# PX4FMUv2_4_6.net
KiCad netlist of a schematic drawn in EAGLE
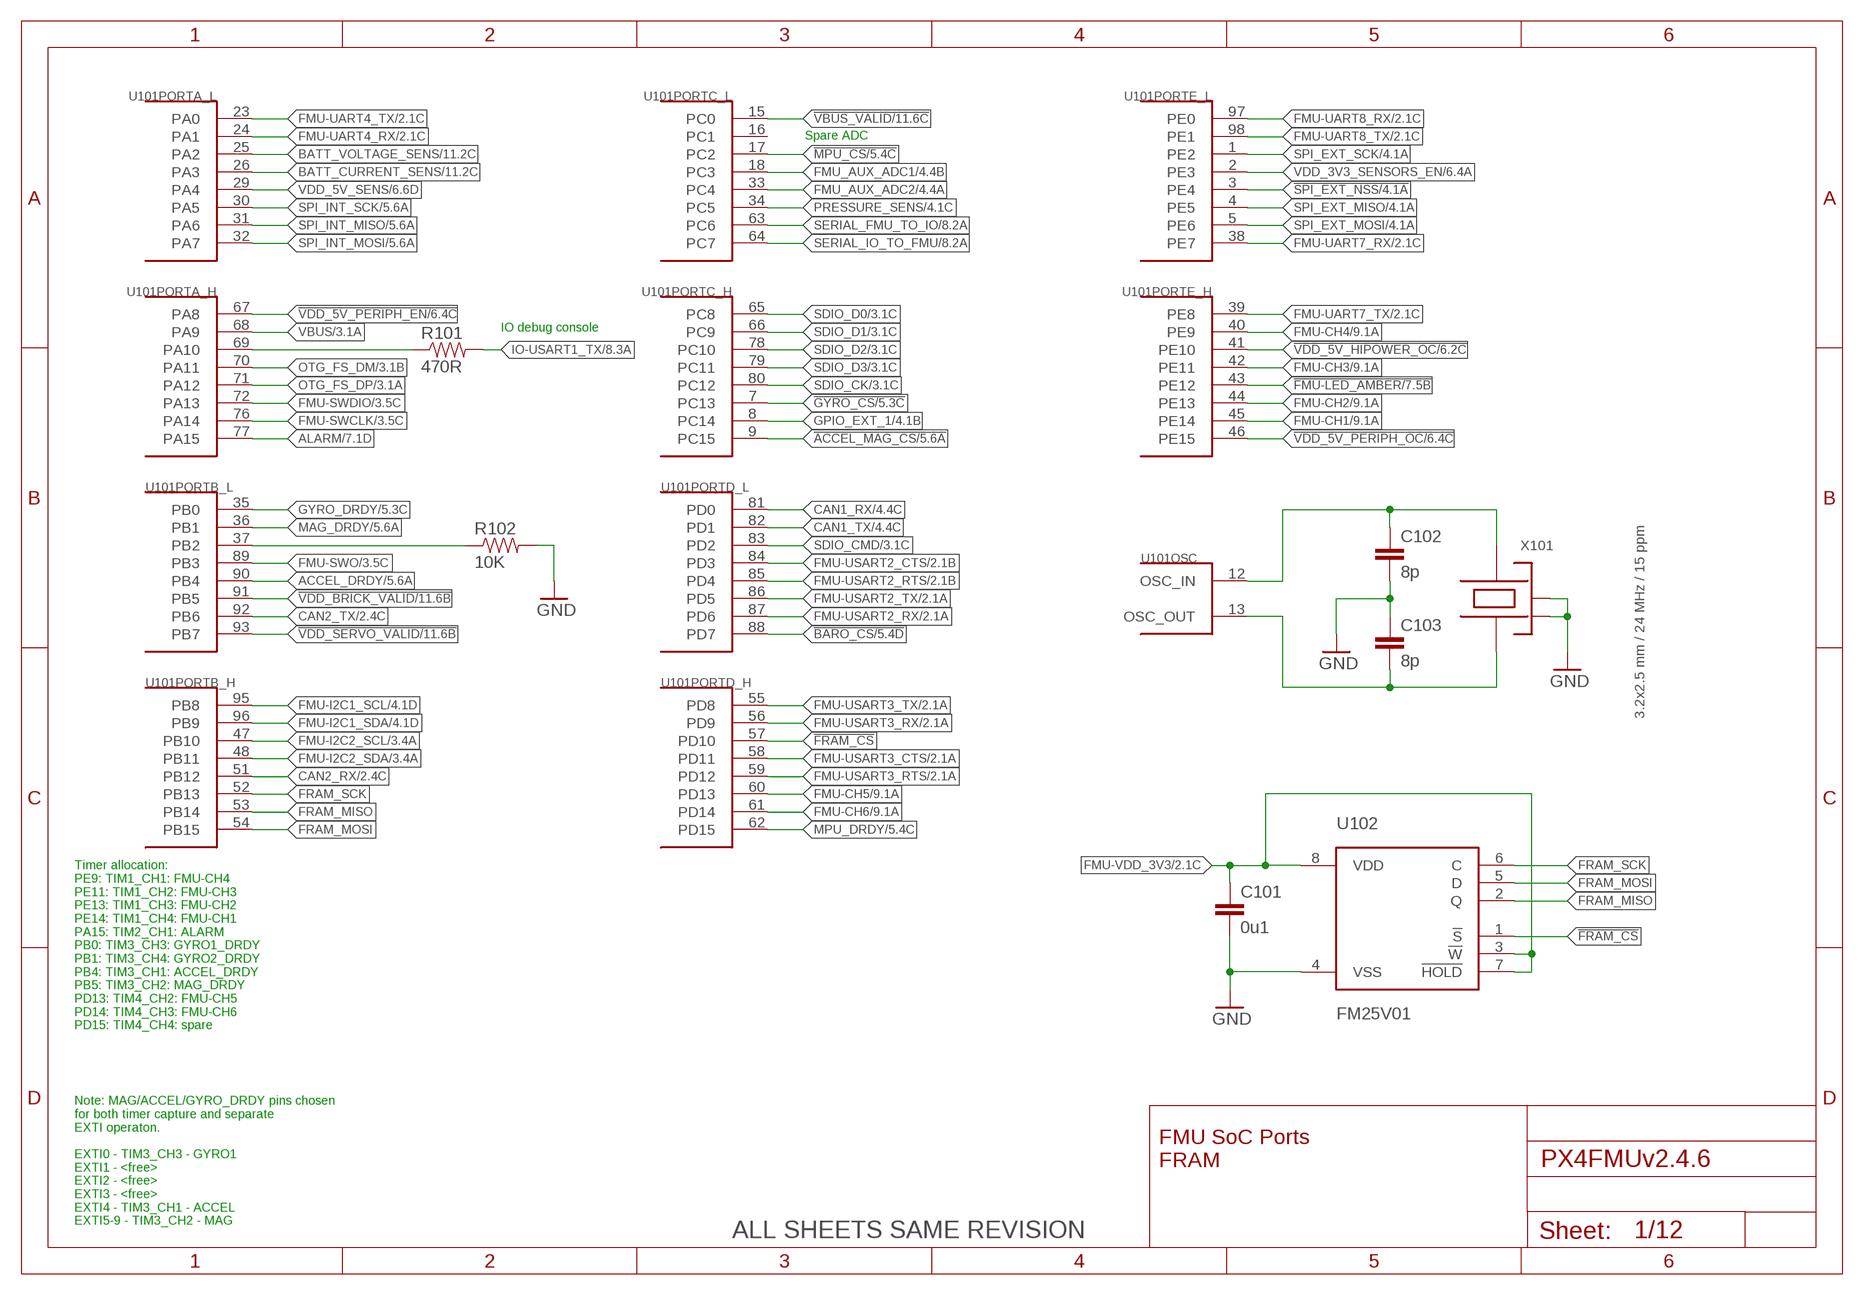
[diagram p0: schematic, sheet 1]
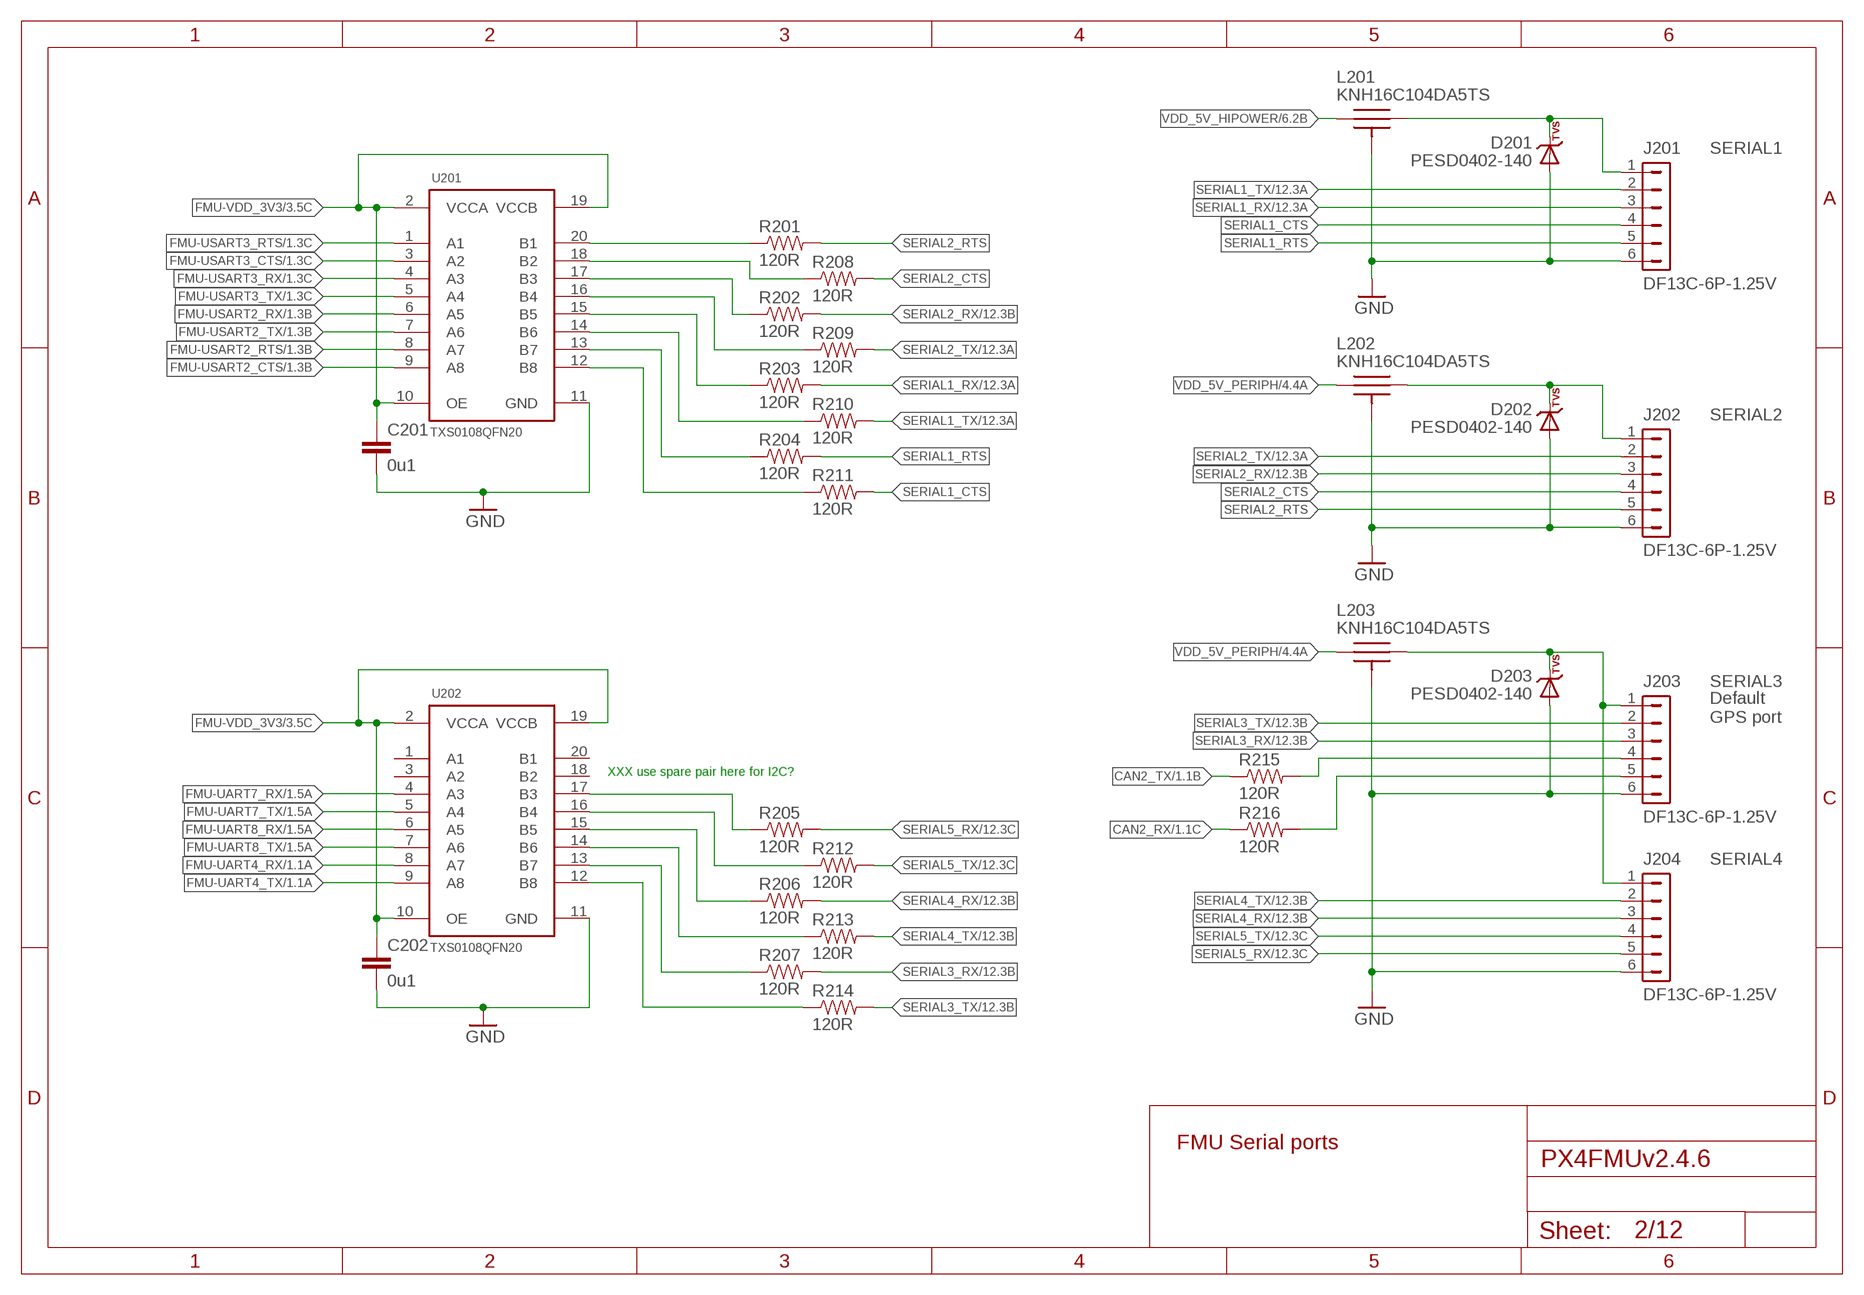
[diagram p1: schematic, sheet 2]
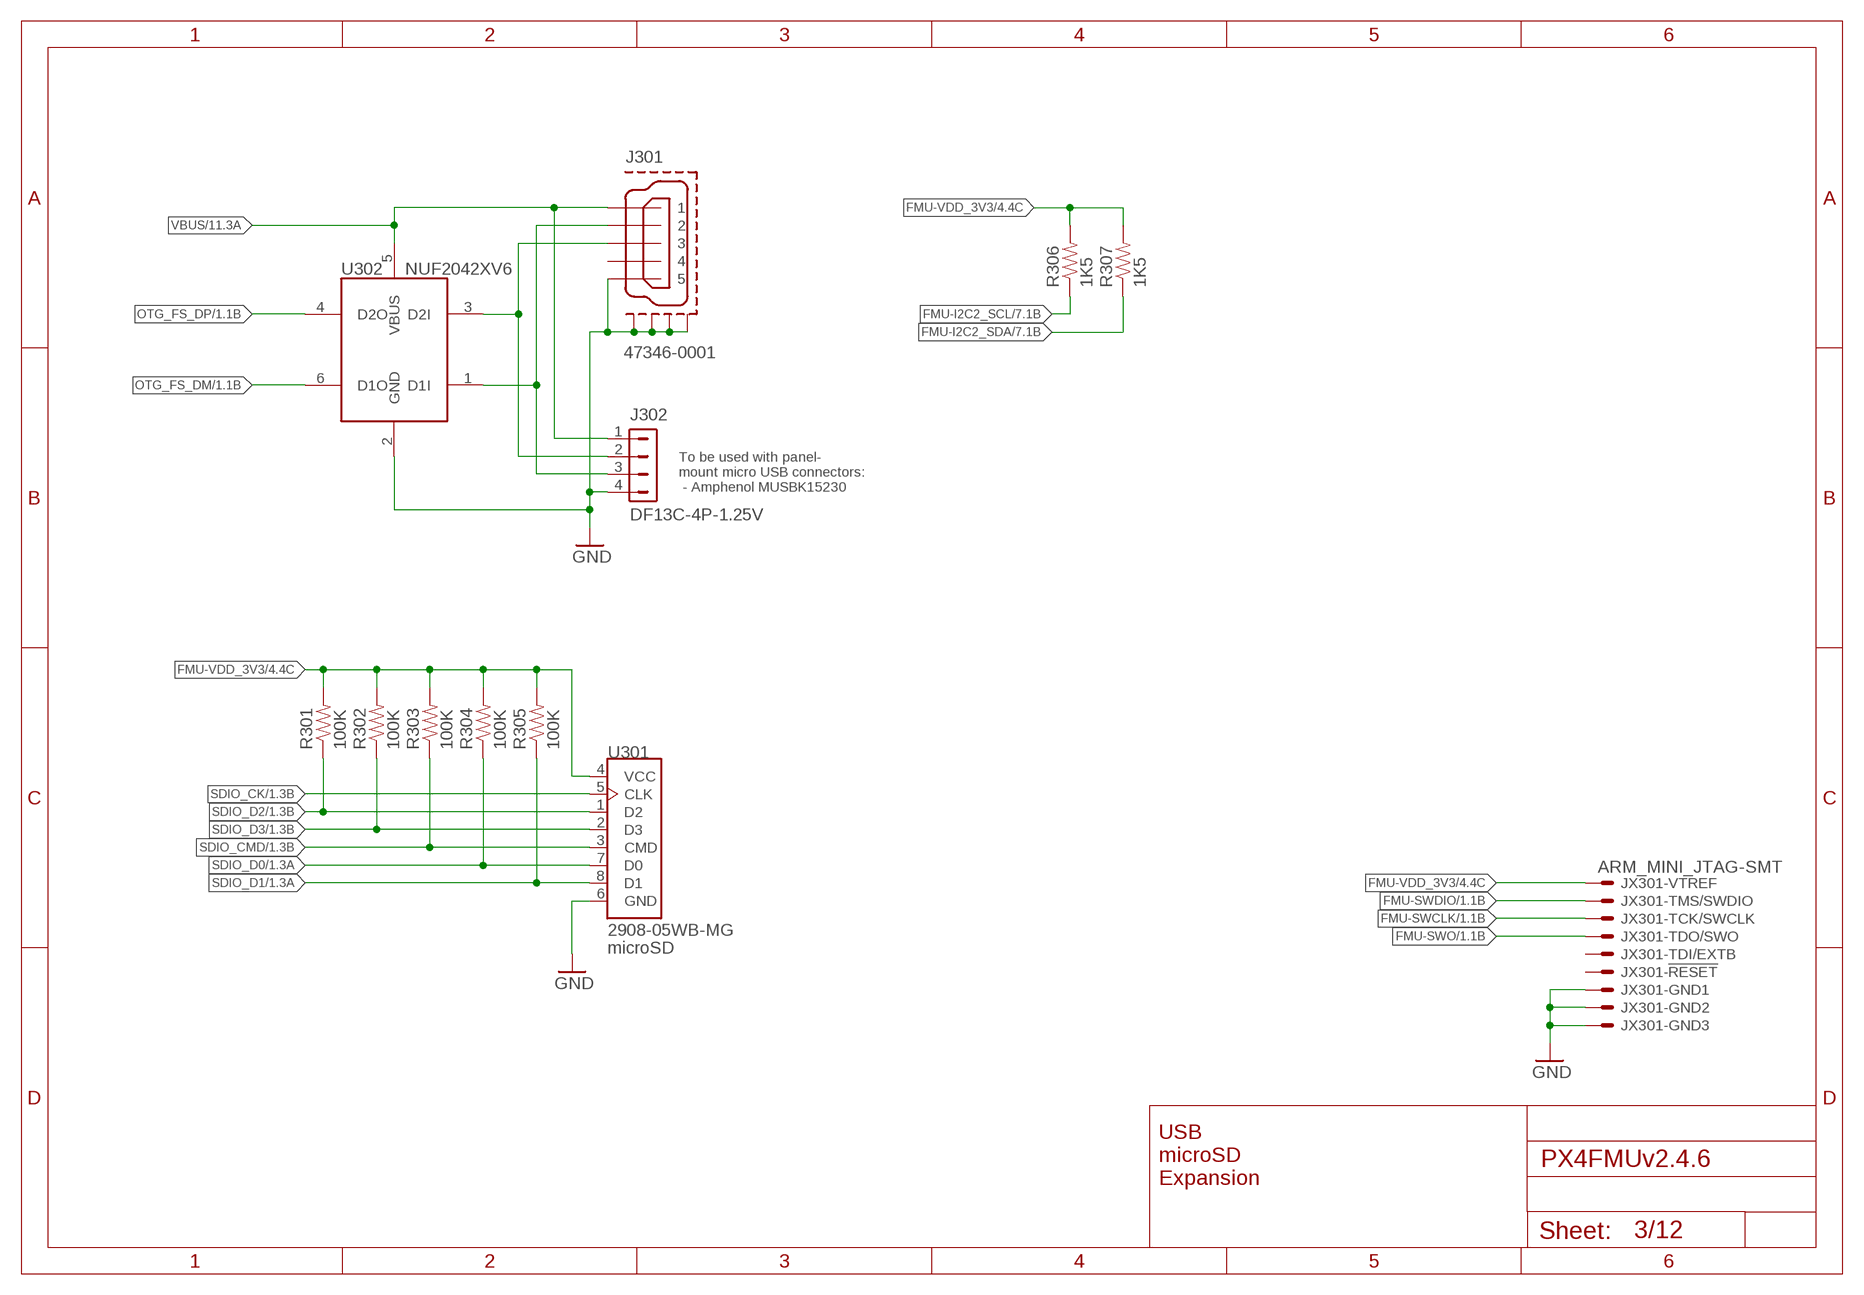
[diagram p2: schematic, sheet 3]
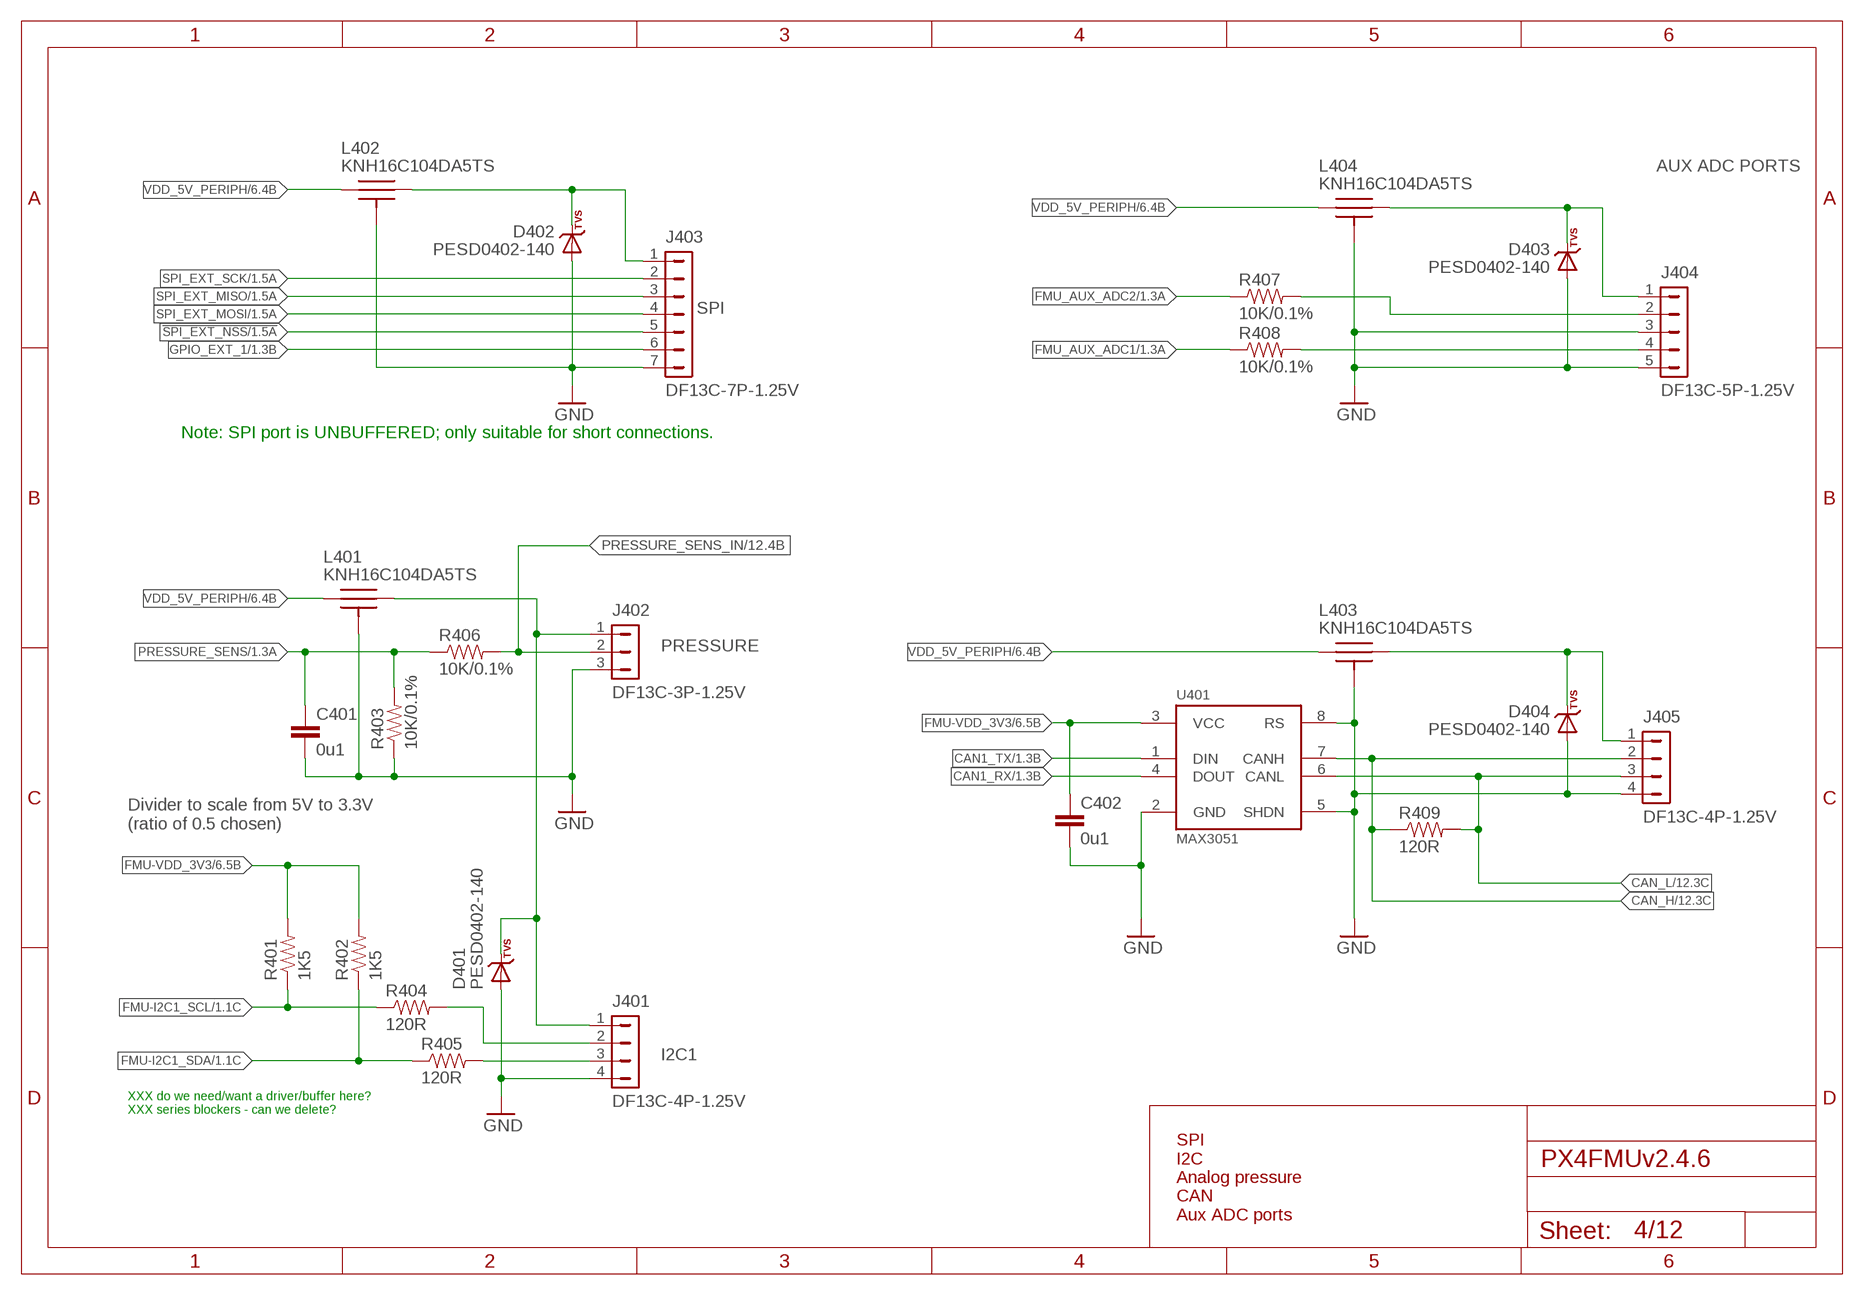
[diagram p3: schematic, sheet 4]
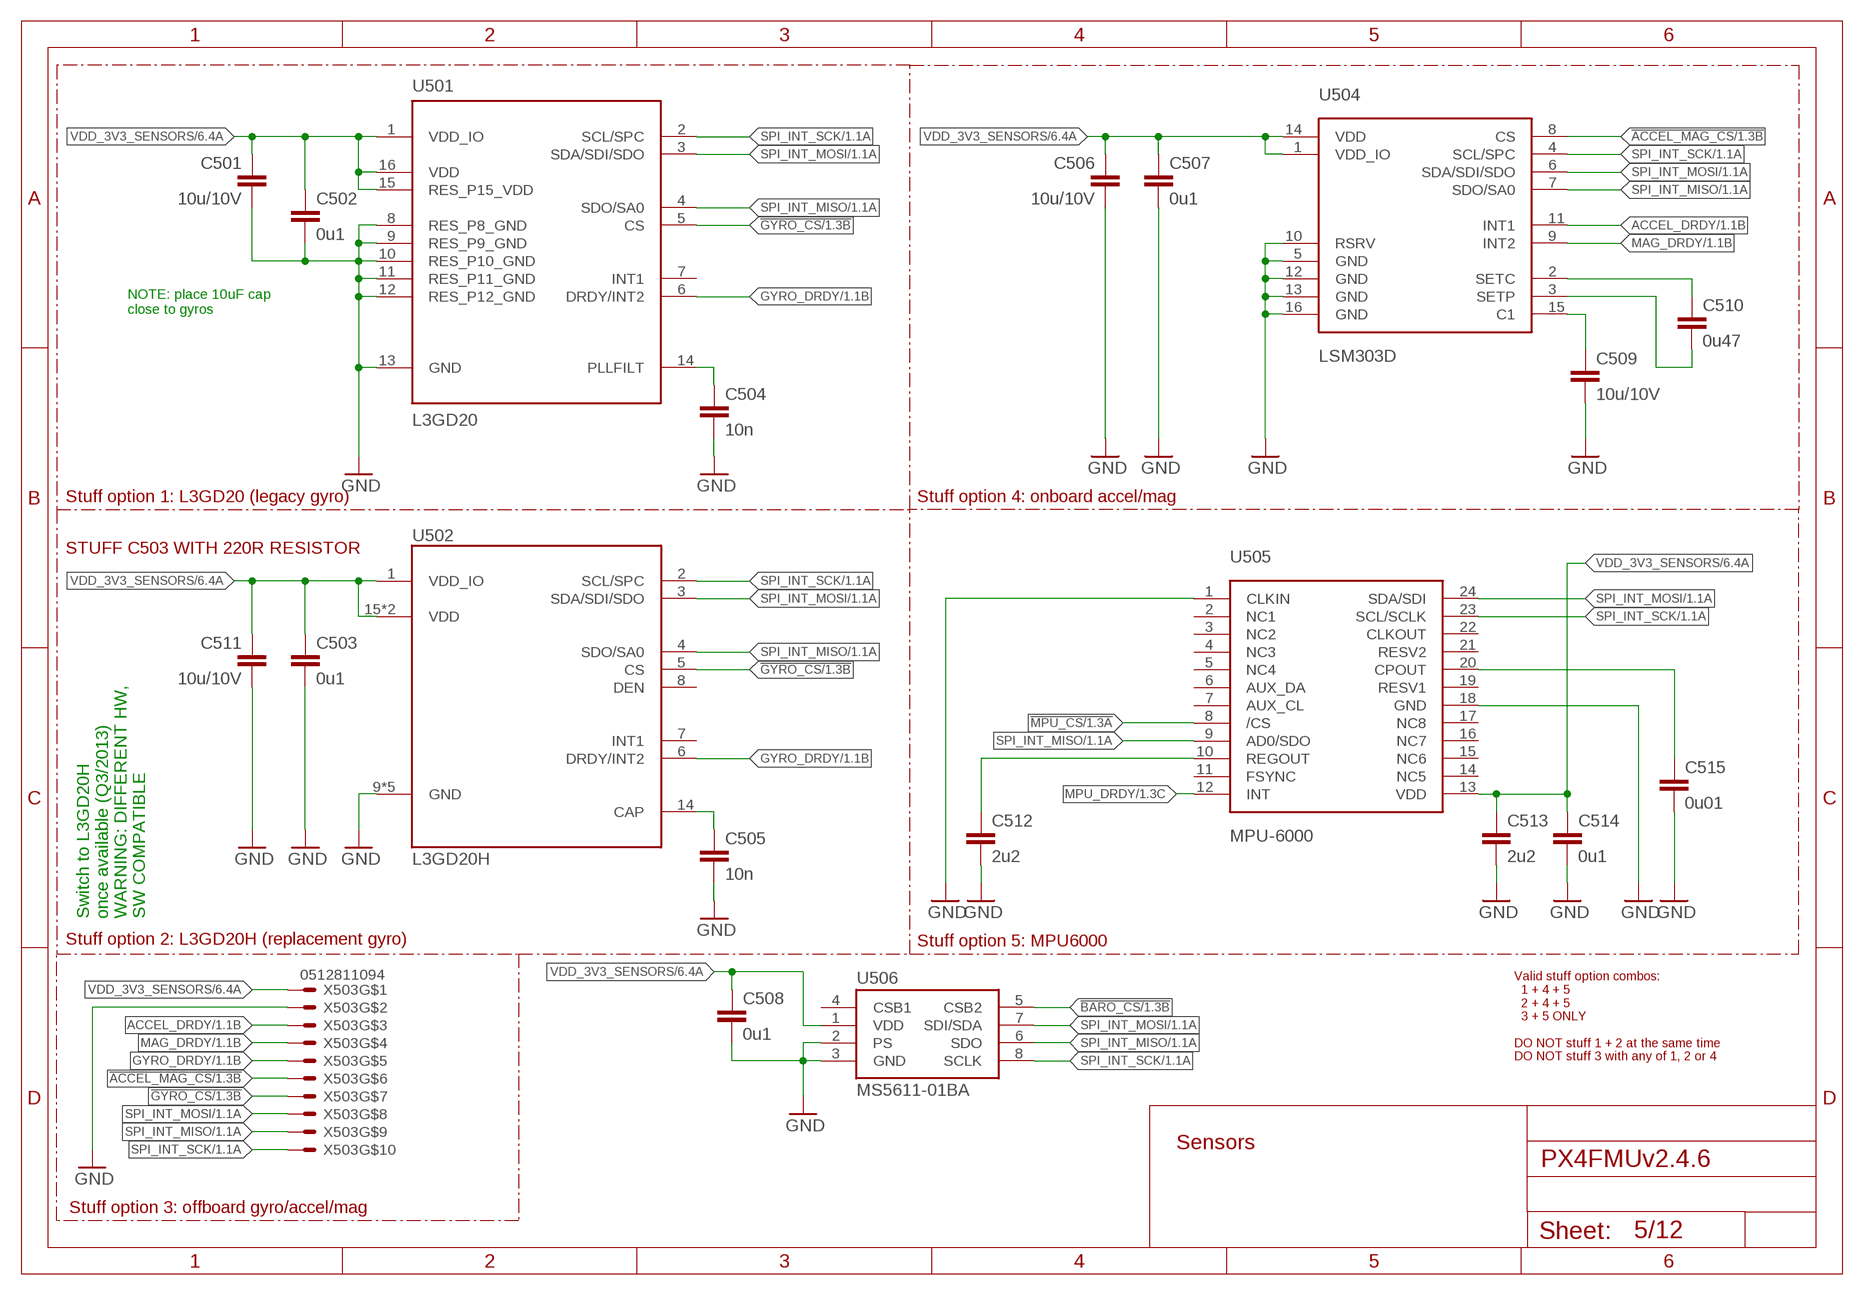
[diagram p4: schematic, sheet 5]
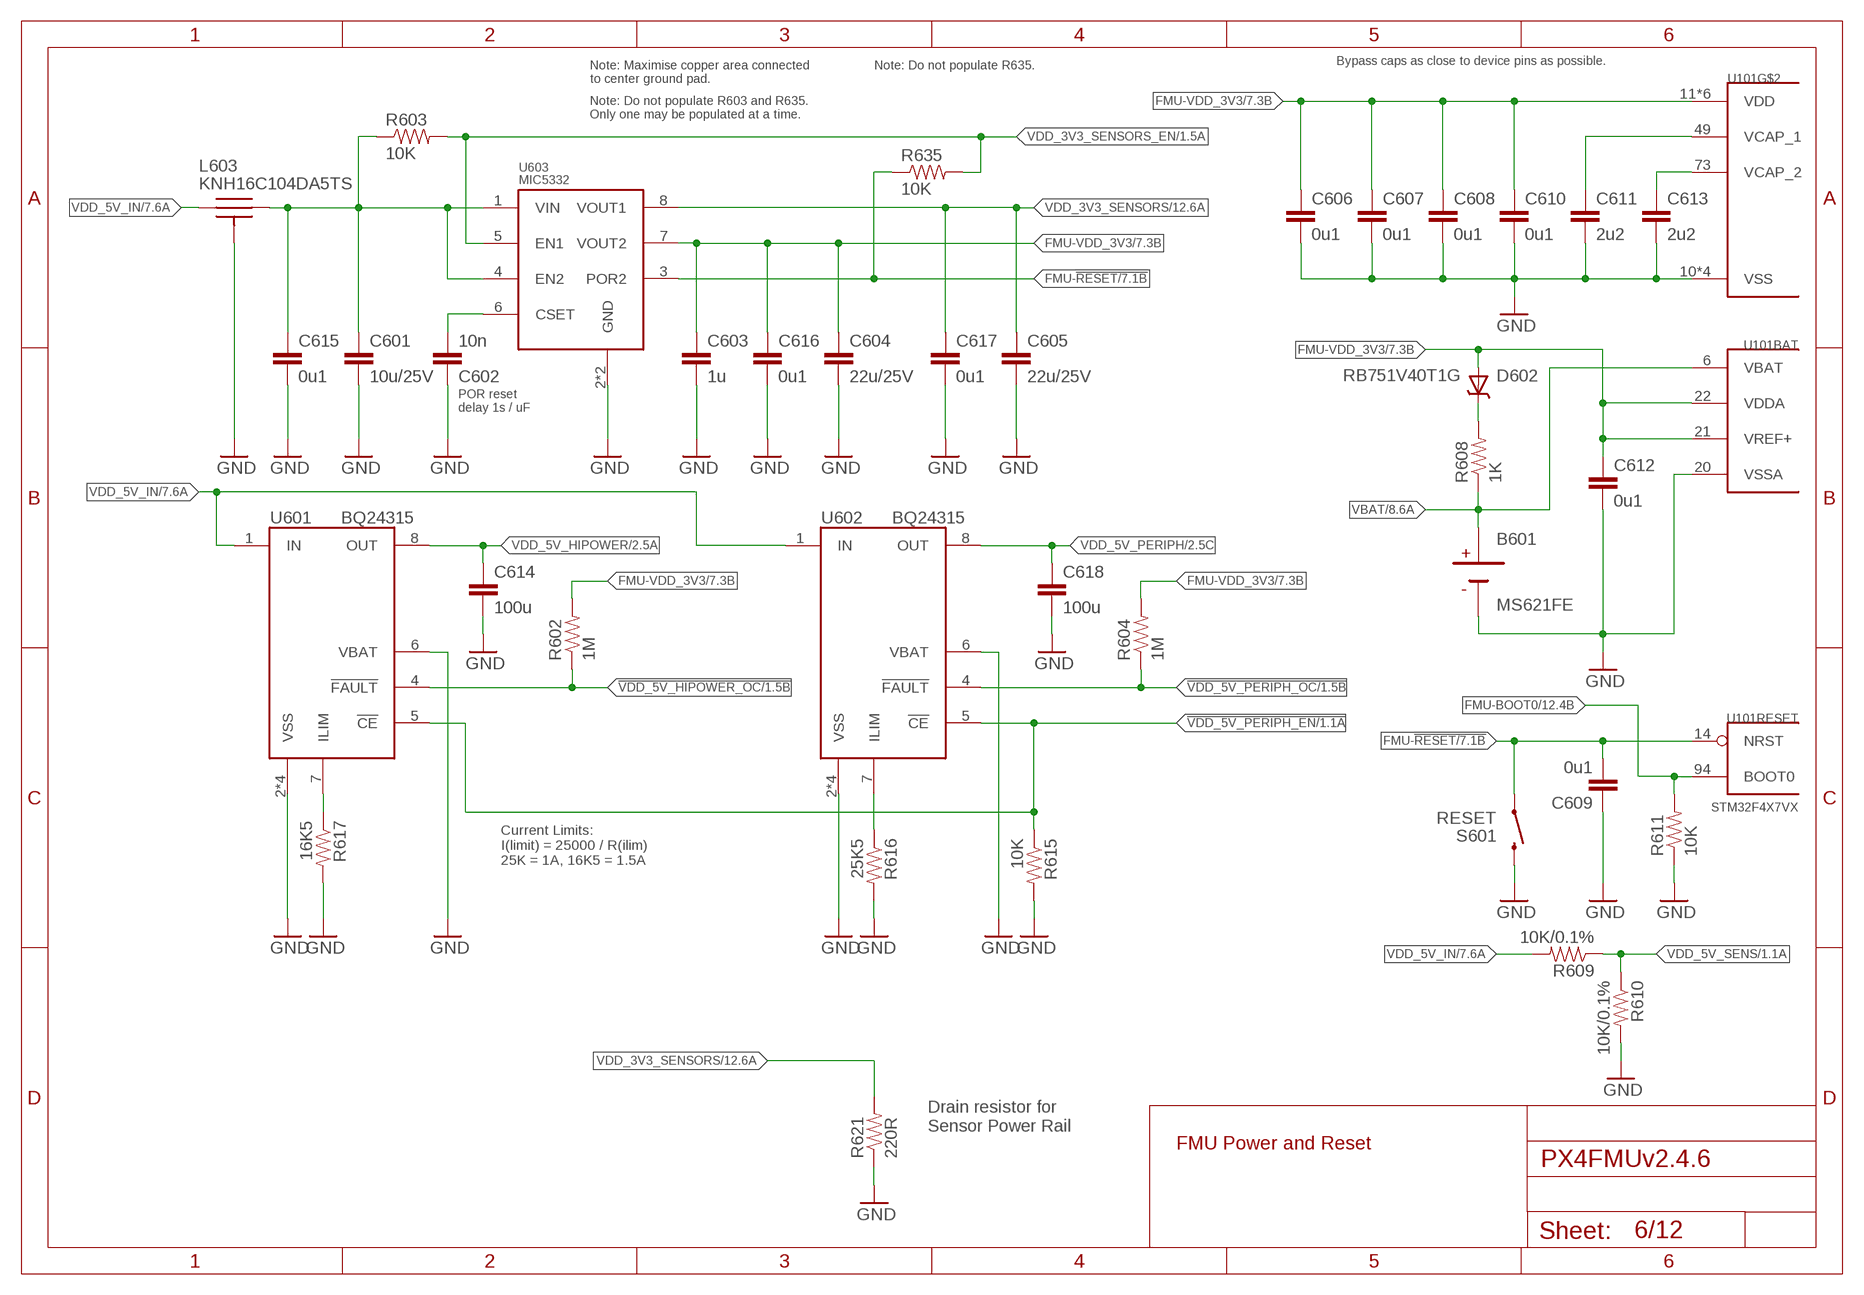
[diagram p5: schematic, sheet 6]
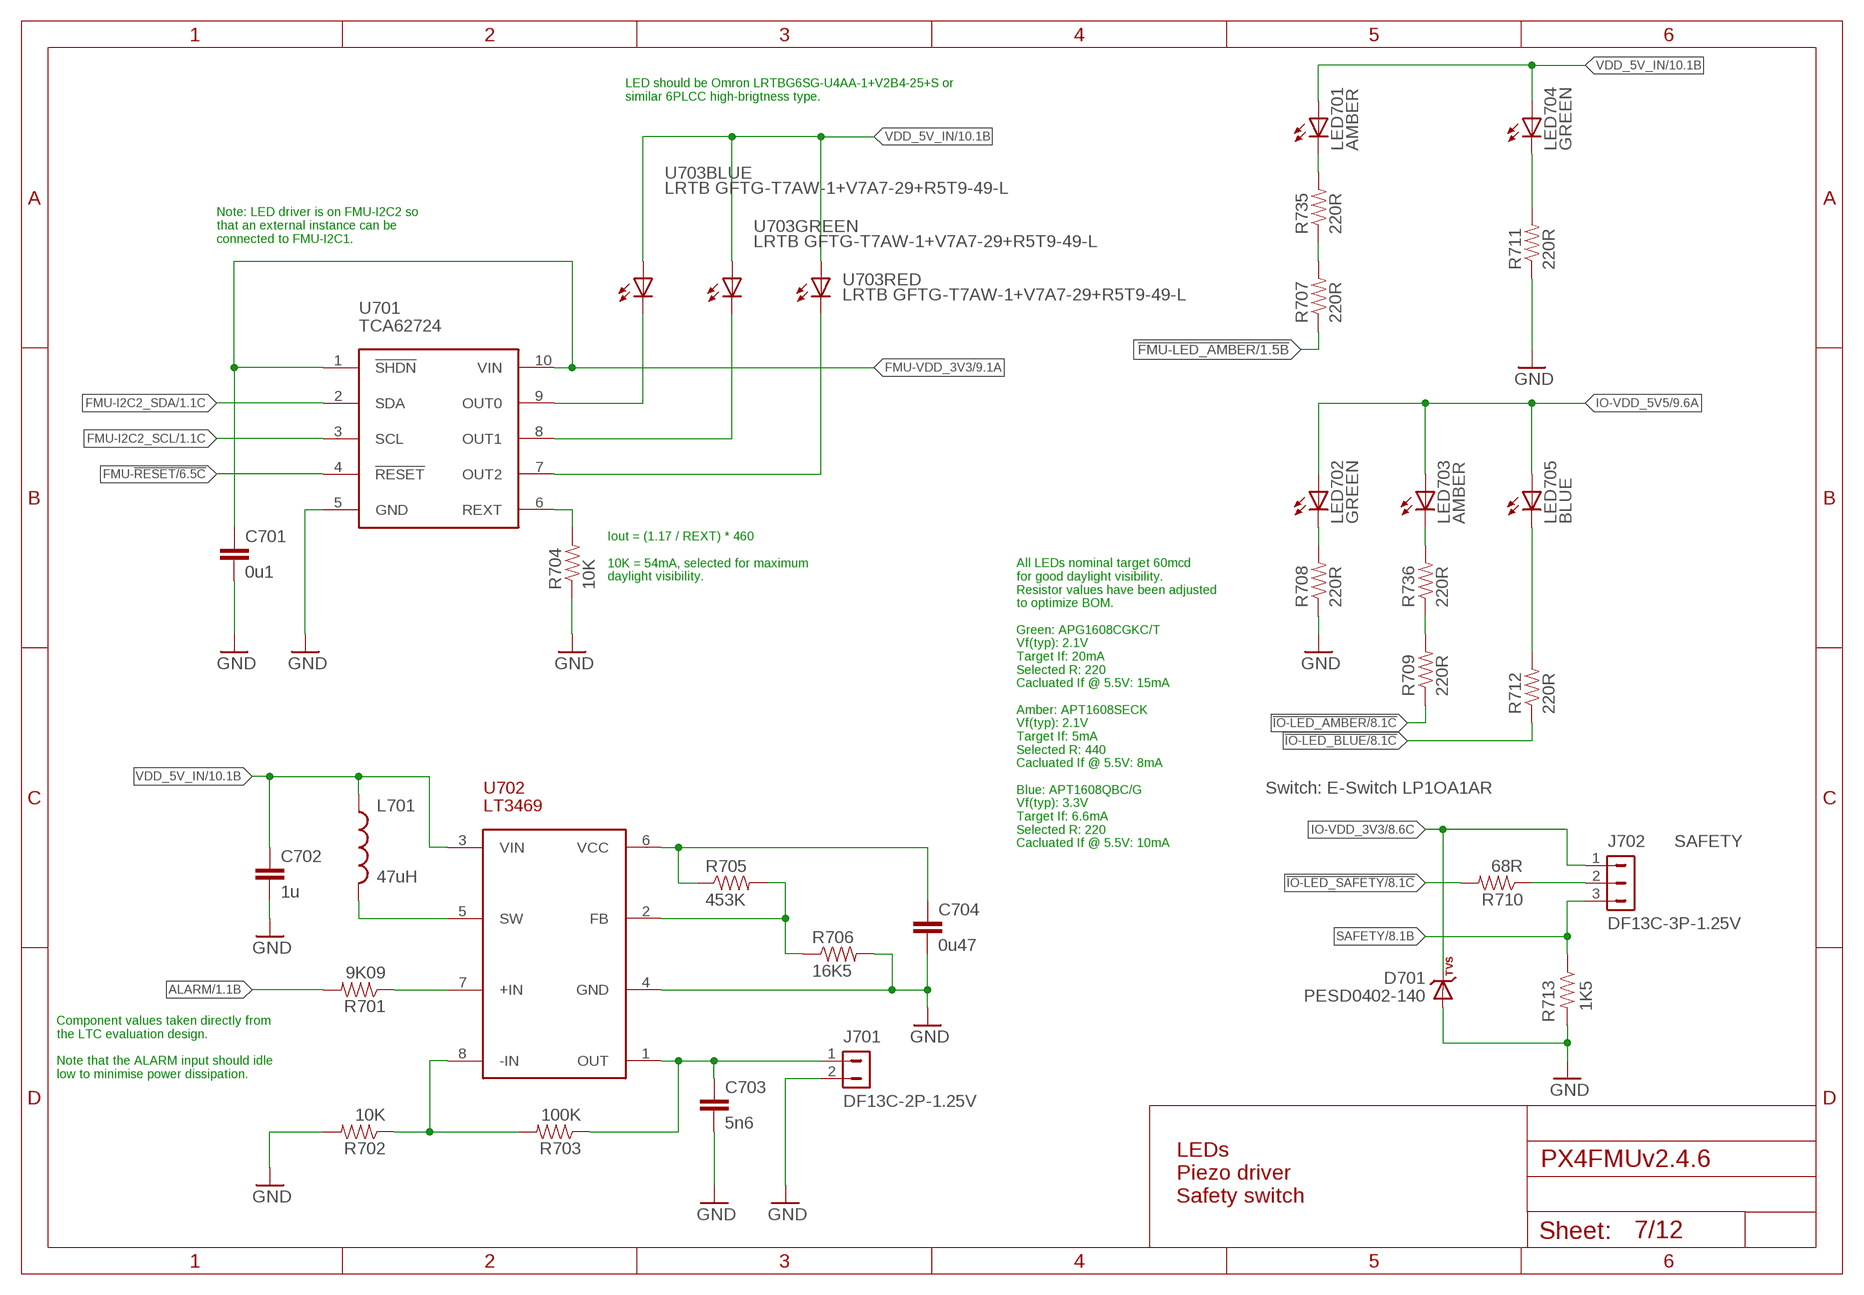
[diagram p6: schematic, sheet 7]
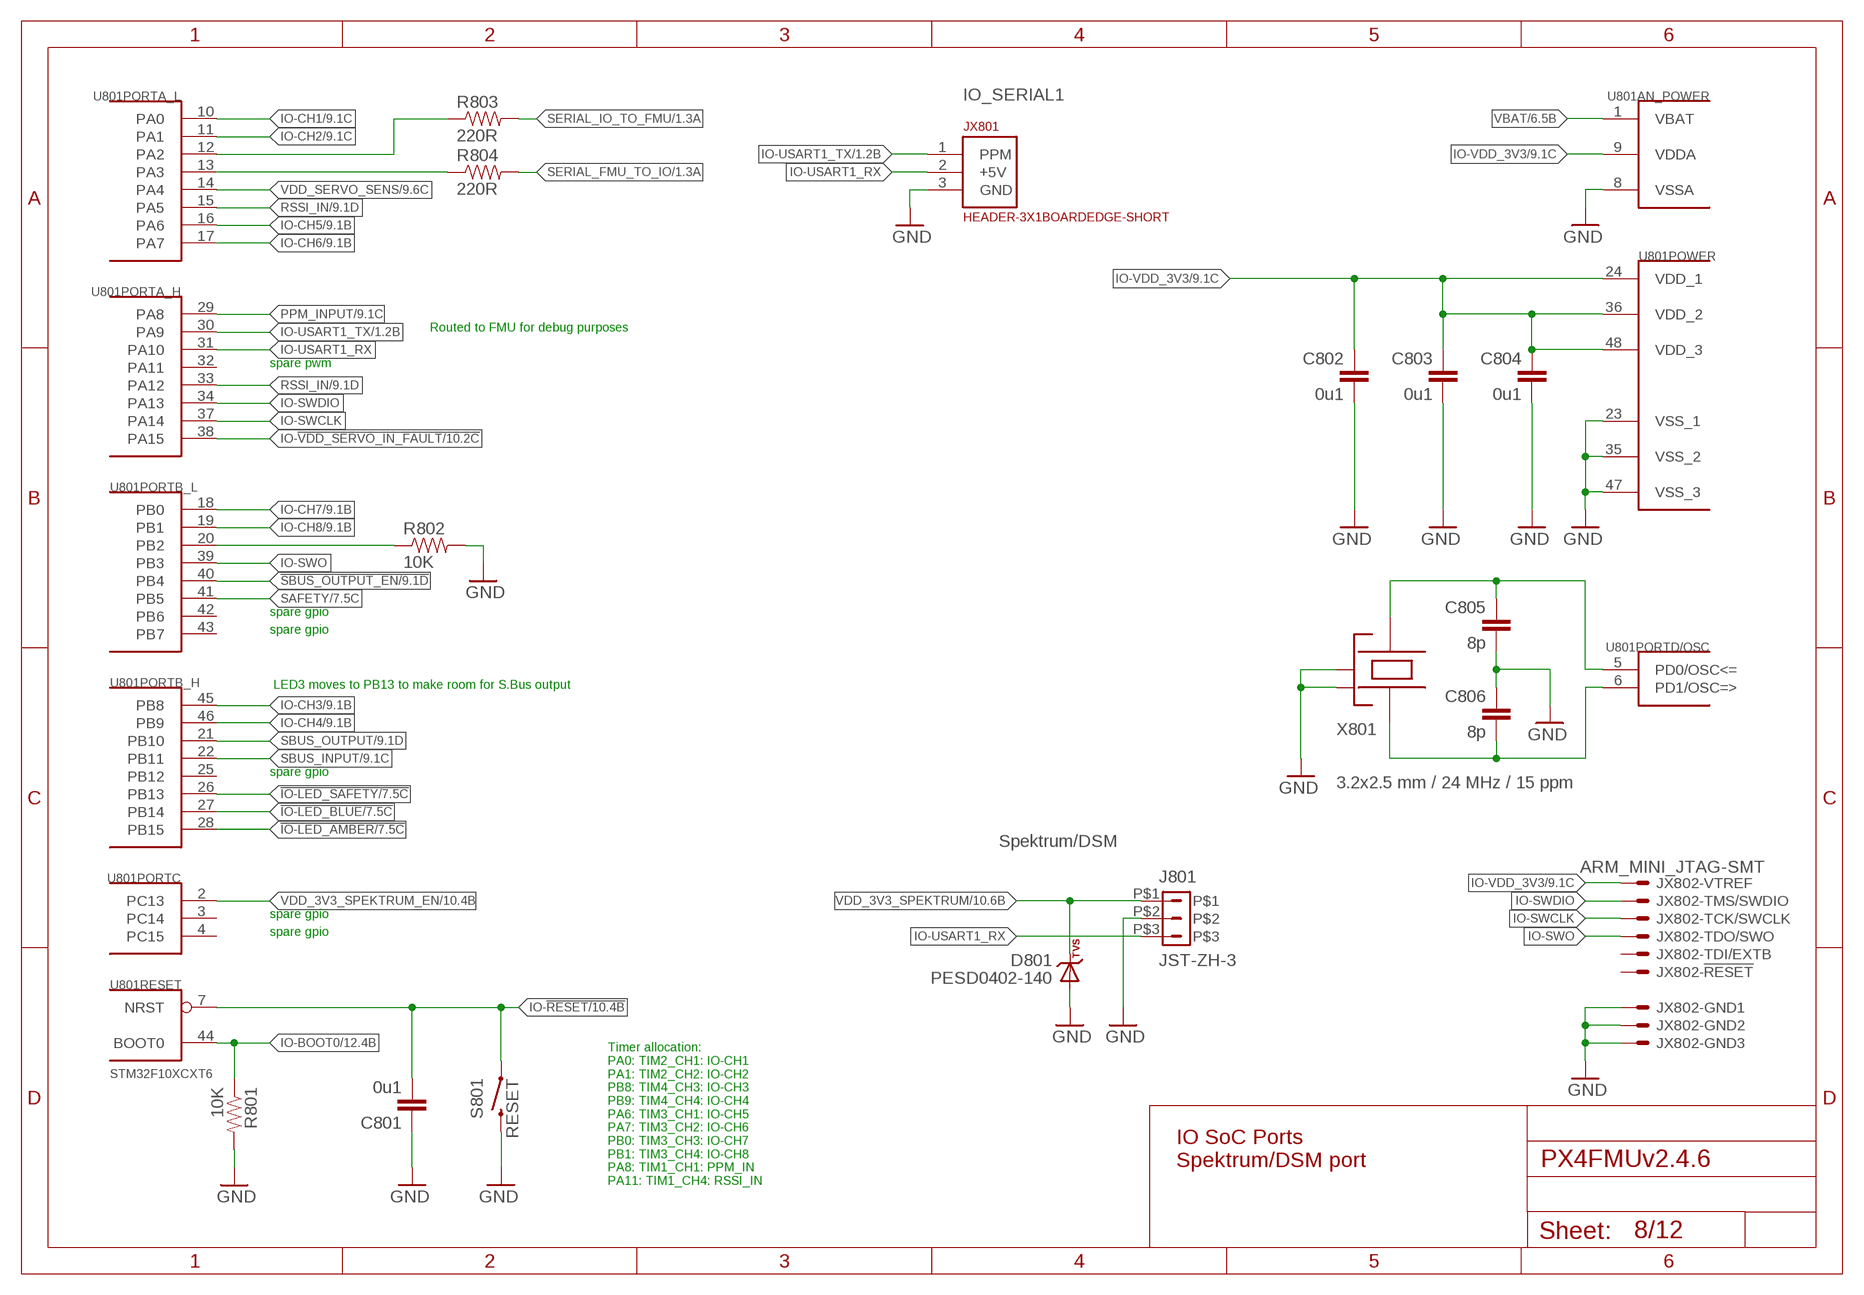
[diagram p7: schematic, sheet 8]
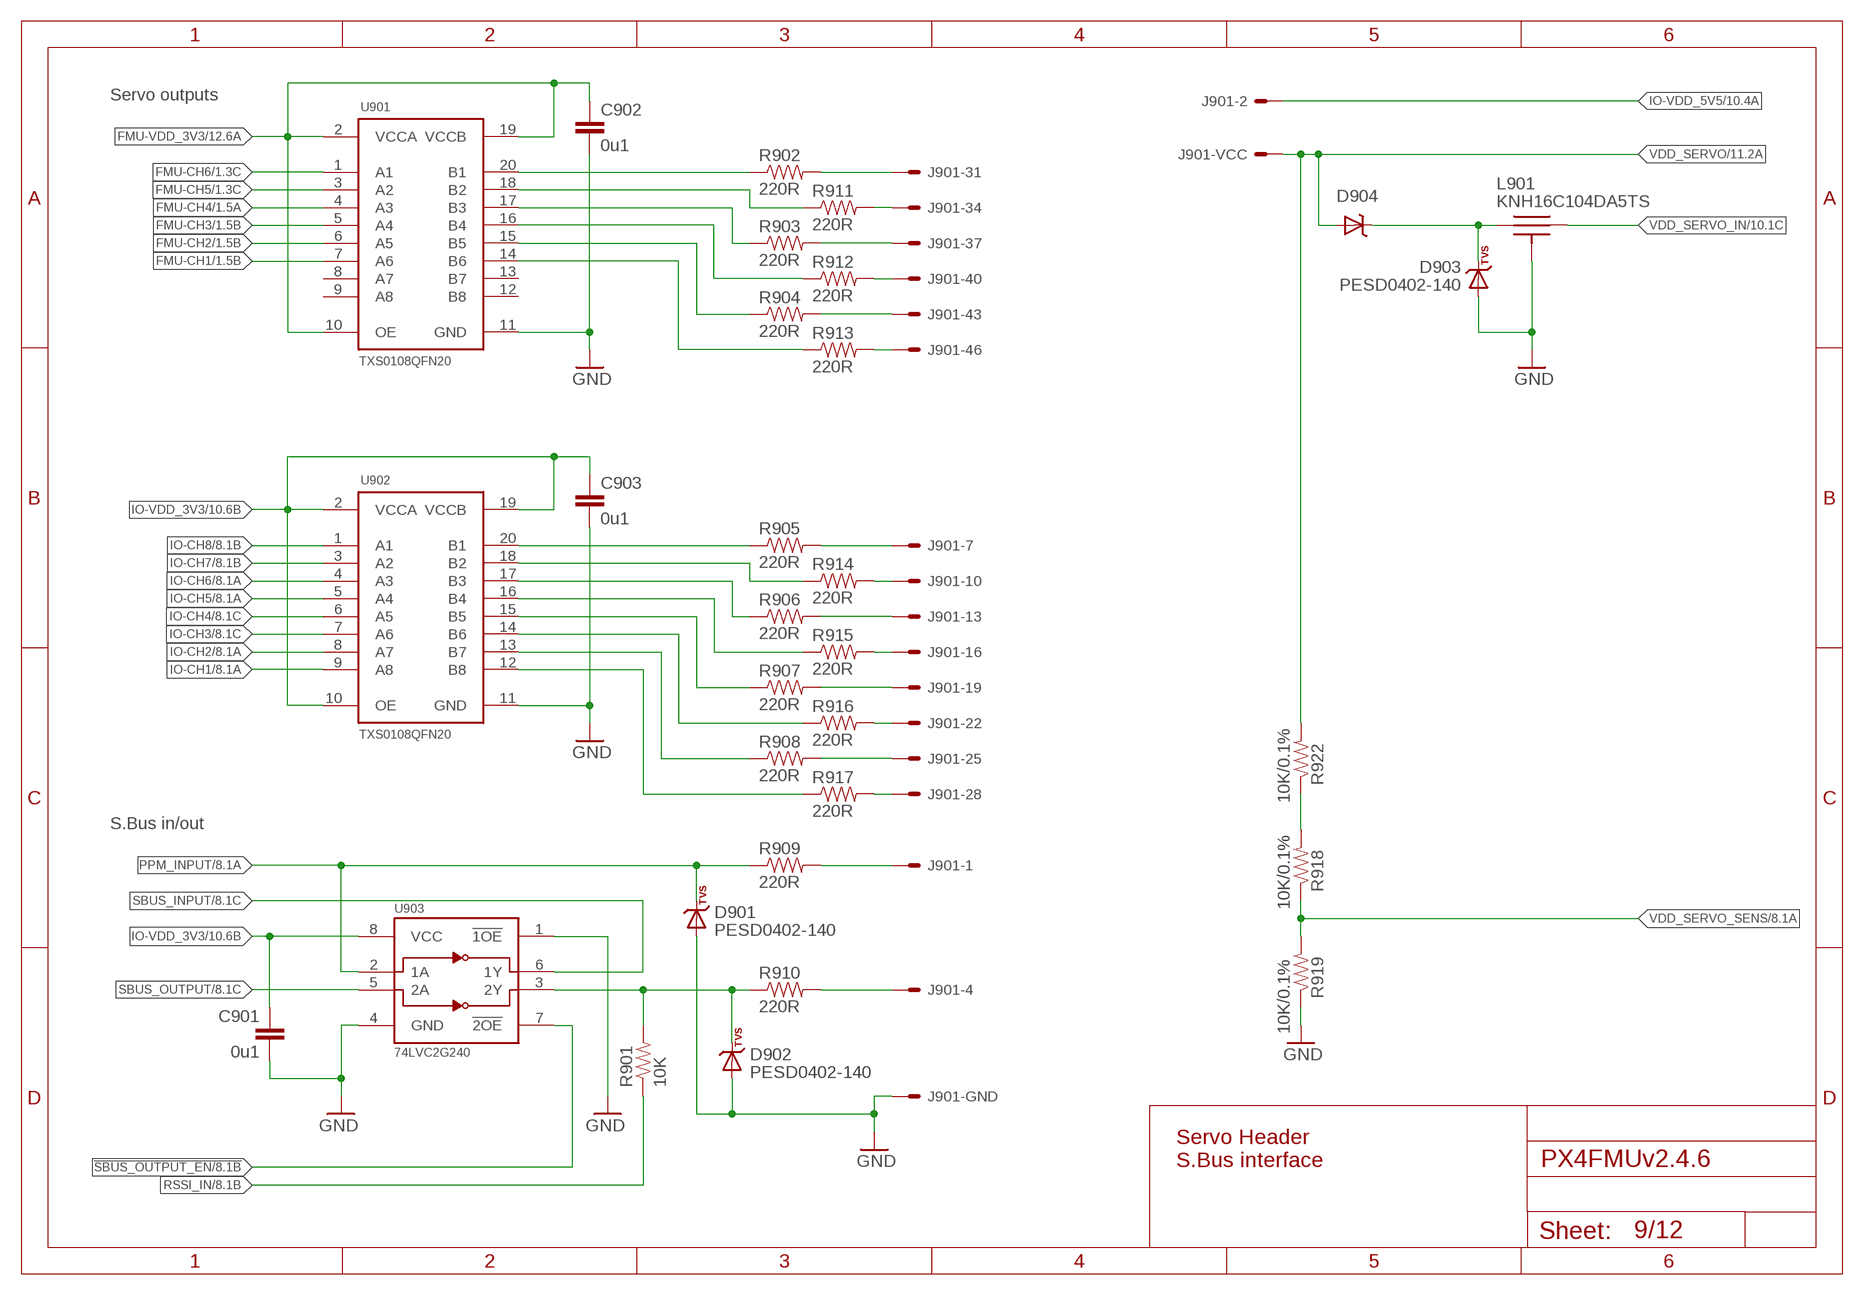
[diagram p8: schematic, sheet 9]
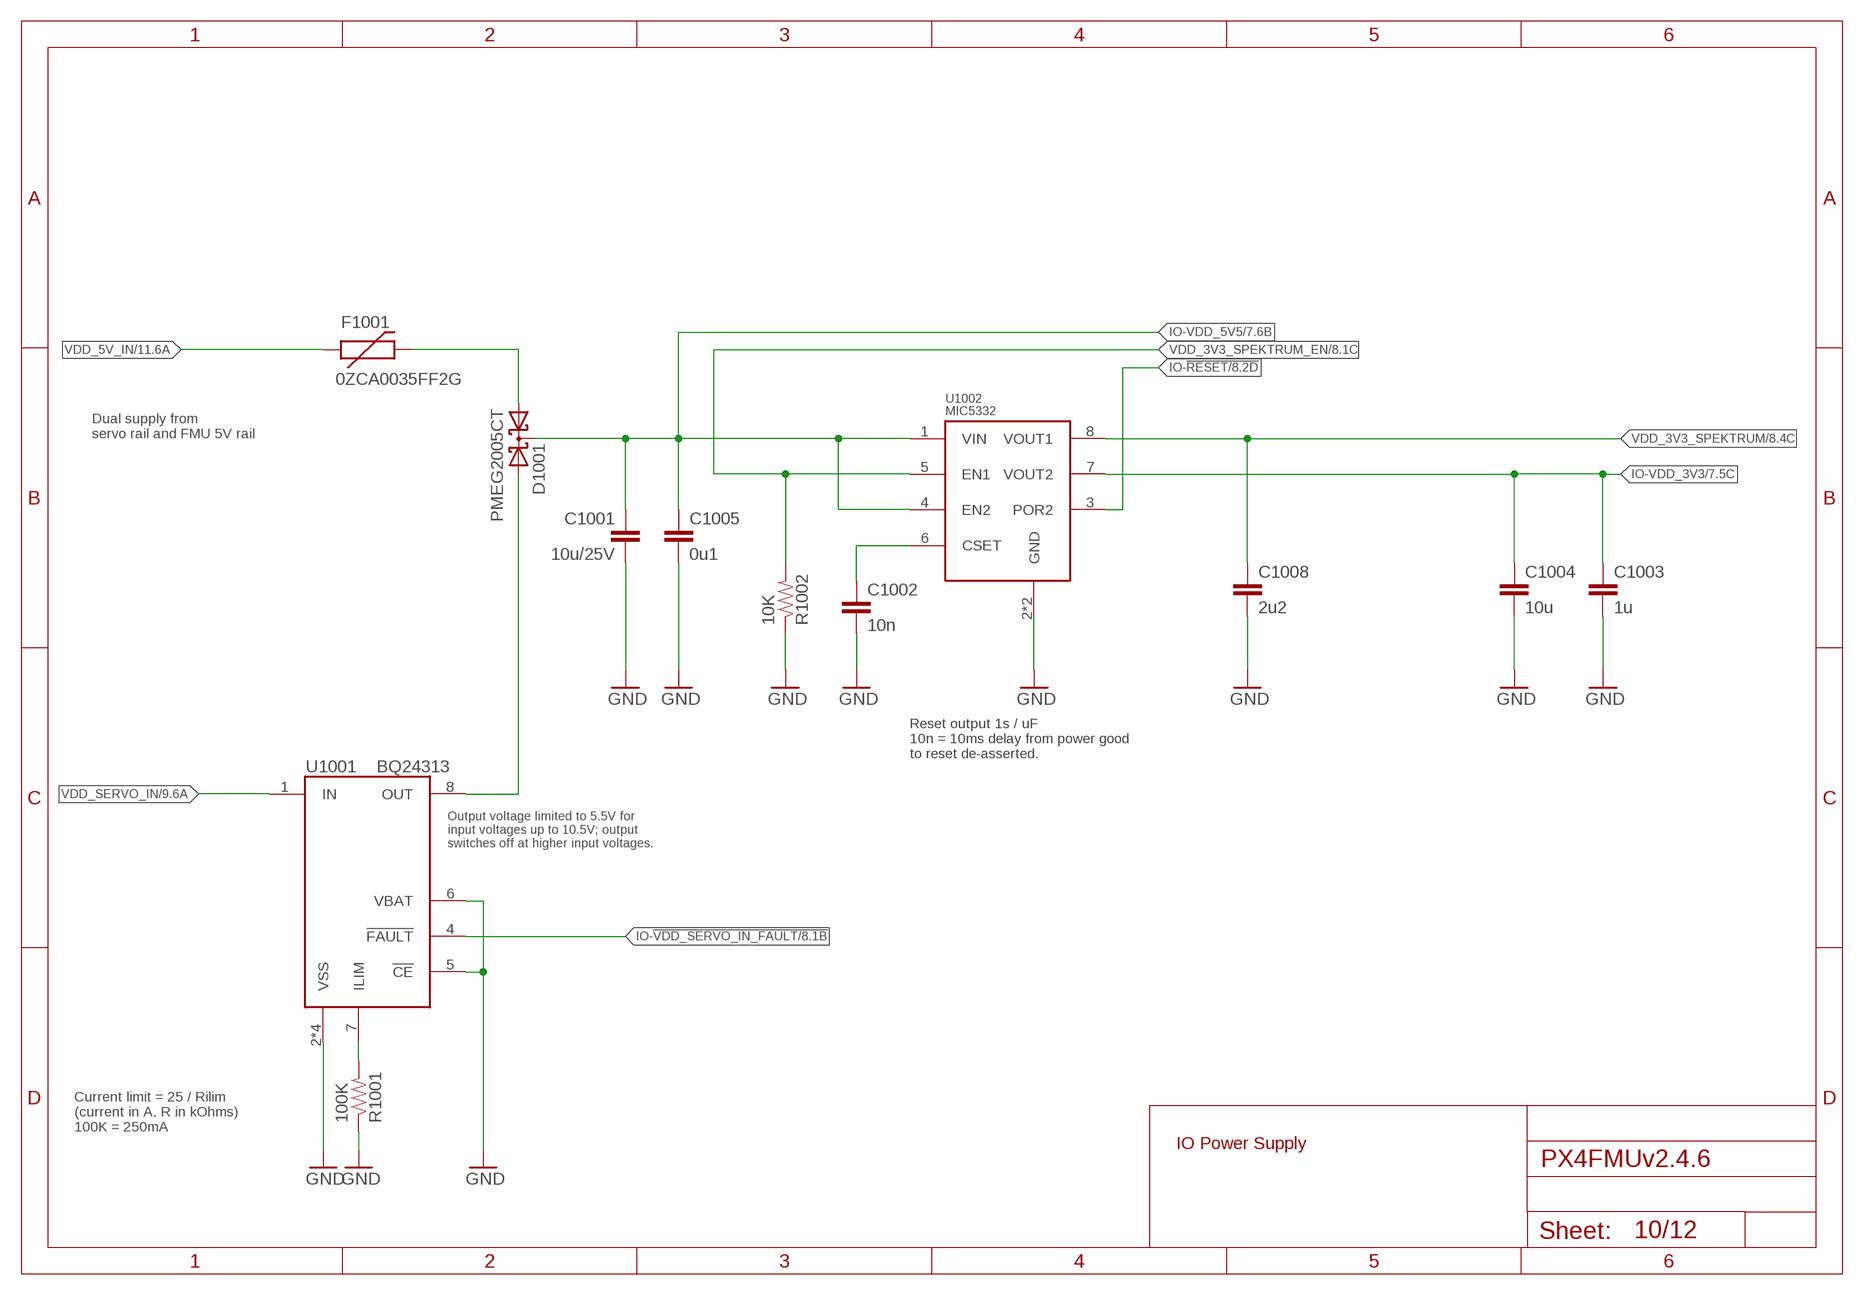
[diagram p9: schematic, sheet 10]
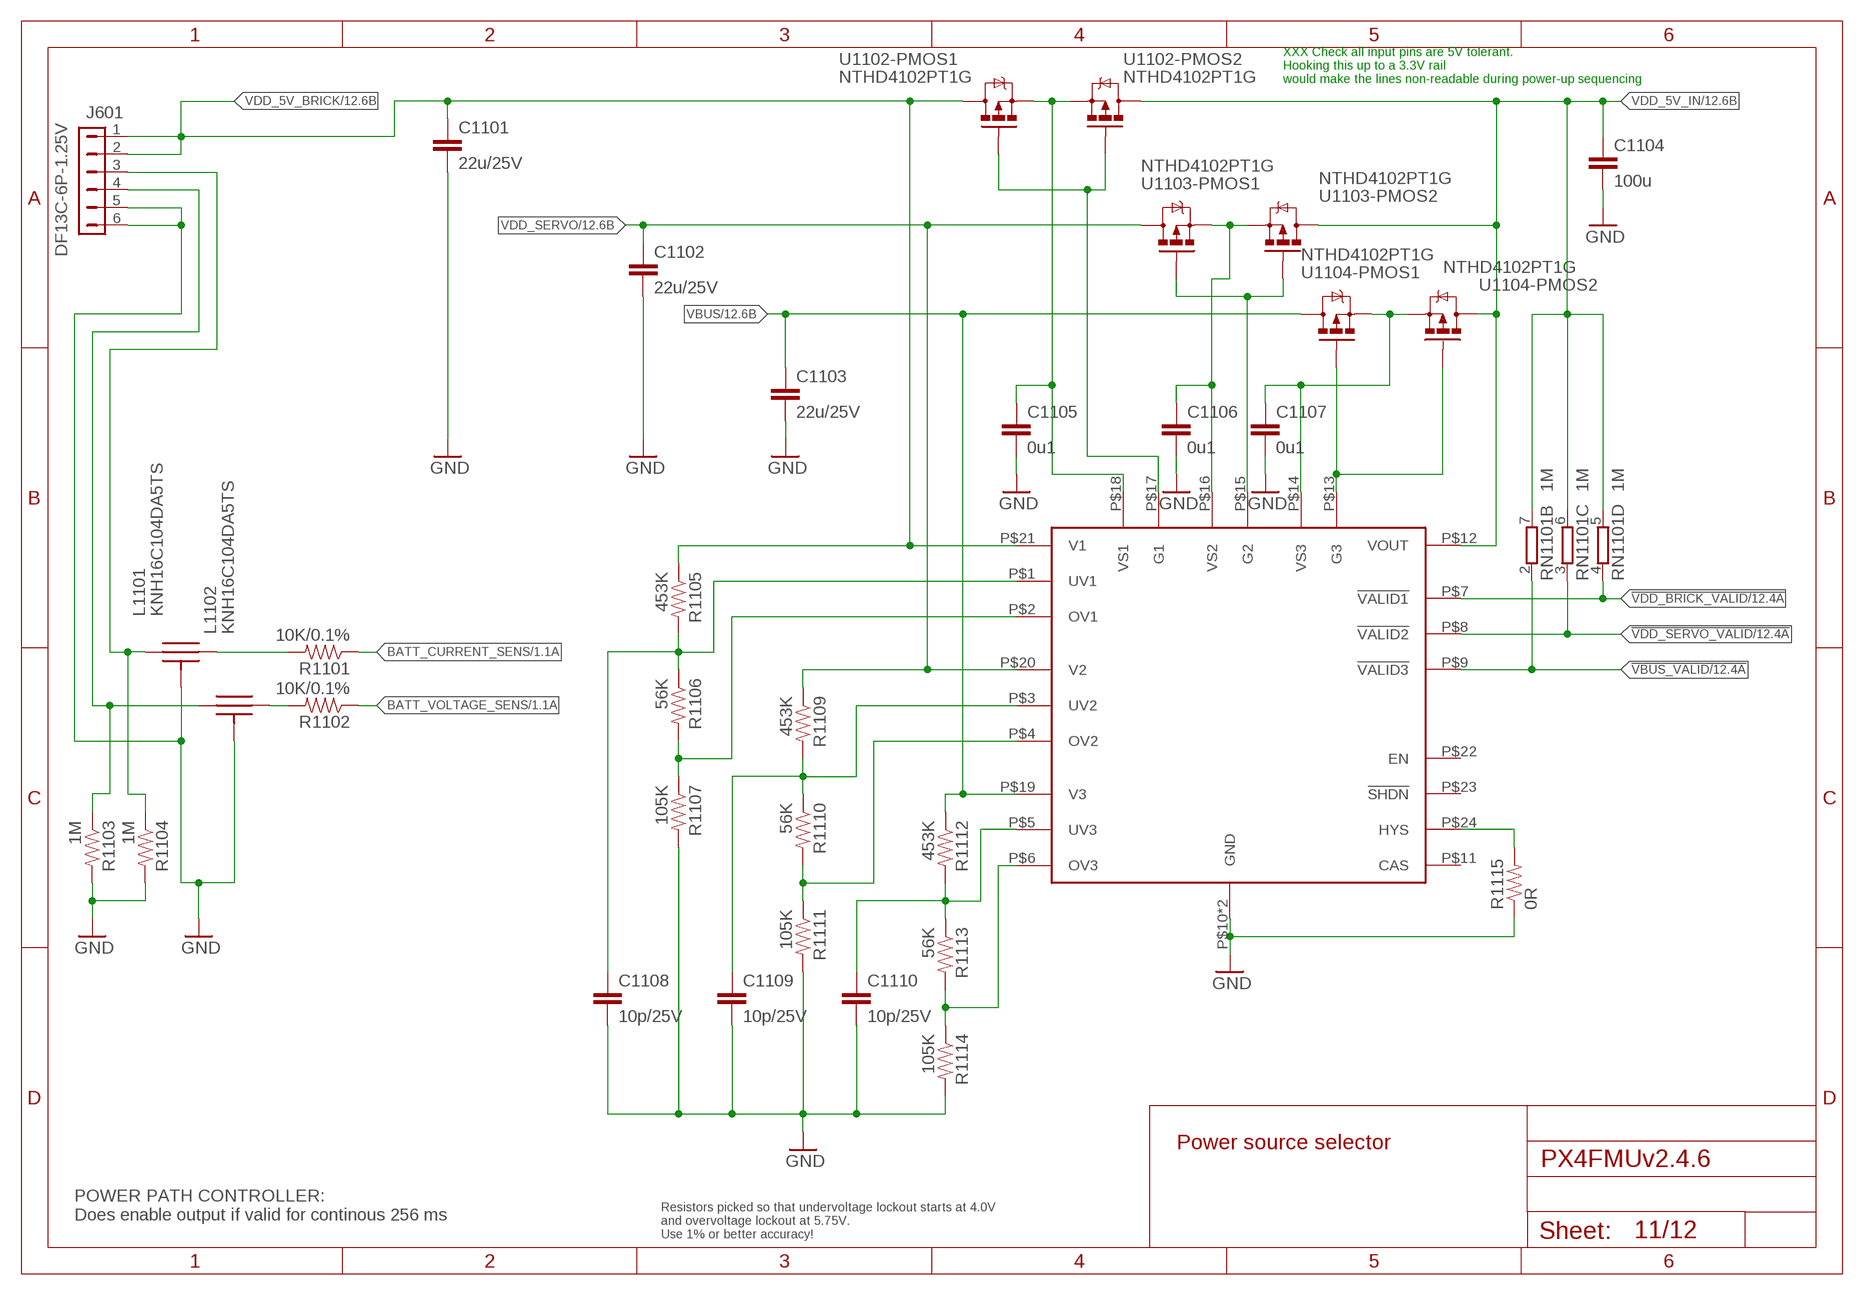
[diagram p10: schematic, sheet 11]
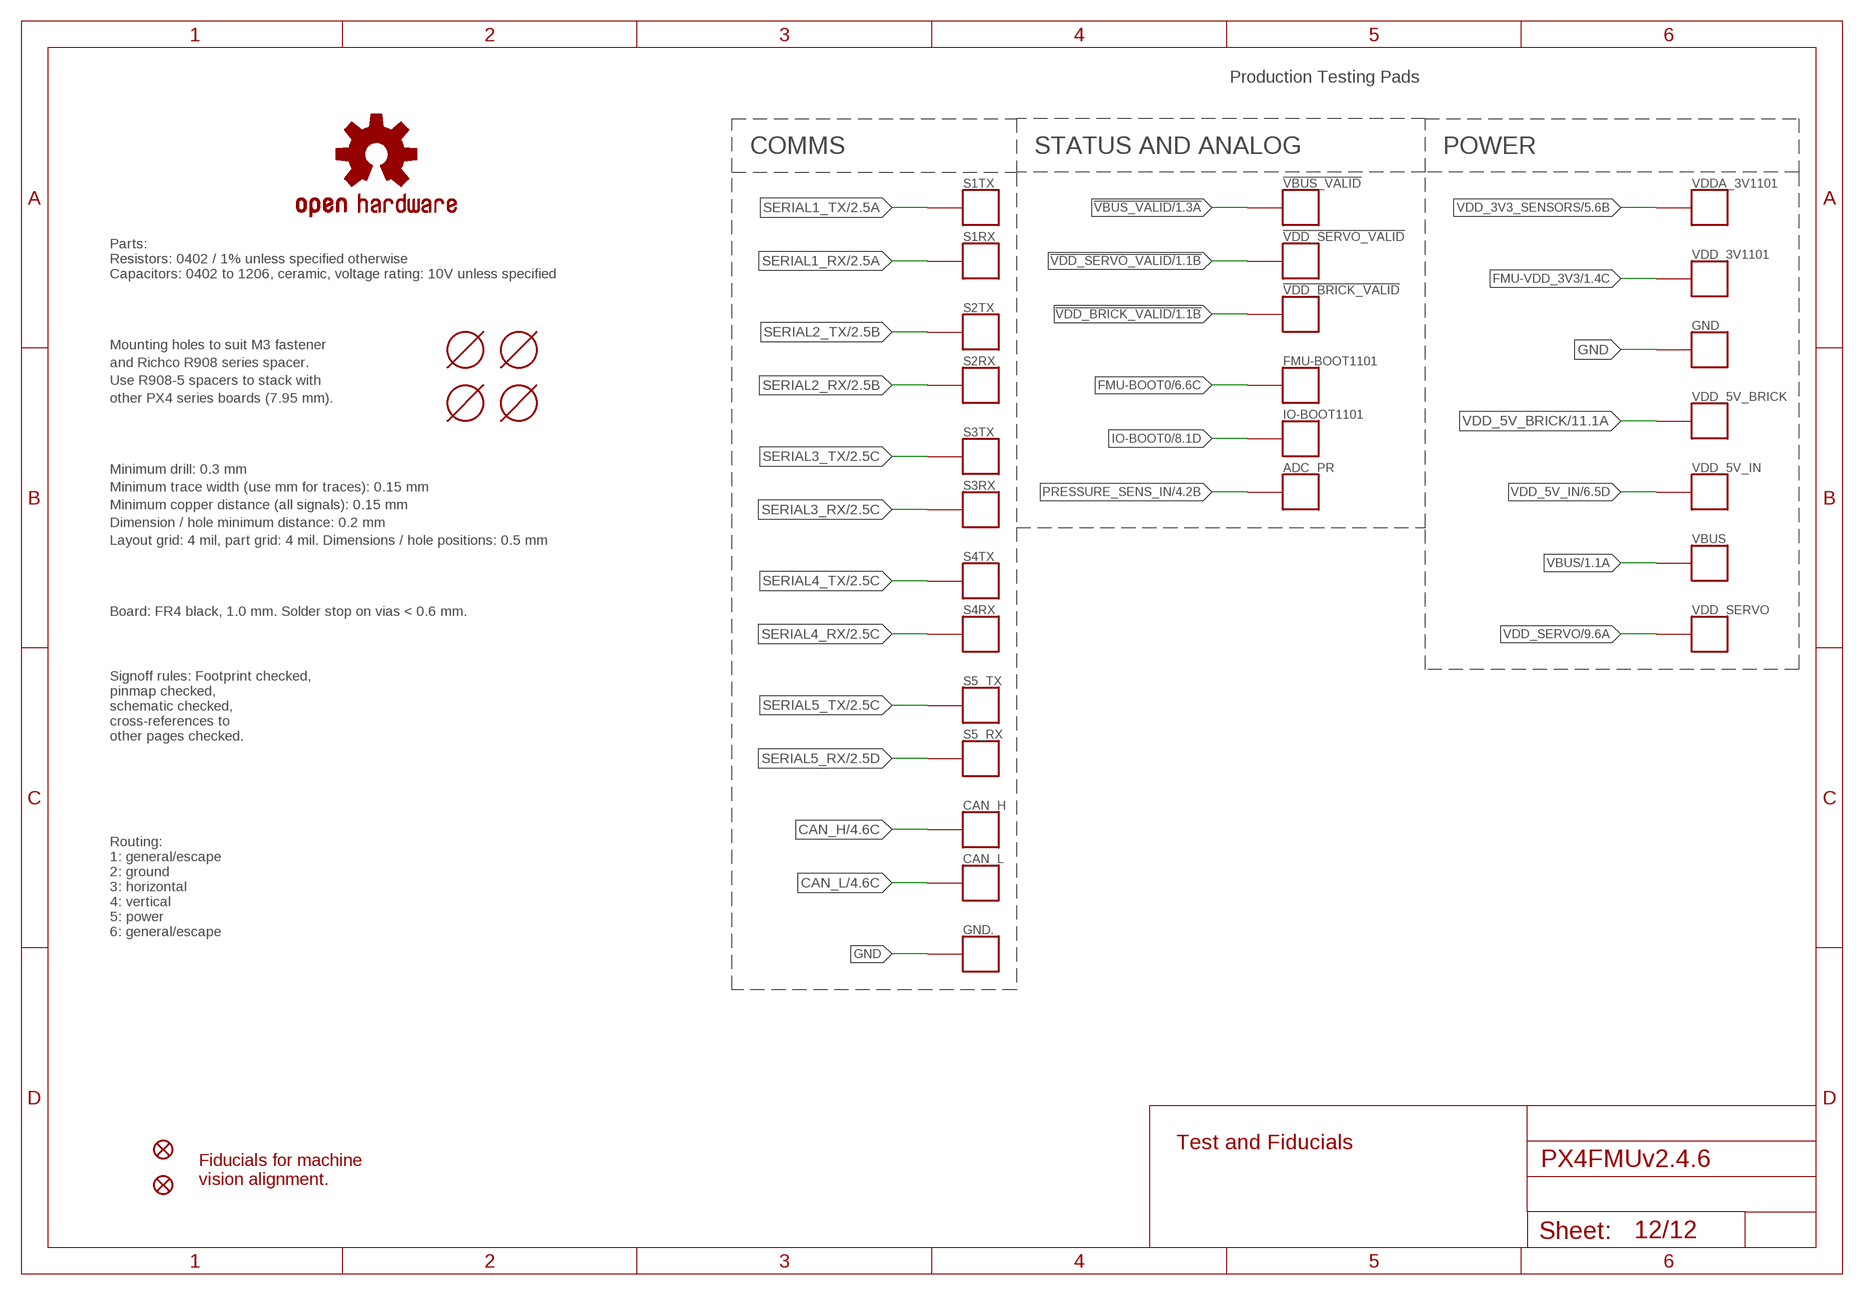
[diagram p11: schematic, sheet 12]

(export (version "E")
  (design (tool "Eeschema 10.0.6"))
  (components
    (comp (ref "C701")
      (value "0u1")
      (footprint "eagle-import:0402-CAP")
      (fields (field (name "PARTNO") "CC0402ZRY5V7BB104"))
      (libsource (lib "eagle-import") (part "CAP0402"))
    )
    (comp (ref "C702")
      (value "1u")
      (footprint "eagle-import:0603-CAP")
      (fields (field (name "PARTNO") "CC0603ZRY5V7BB105"))
      (libsource (lib "eagle-import") (part "CAP0603"))
    )
    (comp (ref "C703")
      (value "5n6")
      (footprint "eagle-import:0402-CAP")
      (fields (field (name "PARTNO") "C0402C562K5RACTU"))
      (libsource (lib "eagle-import") (part "CAP0402"))
    )
    (comp (ref "C704")
      (value "0u47")
      (footprint "eagle-import:0402-CAP")
      (fields (field (name "PARTNO") "C1005X5R1C474K050BC"))
      (libsource (lib "eagle-import") (part "CAP0402"))
    )
    (comp (ref "D701")
      (value "PESD0402-140")
      (footprint "eagle-import:0402-TVS")
      (libsource (lib "eagle-import") (part "DIODE-TVS"))
    )
    (comp (ref "J701")
      (value "DF13C-2P-1.25V")
      (footprint "eagle-import:DF13C-2P-1.25V")
      (fields (field (name "PARTNO") "DF13C-2P-1.25V(20)"))
      (libsource (lib "eagle-import") (part "DF13-2P-1.25V"))
    )
    (comp (ref "J702")
      (value "DF13C-3P-1.25V")
      (footprint "eagle-import:DF13C-3P-1.25V")
      (fields (field (name "PARTNO") "DF13C-3P-1.25V(20)"))
      (libsource (lib "eagle-import") (part "DF13-3P-1.25V"))
    )
    (comp (ref "L701")
      (value "47uH")
      (footprint "eagle-import:0805-IND")
      (fields (field (name "PARTNO") "MLZ2012M470W"))
      (libsource (lib "eagle-import") (part "INDUCTOR0805"))
    )
    (comp (ref "LED701")
      (value "AMBER")
      (footprint "eagle-import:0603-LED")
      (fields (field (name "PARTNO") "APTD1608SECK"))
      (libsource (lib "eagle-import") (part "LED0603"))
    )
    (comp (ref "LED702")
      (value "GREEN")
      (footprint "eagle-import:0603-LED")
      (fields (field (name "PARTNO") "APTD1608CGCK"))
      (libsource (lib "eagle-import") (part "LED0603"))
    )
    (comp (ref "LED703")
      (value "AMBER")
      (footprint "eagle-import:0603-LED")
      (fields (field (name "PARTNO") "APTD1608SECK"))
      (libsource (lib "eagle-import") (part "LED0603"))
    )
    (comp (ref "LED704")
      (value "GREEN")
      (footprint "eagle-import:0603-LED")
      (fields (field (name "PARTNO") "APTD1608CGCK"))
      (libsource (lib "eagle-import") (part "LED0603"))
    )
    (comp (ref "LED705")
      (value "BLUE")
      (footprint "eagle-import:0603-LED")
      (fields (field (name "PARTNO") "APTD1608QBC/D"))
      (libsource (lib "eagle-import") (part "LED0603"))
    )
    (comp (ref "R701")
      (value "9K09")
      (footprint "eagle-import:0402-RES")
      (fields (field (name "PARTNO") "RMCF0402FT9K09"))
      (libsource (lib "eagle-import") (part "RESISTOR0402-RES"))
    )
    (comp (ref "R702")
      (value "10K")
      (footprint "eagle-import:0402-RES")
      (fields (field (name "PARTNO") "RC0402FR-0710KL"))
      (libsource (lib "eagle-import") (part "RESISTOR0402-RES"))
    )
    (comp (ref "R703")
      (value "100K")
      (footprint "eagle-import:0402-RES")
      (fields (field (name "PARTNO") "RC0402FR-07100KL"))
      (libsource (lib "eagle-import") (part "RESISTOR0402-RES"))
    )
    (comp (ref "R704")
      (value "10K")
      (footprint "eagle-import:0402-RES")
      (fields (field (name "PARTNO") "RC0402FR-0710KL"))
      (libsource (lib "eagle-import") (part "RESISTOR0402-RES"))
    )
    (comp (ref "R705")
      (value "453K")
      (footprint "eagle-import:0402-RES")
      (fields (field (name "PARTNO") "RMCF0402FT453K"))
      (libsource (lib "eagle-import") (part "RESISTOR0402-RES"))
    )
    (comp (ref "R706")
      (value "16K5")
      (footprint "eagle-import:0402-RES")
      (fields (field (name "PARTNO") "RMCF0402FT16K5"))
      (libsource (lib "eagle-import") (part "RESISTOR0402-RES"))
    )
    (comp (ref "R707")
      (value "220R")
      (footprint "eagle-import:0402-RES")
      (fields (field (name "PARTNO") "RC0402FR-07220RL"))
      (libsource (lib "eagle-import") (part "RESISTOR0402-RES"))
    )
    (comp (ref "R708")
      (value "220R")
      (footprint "eagle-import:0402-RES")
      (fields (field (name "PARTNO") "RC0402FR-07220RL"))
      (libsource (lib "eagle-import") (part "RESISTOR0402-RES"))
    )
    (comp (ref "R709")
      (value "220R")
      (footprint "eagle-import:0402-RES")
      (fields (field (name "PARTNO") "RC0402FR-07220RL"))
      (libsource (lib "eagle-import") (part "RESISTOR0402-RES"))
    )
    (comp (ref "R710")
      (value "68R")
      (footprint "eagle-import:0402-RES")
      (fields (field (name "PARTNO") "ERJ-2GEJ680X"))
      (libsource (lib "eagle-import") (part "RESISTOR0402-RES"))
    )
    (comp (ref "R711")
      (value "220R")
      (footprint "eagle-import:0402-RES")
      (fields (field (name "PARTNO") "RC0402FR-07220RL"))
      (libsource (lib "eagle-import") (part "RESISTOR0402-RES"))
    )
    (comp (ref "R712")
      (value "220R")
      (footprint "eagle-import:0402-RES")
      (fields (field (name "PARTNO") "RC0402FR-07220RL"))
      (libsource (lib "eagle-import") (part "RESISTOR0402-RES"))
    )
    (comp (ref "R713")
      (value "1K5")
      (footprint "eagle-import:0402-RES")
      (fields (field (name "PARTNO") "RC0402FR-071K5L"))
      (libsource (lib "eagle-import") (part "RESISTOR0402-RES"))
    )
    (comp (ref "R735")
      (value "220R")
      (footprint "eagle-import:0402-RES")
      (fields (field (name "PARTNO") "RC0402FR-07220RL"))
      (libsource (lib "eagle-import") (part "RESISTOR0402-RES"))
    )
    (comp (ref "R736")
      (value "220R")
      (footprint "eagle-import:0402-RES")
      (fields (field (name "PARTNO") "RC0402FR-07220RL"))
      (libsource (lib "eagle-import") (part "RESISTOR0402-RES"))
    )
    (comp (ref "U701")
      (value "TCA62724FMG")
      (footprint "eagle-import:SON10")
      (libsource (lib "eagle-import") (part "TCA62724FMG"))
    )
    (comp (ref "U702")
      (value "LT3469")
      (footprint "eagle-import:SOT23-8")
      (fields (field (name "PARTNO") "LT3469ETS8"))
      (libsource (lib "eagle-import") (part "LT3469"))
    )
    (comp (ref "U703")
      (value "LRTB GFTG-T7AW-1+V7A7-29+R5T9-49-L")
      (footprint "eagle-import:6-PLCC")
      (fields (field (name "PARTNO") "LRTB GFTG-T7AW-1+V7A7-29+R5T9-49-L"))
      (libsource (lib "eagle-import") (part "RGB-LED6-PLCC"))
    )
    (comp (ref "C101")
      (value "0u1")
      (footprint "eagle-import:0402-CAP")
      (fields (field (name "PARTNO") "CC0402ZRY5V7BB104"))
      (libsource (lib "eagle-import") (part "CAP0402"))
    )
    (comp (ref "C102")
      (value "8p")
      (footprint "eagle-import:0402-CAP")
      (fields (field (name "PARTNO") "C1005C0G1H080C"))
      (libsource (lib "eagle-import") (part "CAP0402"))
    )
    (comp (ref "C103")
      (value "8p")
      (footprint "eagle-import:0402-CAP")
      (fields (field (name "PARTNO") "C1005C0G1H080C"))
      (libsource (lib "eagle-import") (part "CAP0402"))
    )
    (comp (ref "R101")
      (value "470R")
      (footprint "eagle-import:0402-RES")
      (fields (field (name "PARTNO") "RC0402FR-07470RL"))
      (libsource (lib "eagle-import") (part "RESISTOR0402-RES"))
    )
    (comp (ref "R102")
      (value "10K")
      (footprint "eagle-import:0402-RES")
      (fields (field (name "PARTNO") "RC0402FR-0710KL"))
      (libsource (lib "eagle-import") (part "RESISTOR0402-RES"))
    )
    (comp (ref "U101")
      (value "STM32F4X7VX")
      (footprint "eagle-import:TQFP100")
      (fields (field (name "PARTNO") "STM32F427VI"))
      (libsource (lib "eagle-import") (part "STM32F4X7VX"))
    )
    (comp (ref "U102")
      (value "FM25V01")
      (footprint "eagle-import:SO08")
      (fields (field (name "PARTNO") "FM25V01-G"))
      (libsource (lib "eagle-import") (part "FM25V01"))
    )
    (comp (ref "X101")
      (value "3.2x2.5 mm / 24 MHz / 15 ppm")
      (footprint "eagle-import:OSCILLATOR-3.2X2.5")
      (fields (field (name "PARTNO") "NX3225SA-24.000000MHZ"))
      (libsource (lib "eagle-import") (part "OSCILLATOR-3.2X2.5"))
    )
    (comp (ref "J301")
      (value "47346-0001")
      (footprint "eagle-import:MOLEX-47346-0001")
      (libsource (lib "eagle-import") (part "MOLEX-47346-0001"))
    )
    (comp (ref "J302")
      (value "DF13C-4P-1.25V")
      (footprint "eagle-import:DF13C-4P-1.25V")
      (fields (field (name "PARTNO") "DF13C-4P-1.25V(20)"))
      (libsource (lib "eagle-import") (part "DF13-4P-1.25V"))
    )
    (comp (ref "JX301")
      (value "ARM_MINI_JTAG-SMT")
      (footprint "eagle-import:FTSH-105-01-XXX-DV-K")
      (fields (field (name "BOM") "EXCLUDE") (field (name "PARTNO") "M50-3900542"))
      (libsource (lib "eagle-import") (part "ARM_MINI_JTAG-SMT"))
    )
    (comp (ref "R301")
      (value "100K")
      (footprint "eagle-import:0402-RES")
      (fields (field (name "PARTNO") "RC0402FR-07100KL"))
      (libsource (lib "eagle-import") (part "RESISTOR0402-RES"))
    )
    (comp (ref "R302")
      (value "100K")
      (footprint "eagle-import:0402-RES")
      (fields (field (name "PARTNO") "RC0402FR-07100KL"))
      (libsource (lib "eagle-import") (part "RESISTOR0402-RES"))
    )
    (comp (ref "R303")
      (value "100K")
      (footprint "eagle-import:0402-RES")
      (fields (field (name "PARTNO") "RC0402FR-07100KL"))
      (libsource (lib "eagle-import") (part "RESISTOR0402-RES"))
    )
    (comp (ref "R304")
      (value "100K")
      (footprint "eagle-import:0402-RES")
      (fields (field (name "PARTNO") "RC0402FR-07100KL"))
      (libsource (lib "eagle-import") (part "RESISTOR0402-RES"))
    )
    (comp (ref "R305")
      (value "100K")
      (footprint "eagle-import:0402-RES")
      (fields (field (name "PARTNO") "RC0402FR-07100KL"))
      (libsource (lib "eagle-import") (part "RESISTOR0402-RES"))
    )
    (comp (ref "R306")
      (value "1K5")
      (footprint "eagle-import:0402-RES")
      (fields (field (name "PARTNO") "RC0402FR-071K5L"))
      (libsource (lib "eagle-import") (part "RESISTOR0402-RES"))
    )
    (comp (ref "R307")
      (value "1K5")
      (footprint "eagle-import:0402-RES")
      (fields (field (name "PARTNO") "RC0402FR-071K5L"))
      (libsource (lib "eagle-import") (part "RESISTOR0402-RES"))
    )
    (comp (ref "U301")
      (value "2908-05WB-MG")
      (footprint "eagle-import:MICROSD")
      (libsource (lib "eagle-import") (part "MICROSDSDI"))
    )
    (comp (ref "U302")
      (value "NUF2042XV6")
      (footprint "eagle-import:SOT563-6")
      (fields (field (name "PARTNO") "NUF2042XV6T1G"))
      (libsource (lib "eagle-import") (part "NUF2042XV6"))
    )
    (comp (ref "C801")
      (value "0u1")
      (footprint "eagle-import:0402-CAP")
      (fields (field (name "PARTNO") "CC0402ZRY5V7BB104"))
      (libsource (lib "eagle-import") (part "CAP0402"))
    )
    (comp (ref "C802")
      (value "0u1")
      (footprint "eagle-import:0402-CAP")
      (fields (field (name "PARTNO") "CC0402ZRY5V7BB104"))
      (libsource (lib "eagle-import") (part "CAP0402"))
    )
    (comp (ref "C803")
      (value "0u1")
      (footprint "eagle-import:0402-CAP")
      (fields (field (name "PARTNO") "CC0402ZRY5V7BB104"))
      (libsource (lib "eagle-import") (part "CAP0402"))
    )
    (comp (ref "C804")
      (value "0u1")
      (footprint "eagle-import:0402-CAP")
      (fields (field (name "PARTNO") "CC0402ZRY5V7BB104"))
      (libsource (lib "eagle-import") (part "CAP0402"))
    )
    (comp (ref "C805")
      (value "8p")
      (footprint "eagle-import:0402-CAP")
      (fields (field (name "PARTNO") "C1005C0G1H080C"))
      (libsource (lib "eagle-import") (part "CAP0402"))
    )
    (comp (ref "C806")
      (value "8p")
      (footprint "eagle-import:0402-CAP")
      (fields (field (name "PARTNO") "C1005C0G1H080C"))
      (libsource (lib "eagle-import") (part "CAP0402"))
    )
    (comp (ref "D801")
      (value "PESD0402-140")
      (footprint "eagle-import:0402-TVS")
      (libsource (lib "eagle-import") (part "DIODE-TVS"))
    )
    (comp (ref "J801")
      (value "JST-ZH-3")
      (footprint "eagle-import:JST-ZH-SMT-VERTICAL")
      (fields (field (name "PARTNO") "B3B-ZR-SM4-TF (LF)(SN)(P)"))
      (libsource (lib "eagle-import") (part "JST-ZH-3"))
    )
    (comp (ref "JX801")
      (value "HEADER-3X1BOARDEDGE-SHORT")
      (footprint "eagle-import:HEADER_3X01_SMD_H_BOARD_EDGE_SHORT")
      (libsource (lib "eagle-import") (part "HEADER-3X1BOARDEDGE-SHORT"))
    )
    (comp (ref "JX802")
      (value "ARM_MINI_JTAG-SMT")
      (footprint "eagle-import:FTSH-105-01-XXX-DV-K")
      (fields (field (name "BOM") "EXCLUDE") (field (name "PARTNO") "M50-3900542"))
      (libsource (lib "eagle-import") (part "ARM_MINI_JTAG-SMT"))
    )
    (comp (ref "R801")
      (value "10K")
      (footprint "eagle-import:0402-RES")
      (fields (field (name "PARTNO") "RC0402FR-0710KL"))
      (libsource (lib "eagle-import") (part "RESISTOR0402-RES"))
    )
    (comp (ref "R802")
      (value "10K")
      (footprint "eagle-import:0402-RES")
      (fields (field (name "PARTNO") "RC0402FR-0710KL"))
      (libsource (lib "eagle-import") (part "RESISTOR0402-RES"))
    )
    (comp (ref "R803")
      (value "220R")
      (footprint "eagle-import:0402-RES")
      (fields (field (name "PARTNO") "RC0402FR-07220RL"))
      (libsource (lib "eagle-import") (part "RESISTOR0402-RES"))
    )
    (comp (ref "R804")
      (value "220R")
      (footprint "eagle-import:0402-RES")
      (fields (field (name "PARTNO") "RC0402FR-07220RL"))
      (libsource (lib "eagle-import") (part "RESISTOR0402-RES"))
    )
    (comp (ref "S801")
      (value "RESET")
      (footprint "eagle-import:EVQP7J01K")
      (fields (field (name "PARTNO") "EVQ-P7J01P"))
      (libsource (lib "eagle-import") (part "SWITCH-MOMENTARY-2"))
    )
    (comp (ref "U801")
      (value "STM32F10XCXT6")
      (footprint "eagle-import:TQFP48")
      (fields (field (name "PARTNO") "STM32F100C8T6B"))
      (libsource (lib "eagle-import") (part "STM32F10XCXT6"))
    )
    (comp (ref "X801")
      (value "3.2x2.5 mm / 24 MHz / 15 ppm")
      (footprint "eagle-import:OSCILLATOR-3.2X2.5")
      (fields (field (name "PARTNO") "NX3225SA-24.000000MHZ"))
      (libsource (lib "eagle-import") (part "OSCILLATOR-3.2X2.5"))
    )
    (comp (ref "C401")
      (value "0u1")
      (footprint "eagle-import:0402-CAP")
      (fields (field (name "PARTNO") "CC0402ZRY5V7BB104"))
      (libsource (lib "eagle-import") (part "CAP0402"))
    )
    (comp (ref "C402")
      (value "0u1")
      (footprint "eagle-import:0402-CAP")
      (fields (field (name "PARTNO") "CC0402ZRY5V7BB104"))
      (libsource (lib "eagle-import") (part "CAP0402"))
    )
    (comp (ref "D401")
      (value "PESD0402-140")
      (footprint "eagle-import:0402-TVS")
      (libsource (lib "eagle-import") (part "DIODE-TVS"))
    )
    (comp (ref "D402")
      (value "PESD0402-140")
      (footprint "eagle-import:0402-TVS")
      (libsource (lib "eagle-import") (part "DIODE-TVS"))
    )
    (comp (ref "D403")
      (value "PESD0402-140")
      (footprint "eagle-import:0402-TVS")
      (libsource (lib "eagle-import") (part "DIODE-TVS"))
    )
    (comp (ref "D404")
      (value "PESD0402-140")
      (footprint "eagle-import:0402-TVS")
      (libsource (lib "eagle-import") (part "DIODE-TVS"))
    )
    (comp (ref "J401")
      (value "DF13C-4P-1.25V")
      (footprint "eagle-import:DF13C-4P-1.25V")
      (fields (field (name "PARTNO") "DF13C-4P-1.25V(20)"))
      (libsource (lib "eagle-import") (part "DF13-4P-1.25V"))
    )
    (comp (ref "J402")
      (value "DF13C-3P-1.25V")
      (footprint "eagle-import:DF13C-3P-1.25V")
      (fields (field (name "PARTNO") "DF13C-3P-1.25V(20)"))
      (libsource (lib "eagle-import") (part "DF13-3P-1.25V"))
    )
    (comp (ref "J403")
      (value "DF13C-7P-1.25V")
      (footprint "eagle-import:DF13C-7P-1.25V")
      (fields (field (name "PARTNO") "DF13C-7P-1.25V(20)"))
      (libsource (lib "eagle-import") (part "DF13-7P-1.25V"))
    )
    (comp (ref "J404")
      (value "DF13C-5P-1.25V")
      (footprint "eagle-import:DF13C-5P-1.25V")
      (fields (field (name "PARTNO") "DF13C-5P-1.25V(20)"))
      (libsource (lib "eagle-import") (part "DF13-5P-1.25V"))
    )
    (comp (ref "J405")
      (value "DF13C-4P-1.25V")
      (footprint "eagle-import:DF13C-4P-1.25V")
      (fields (field (name "PARTNO") "DF13C-4P-1.25V(20)"))
      (libsource (lib "eagle-import") (part "DF13-4P-1.25V"))
    )
    (comp (ref "L401")
      (value "KNH16C104DA5TS")
      (footprint "eagle-import:KYOCERA-KNH16-DA")
      (libsource (lib "eagle-import") (part "KNH16C104DA5TS"))
    )
    (comp (ref "L402")
      (value "KNH16C104DA5TS")
      (footprint "eagle-import:KYOCERA-KNH16-DA")
      (libsource (lib "eagle-import") (part "KNH16C104DA5TS"))
    )
    (comp (ref "L403")
      (value "KNH16C104DA5TS")
      (footprint "eagle-import:KYOCERA-KNH16-DA")
      (libsource (lib "eagle-import") (part "KNH16C104DA5TS"))
    )
    (comp (ref "L404")
      (value "KNH16C104DA5TS")
      (footprint "eagle-import:KYOCERA-KNH16-DA")
      (libsource (lib "eagle-import") (part "KNH16C104DA5TS"))
    )
    (comp (ref "R401")
      (value "1K5")
      (footprint "eagle-import:0402-RES")
      (fields (field (name "PARTNO") "RC0402FR-071K5L"))
      (libsource (lib "eagle-import") (part "RESISTOR0402-RES"))
    )
    (comp (ref "R402")
      (value "1K5")
      (footprint "eagle-import:0402-RES")
      (fields (field (name "PARTNO") "RC0402FR-071K5L"))
      (libsource (lib "eagle-import") (part "RESISTOR0402-RES"))
    )
    (comp (ref "R403")
      (value "10K/0.1%")
      (footprint "eagle-import:0402-RES")
      (fields (field (name "PARTNO") "ERA-2AEB103X"))
      (libsource (lib "eagle-import") (part "RESISTOR0402-RES"))
    )
    (comp (ref "R404")
      (value "120R")
      (footprint "eagle-import:0402-RES")
      (fields (field (name "PARTNO") "RC0402FR-07120RL"))
      (libsource (lib "eagle-import") (part "RESISTOR0402-RES"))
    )
    (comp (ref "R405")
      (value "120R")
      (footprint "eagle-import:0402-RES")
      (fields (field (name "PARTNO") "RC0402FR-07120RL"))
      (libsource (lib "eagle-import") (part "RESISTOR0402-RES"))
    )
    (comp (ref "R406")
      (value "10K/0.1%")
      (footprint "eagle-import:0402-RES")
      (fields (field (name "PARTNO") "ERA-2AEB103X"))
      (libsource (lib "eagle-import") (part "RESISTOR0402-RES"))
    )
    (comp (ref "R407")
      (value "10K/0.1%")
      (footprint "eagle-import:0402-RES")
      (fields (field (name "PARTNO") "ERA-2AEB103X"))
      (libsource (lib "eagle-import") (part "RESISTOR0402-RES"))
    )
    (comp (ref "R408")
      (value "10K/0.1%")
      (footprint "eagle-import:0402-RES")
      (fields (field (name "PARTNO") "ERA-2AEB103X"))
      (libsource (lib "eagle-import") (part "RESISTOR0402-RES"))
    )
    (comp (ref "R409")
      (value "120R")
      (footprint "eagle-import:0402-RES")
      (fields (field (name "PARTNO") "RC0402FR-07120RL"))
      (libsource (lib "eagle-import") (part "RESISTOR0402-RES"))
    )
    (comp (ref "U401")
      (value "MAX3051")
      (footprint "eagle-import:SOT23-8")
      (fields (field (name "PARTNO") "MAX3051EKA"))
      (libsource (lib "eagle-import") (part "MAX3051MAX3051EKA"))
    )
    (comp (ref "B601")
      (value "MS621FE")
      (footprint "eagle-import:MS621FE")
      (fields (field (name "PARTNO") "MS621FE-FL11E"))
      (libsource (lib "eagle-import") (part "MS621FE"))
    )
    (comp (ref "C601")
      (value "10u/25V")
      (footprint "eagle-import:0805-CAP")
      (fields (field (name "PARTNO") "CL21A106KAYNNNE"))
      (libsource (lib "eagle-import") (part "CAP0805"))
    )
    (comp (ref "C602")
      (value "10n")
      (footprint "eagle-import:0402-CAP")
      (fields (field (name "PARTNO") "CC0402KRX7R7BB103"))
      (libsource (lib "eagle-import") (part "CAP0402"))
    )
    (comp (ref "C603")
      (value "1u")
      (footprint "eagle-import:0603-CAP")
      (fields (field (name "PARTNO") "CC0603ZRY5V7BB105"))
      (libsource (lib "eagle-import") (part "CAP0603"))
    )
    (comp (ref "C604")
      (value "22u/25V")
      (footprint "eagle-import:0805-CAP")
      (fields (field (name "PARTNO") "CL21A226MAQNNNE"))
      (libsource (lib "eagle-import") (part "CAP0805"))
    )
    (comp (ref "C605")
      (value "22u/25V")
      (footprint "eagle-import:0805-CAP")
      (fields (field (name "PARTNO") "CL21A226MAQNNNE"))
      (libsource (lib "eagle-import") (part "CAP0805"))
    )
    (comp (ref "C606")
      (value "0u1")
      (footprint "eagle-import:0402-CAP")
      (fields (field (name "PARTNO") "CC0402ZRY5V7BB104"))
      (libsource (lib "eagle-import") (part "CAP0402"))
    )
    (comp (ref "C607")
      (value "0u1")
      (footprint "eagle-import:0402-CAP")
      (fields (field (name "PARTNO") "CC0402ZRY5V7BB104"))
      (libsource (lib "eagle-import") (part "CAP0402"))
    )
    (comp (ref "C608")
      (value "0u1")
      (footprint "eagle-import:0402-CAP")
      (fields (field (name "PARTNO") "CC0402ZRY5V7BB104"))
      (libsource (lib "eagle-import") (part "CAP0402"))
    )
    (comp (ref "C609")
      (value "0u1")
      (footprint "eagle-import:0402-CAP")
      (fields (field (name "PARTNO") "CC0402ZRY5V7BB104"))
      (libsource (lib "eagle-import") (part "CAP0402"))
    )
    (comp (ref "C610")
      (value "0u1")
      (footprint "eagle-import:0402-CAP")
      (fields (field (name "PARTNO") "CC0402ZRY5V7BB104"))
      (libsource (lib "eagle-import") (part "CAP0402"))
    )
    (comp (ref "C611")
      (value "2u2")
      (footprint "eagle-import:0603-CAP")
      (fields (field (name "PARTNO") "C1608X6S1C225K080AC"))
      (libsource (lib "eagle-import") (part "CAP0603"))
    )
    (comp (ref "C612")
      (value "0u1")
      (footprint "eagle-import:0402-CAP")
      (fields (field (name "PARTNO") "CC0402ZRY5V7BB104"))
      (libsource (lib "eagle-import") (part "CAP0402"))
    )
    (comp (ref "C613")
      (value "2u2")
      (footprint "eagle-import:0603-CAP")
      (fields (field (name "PARTNO") "C1608X6S1C225K080AC"))
      (libsource (lib "eagle-import") (part "CAP0603"))
    )
    (comp (ref "C614")
      (value "100u")
      (footprint "eagle-import:1206-CAP")
      (fields (field (name "PARTNO") "C3216X5R1A107M160AC"))
      (libsource (lib "eagle-import") (part "CAP1206"))
    )
    (comp (ref "C615")
      (value "0u1")
      (footprint "eagle-import:0402-CAP")
      (fields (field (name "PARTNO") "CC0402ZRY5V7BB104"))
      (libsource (lib "eagle-import") (part "CAP0402"))
    )
    (comp (ref "C616")
      (value "0u1")
      (footprint "eagle-import:0402-CAP")
      (fields (field (name "PARTNO") "CC0402ZRY5V7BB104"))
      (libsource (lib "eagle-import") (part "CAP0402"))
    )
    (comp (ref "C617")
      (value "0u1")
      (footprint "eagle-import:0402-CAP")
      (fields (field (name "PARTNO") "CC0402ZRY5V7BB104"))
      (libsource (lib "eagle-import") (part "CAP0402"))
    )
    (comp (ref "C618")
      (value "100u")
      (footprint "eagle-import:1206-CAP")
      (fields (field (name "PARTNO") "C3216X5R1A107M160AC"))
      (libsource (lib "eagle-import") (part "CAP1206"))
    )
    (comp (ref "D602")
      (value "RB751V40T1G")
      (footprint "eagle-import:SOD323")
      (libsource (lib "eagle-import") (part "DIODE-SCHOTTKY_SOD323"))
    )
    (comp (ref "L603")
      (value "KNH16C104DA5TS")
      (footprint "eagle-import:KYOCERA-KNH16-DA")
      (libsource (lib "eagle-import") (part "KNH16C104DA5TS"))
    )
    (comp (ref "R602")
      (value "1M")
      (footprint "eagle-import:0402-RES")
      (fields (field (name "PARTNO") "RC0402FR-071ML"))
      (libsource (lib "eagle-import") (part "RESISTOR0402-RES"))
    )
    (comp (ref "R603")
      (value "10K")
      (footprint "eagle-import:0402-RES")
      (fields (field (name "PARTNO") "RC0402FR-0710KL"))
      (libsource (lib "eagle-import") (part "RESISTOR0402-RES"))
    )
    (comp (ref "R604")
      (value "1M")
      (footprint "eagle-import:0402-RES")
      (fields (field (name "PARTNO") "RC0402FR-071ML"))
      (libsource (lib "eagle-import") (part "RESISTOR0402-RES"))
    )
    (comp (ref "R608")
      (value "1K")
      (footprint "eagle-import:0402-RES")
      (fields (field (name "PARTNO") "RC0402FR-071KL"))
      (libsource (lib "eagle-import") (part "RESISTOR0402-RES"))
    )
    (comp (ref "R609")
      (value "10K/0.1%")
      (footprint "eagle-import:0402-RES")
      (fields (field (name "PARTNO") "ERA-2AEB103X"))
      (libsource (lib "eagle-import") (part "RESISTOR0402-RES"))
    )
    (comp (ref "R610")
      (value "10K/0.1%")
      (footprint "eagle-import:0402-RES")
      (fields (field (name "PARTNO") "ERA-2AEB103X"))
      (libsource (lib "eagle-import") (part "RESISTOR0402-RES"))
    )
    (comp (ref "R611")
      (value "10K")
      (footprint "eagle-import:0402-RES")
      (fields (field (name "PARTNO") "RC0402FR-0710KL"))
      (libsource (lib "eagle-import") (part "RESISTOR0402-RES"))
    )
    (comp (ref "R615")
      (value "10K")
      (footprint "eagle-import:0402-RES")
      (fields (field (name "PARTNO") "RC0402FR-0710KL"))
      (libsource (lib "eagle-import") (part "RESISTOR0402-RES"))
    )
    (comp (ref "R616")
      (value "25K5")
      (footprint "eagle-import:0402-RES")
      (fields (field (name "PARTNO") "RMCF0402FT25K5"))
      (libsource (lib "eagle-import") (part "RESISTOR0402-RES"))
    )
    (comp (ref "R617")
      (value "16K5")
      (footprint "eagle-import:0402-RES")
      (fields (field (name "PARTNO") "RMCF0402FT16K5"))
      (libsource (lib "eagle-import") (part "RESISTOR0402-RES"))
    )
    (comp (ref "R621")
      (value "220R")
      (footprint "eagle-import:0603-RES")
      (fields (field (name "PARTNO") "RC1608J100CS"))
      (libsource (lib "eagle-import") (part "RESISTOR0603-RES"))
    )
    (comp (ref "R635")
      (value "10K")
      (footprint "eagle-import:0402-RES")
      (fields (field (name "PARTNO") "RC0402FR-0710KL"))
      (libsource (lib "eagle-import") (part "RESISTOR0402-RES"))
    )
    (comp (ref "S601")
      (value "RESET")
      (footprint "eagle-import:EVQP7J01K")
      (fields (field (name "PARTNO") "EVQ-P7J01P"))
      (libsource (lib "eagle-import") (part "SWITCH-MOMENTARY-2"))
    )
    (comp (ref "U601")
      (value "BQ24315")
      (footprint "eagle-import:QFN8-DSG")
      (fields (field (name "PARTNO") "BQ24315DSGR"))
      (libsource (lib "eagle-import") (part "BQ24315"))
    )
    (comp (ref "U602")
      (value "BQ24315")
      (footprint "eagle-import:QFN8-DSG")
      (fields (field (name "PARTNO") "BQ24315DSGR"))
      (libsource (lib "eagle-import") (part "BQ24315"))
    )
    (comp (ref "U603")
      (value "MIC5332")
      (footprint "eagle-import:MLF-8-EPAD")
      (fields (field (name "PARTNO") "MIC5332-SSYMT"))
      (libsource (lib "eagle-import") (part "MIC5332"))
    )
    (comp (ref "C1101")
      (value "22u/25V")
      (footprint "eagle-import:0805-CAP")
      (fields (field (name "PARTNO") "CL21A226MAQNNNE"))
      (libsource (lib "eagle-import") (part "CAP0805"))
    )
    (comp (ref "C1102")
      (value "22u/25V")
      (footprint "eagle-import:0805-CAP")
      (fields (field (name "PARTNO") "CL21A226MAQNNNE"))
      (libsource (lib "eagle-import") (part "CAP0805"))
    )
    (comp (ref "C1103")
      (value "22u/25V")
      (footprint "eagle-import:0805-CAP")
      (fields (field (name "PARTNO") "CL21A226MAQNNNE"))
      (libsource (lib "eagle-import") (part "CAP0805"))
    )
    (comp (ref "C1104")
      (value "100u")
      (footprint "eagle-import:1206-CAP")
      (fields (field (name "PARTNO") "C3216X5R1A107M160AC"))
      (libsource (lib "eagle-import") (part "CAP1206"))
    )
    (comp (ref "C1105")
      (value "0u1")
      (footprint "eagle-import:0402-CAP")
      (fields (field (name "PARTNO") "C1005X7R1E104K050BB"))
      (libsource (lib "eagle-import") (part "CAP0402"))
    )
    (comp (ref "C1106")
      (value "0u1")
      (footprint "eagle-import:0402-CAP")
      (fields (field (name "PARTNO") "C1005X7R1E104K050BB"))
      (libsource (lib "eagle-import") (part "CAP0402"))
    )
    (comp (ref "C1107")
      (value "0u1")
      (footprint "eagle-import:0402-CAP")
      (fields (field (name "PARTNO") "C1005X7R1E104K050BB"))
      (libsource (lib "eagle-import") (part "CAP0402"))
    )
    (comp (ref "C1108")
      (value "10p/25V")
      (footprint "eagle-import:0402-CAP")
      (fields (field (name "PARTNO") "C0402C100J3GACTU"))
      (libsource (lib "eagle-import") (part "CAP0402"))
    )
    (comp (ref "C1109")
      (value "10p/25V")
      (footprint "eagle-import:0402-CAP")
      (fields (field (name "PARTNO") "C0402C100J3GACTU"))
      (libsource (lib "eagle-import") (part "CAP0402"))
    )
    (comp (ref "C1110")
      (value "10p/25V")
      (footprint "eagle-import:0402-CAP")
      (fields (field (name "PARTNO") "C0402C100J3GACTU"))
      (libsource (lib "eagle-import") (part "CAP0402"))
    )
    (comp (ref "J601")
      (value "DF13C-6P-1.25V")
      (footprint "eagle-import:DF13C-6P-1.25V")
      (fields (field (name "PARTNO") "DF13C-6P-1.25V(20)"))
      (libsource (lib "eagle-import") (part "DF13-6P-1.25V"))
    )
    (comp (ref "L1101")
      (value "KNH16C104DA5TS")
      (footprint "eagle-import:KYOCERA-KNH16-DA")
      (libsource (lib "eagle-import") (part "KNH16C104DA5TS"))
    )
    (comp (ref "L1102")
      (value "KNH16C104DA5TS")
      (footprint "eagle-import:KYOCERA-KNH16-DA")
      (libsource (lib "eagle-import") (part "KNH16C104DA5TS"))
    )
    (comp (ref "R1101")
      (value "10K/0.1%")
      (footprint "eagle-import:0402-RES")
      (fields (field (name "PARTNO") "ERA-2AEB103X"))
      (libsource (lib "eagle-import") (part "RESISTOR0402-RES"))
    )
    (comp (ref "R1102")
      (value "10K/0.1%")
      (footprint "eagle-import:0402-RES")
      (fields (field (name "PARTNO") "ERA-2AEB103X"))
      (libsource (lib "eagle-import") (part "RESISTOR0402-RES"))
    )
    (comp (ref "R1103")
      (value "1M")
      (footprint "eagle-import:0402-RES")
      (fields (field (name "PARTNO") "RC0402FR-071ML"))
      (libsource (lib "eagle-import") (part "RESISTOR0402-RES"))
    )
    (comp (ref "R1104")
      (value "1M")
      (footprint "eagle-import:0402-RES")
      (fields (field (name "PARTNO") "RC0402FR-071ML"))
      (libsource (lib "eagle-import") (part "RESISTOR0402-RES"))
    )
    (comp (ref "R1105")
      (value "453K")
      (footprint "eagle-import:0402-RES")
      (fields (field (name "PARTNO") "RMCF0402FT453K"))
      (libsource (lib "eagle-import") (part "RESISTOR0402-RES"))
    )
    (comp (ref "R1106")
      (value "56K")
      (footprint "eagle-import:0402-RES")
      (fields (field (name "PARTNO") "ERA-2AEB563X"))
      (libsource (lib "eagle-import") (part "RESISTOR0402-RES"))
    )
    (comp (ref "R1107")
      (value "105K")
      (footprint "eagle-import:0402-RES")
      (fields (field (name "PARTNO") "ERJ-2RKF1053X"))
      (libsource (lib "eagle-import") (part "RESISTOR0402-RES"))
    )
    (comp (ref "R1109")
      (value "453K")
      (footprint "eagle-import:0402-RES")
      (fields (field (name "PARTNO") "RMCF0402FT453K"))
      (libsource (lib "eagle-import") (part "RESISTOR0402-RES"))
    )
    (comp (ref "R1110")
      (value "56K")
      (footprint "eagle-import:0402-RES")
      (fields (field (name "PARTNO") "ERA-2AEB563X"))
      (libsource (lib "eagle-import") (part "RESISTOR0402-RES"))
    )
    (comp (ref "R1111")
      (value "105K")
      (footprint "eagle-import:0402-RES")
      (fields (field (name "PARTNO") "ERJ-2RKF1053X"))
      (libsource (lib "eagle-import") (part "RESISTOR0402-RES"))
    )
    (comp (ref "R1112")
      (value "453K")
      (footprint "eagle-import:0402-RES")
      (fields (field (name "PARTNO") "RMCF0402FT453K"))
      (libsource (lib "eagle-import") (part "RESISTOR0402-RES"))
    )
    (comp (ref "R1113")
      (value "56K")
      (footprint "eagle-import:0402-RES")
      (fields (field (name "PARTNO") "ERA-2AEB563X"))
      (libsource (lib "eagle-import") (part "RESISTOR0402-RES"))
    )
    (comp (ref "R1114")
      (value "105K")
      (footprint "eagle-import:0402-RES")
      (fields (field (name "PARTNO") "ERJ-2RKF1053X"))
      (libsource (lib "eagle-import") (part "RESISTOR0402-RES"))
    )
    (comp (ref "R1115")
      (value "0R")
      (footprint "eagle-import:0402-RES")
      (fields (field (name "PARTNO") "ERJ-2GE0R00X"))
      (libsource (lib "eagle-import") (part "RESISTOR0402-RES"))
    )
    (comp (ref "RN1101")
      (value "1M")
      (footprint "eagle-import:EXB28V")
      (fields (field (name "PARTNO") "EXB-28V105JX"))
      (libsource (lib "eagle-import") (part "4R-NEXB28V"))
    )
    (comp (ref "U1101")
      (value "LTC4417")
      (footprint "eagle-import:MO-220")
      (fields (field (name "PARTNO") "LTC4417IUF#PBF"))
      (libsource (lib "eagle-import") (part "LTC4117"))
    )
    (comp (ref "U1102")
      (value "NTHD4102PT1G")
      (footprint "eagle-import:1206-8")
      (fields (field (name "PARTNO") "NTHD4102PT1G"))
      (libsource (lib "eagle-import") (part "MOSFET-DUAL-PCHANNEL-CHIPFET"))
    )
    (comp (ref "U1103")
      (value "NTHD4102PT1G")
      (footprint "eagle-import:1206-8")
      (fields (field (name "PARTNO") "NTHD4102PT1G"))
      (libsource (lib "eagle-import") (part "MOSFET-DUAL-PCHANNEL-CHIPFET"))
    )
    (comp (ref "U1104")
      (value "NTHD4102PT1G")
      (footprint "eagle-import:1206-8")
      (fields (field (name "PARTNO") "NTHD4102PT1G"))
      (libsource (lib "eagle-import") (part "MOSFET-DUAL-PCHANNEL-CHIPFET"))
    )
    (comp (ref "C1001")
      (value "10u/25V")
      (footprint "eagle-import:0805-CAP")
      (fields (field (name "PARTNO") "CL21A106KAYNNNE"))
      (libsource (lib "eagle-import") (part "CAP0805"))
    )
    (comp (ref "C1002")
      (value "10n")
      (footprint "eagle-import:0402-CAP")
      (fields (field (name "PARTNO") "CC0402KRX7R7BB103"))
      (libsource (lib "eagle-import") (part "CAP0402"))
    )
    (comp (ref "C1003")
      (value "1u")
      (footprint "eagle-import:0603-CAP")
      (fields (field (name "PARTNO") "CC0603ZRY5V7BB105"))
      (libsource (lib "eagle-import") (part "CAP0603"))
    )
    (comp (ref "C1004")
      (value "10u")
      (footprint "eagle-import:0603-CAP")
      (fields (field (name "PARTNO") "C1608X5R1A106K080AC"))
      (libsource (lib "eagle-import") (part "CAP0603"))
    )
    (comp (ref "C1005")
      (value "0u1")
      (footprint "eagle-import:0402-CAP")
      (fields (field (name "PARTNO") "CC0402ZRY5V7BB104"))
      (libsource (lib "eagle-import") (part "CAP0402"))
    )
    (comp (ref "C1008")
      (value "2u2")
      (footprint "eagle-import:0402-CAP")
      (fields (field (name "PARTNO") "C1005X6S1C225K050BC"))
      (libsource (lib "eagle-import") (part "CAP0402"))
    )
    (comp (ref "D1001")
      (value "PMEG2005CT")
      (footprint "eagle-import:SOT23-3")
      (libsource (lib "eagle-import") (part "PMEG2005CT"))
    )
    (comp (ref "F1001")
      (value "0ZCA0035FF2G")
      (footprint "eagle-import:PTC-1206")
      (libsource (lib "eagle-import") (part "PTCSMD"))
    )
    (comp (ref "R1001")
      (value "100K")
      (footprint "eagle-import:0402-RES")
      (fields (field (name "PARTNO") "RC0402FR-07100KL"))
      (libsource (lib "eagle-import") (part "RESISTOR0402-RES"))
    )
    (comp (ref "R1002")
      (value "10K")
      (footprint "eagle-import:0402-RES")
      (fields (field (name "PARTNO") "RC0402FR-0710KL"))
      (libsource (lib "eagle-import") (part "RESISTOR0402-RES"))
    )
    (comp (ref "U1001")
      (value "BQ24313")
      (footprint "eagle-import:QFN8-DSG")
      (fields (field (name "PARTNO") "BQ24313DSGT"))
      (libsource (lib "eagle-import") (part "BQ24313"))
    )
    (comp (ref "U1002")
      (value "MIC5332")
      (footprint "eagle-import:MLF-8-EPAD")
      (fields (field (name "PARTNO") "MIC5332-SSYMT"))
      (libsource (lib "eagle-import") (part "MIC5332"))
    )
    (comp (ref "C201")
      (value "0u1")
      (footprint "eagle-import:0402-CAP")
      (fields (field (name "PARTNO") "CC0402ZRY5V7BB104"))
      (libsource (lib "eagle-import") (part "CAP0402"))
    )
    (comp (ref "C202")
      (value "0u1")
      (footprint "eagle-import:0402-CAP")
      (fields (field (name "PARTNO") "CC0402ZRY5V7BB104"))
      (libsource (lib "eagle-import") (part "CAP0402"))
    )
    (comp (ref "D201")
      (value "PESD0402-140")
      (footprint "eagle-import:0402-TVS")
      (libsource (lib "eagle-import") (part "DIODE-TVS"))
    )
    (comp (ref "D202")
      (value "PESD0402-140")
      (footprint "eagle-import:0402-TVS")
      (libsource (lib "eagle-import") (part "DIODE-TVS"))
    )
    (comp (ref "D203")
      (value "PESD0402-140")
      (footprint "eagle-import:0402-TVS")
      (libsource (lib "eagle-import") (part "DIODE-TVS"))
    )
    (comp (ref "J201")
      (value "DF13C-6P-1.25V")
      (footprint "eagle-import:DF13C-6P-1.25V")
      (fields (field (name "PARTNO") "DF13C-6P-1.25V(20)"))
      (libsource (lib "eagle-import") (part "DF13-6P-1.25V"))
    )
    (comp (ref "J202")
      (value "DF13C-6P-1.25V")
      (footprint "eagle-import:DF13C-6P-1.25V")
      (fields (field (name "PARTNO") "DF13C-6P-1.25V(20)"))
      (libsource (lib "eagle-import") (part "DF13-6P-1.25V"))
    )
    (comp (ref "J203")
      (value "DF13C-6P-1.25V")
      (footprint "eagle-import:DF13C-6P-1.25V")
      (fields (field (name "PARTNO") "DF13C-6P-1.25V(20)"))
      (libsource (lib "eagle-import") (part "DF13-6P-1.25V"))
    )
    (comp (ref "J204")
      (value "DF13C-6P-1.25V")
      (footprint "eagle-import:DF13C-6P-1.25V")
      (fields (field (name "PARTNO") "DF13C-6P-1.25V(20)"))
      (libsource (lib "eagle-import") (part "DF13-6P-1.25V"))
    )
    (comp (ref "L201")
      (value "KNH16C104DA5TS")
      (footprint "eagle-import:KYOCERA-KNH16-DA")
      (libsource (lib "eagle-import") (part "KNH16C104DA5TS"))
    )
    (comp (ref "L202")
      (value "KNH16C104DA5TS")
      (footprint "eagle-import:KYOCERA-KNH16-DA")
      (libsource (lib "eagle-import") (part "KNH16C104DA5TS"))
    )
    (comp (ref "L203")
      (value "KNH16C104DA5TS")
      (footprint "eagle-import:KYOCERA-KNH16-DA")
      (libsource (lib "eagle-import") (part "KNH16C104DA5TS"))
    )
    (comp (ref "R201")
      (value "120R")
      (footprint "eagle-import:0402-RES")
      (fields (field (name "PARTNO") "RC0402FR-07120RL"))
      (libsource (lib "eagle-import") (part "RESISTOR0402-RES"))
    )
    (comp (ref "R202")
      (value "120R")
      (footprint "eagle-import:0402-RES")
      (fields (field (name "PARTNO") "RC0402FR-07120RL"))
      (libsource (lib "eagle-import") (part "RESISTOR0402-RES"))
    )
    (comp (ref "R203")
      (value "120R")
      (footprint "eagle-import:0402-RES")
      (fields (field (name "PARTNO") "RC0402FR-07120RL"))
      (libsource (lib "eagle-import") (part "RESISTOR0402-RES"))
    )
    (comp (ref "R204")
      (value "120R")
      (footprint "eagle-import:0402-RES")
      (fields (field (name "PARTNO") "RC0402FR-07120RL"))
      (libsource (lib "eagle-import") (part "RESISTOR0402-RES"))
    )
    (comp (ref "R205")
      (value "120R")
      (footprint "eagle-import:0402-RES")
      (fields (field (name "PARTNO") "RC0402FR-07120RL"))
      (libsource (lib "eagle-import") (part "RESISTOR0402-RES"))
    )
    (comp (ref "R206")
      (value "120R")
      (footprint "eagle-import:0402-RES")
      (fields (field (name "PARTNO") "RC0402FR-07120RL"))
      (libsource (lib "eagle-import") (part "RESISTOR0402-RES"))
    )
    (comp (ref "R207")
      (value "120R")
      (footprint "eagle-import:0402-RES")
      (fields (field (name "PARTNO") "RC0402FR-07120RL"))
      (libsource (lib "eagle-import") (part "RESISTOR0402-RES"))
    )
    (comp (ref "R208")
      (value "120R")
      (footprint "eagle-import:0402-RES")
      (fields (field (name "PARTNO") "RC0402FR-07120RL"))
      (libsource (lib "eagle-import") (part "RESISTOR0402-RES"))
    )
    (comp (ref "R209")
      (value "120R")
      (footprint "eagle-import:0402-RES")
      (fields (field (name "PARTNO") "RC0402FR-07120RL"))
      (libsource (lib "eagle-import") (part "RESISTOR0402-RES"))
    )
    (comp (ref "R210")
      (value "120R")
      (footprint "eagle-import:0402-RES")
      (fields (field (name "PARTNO") "RC0402FR-07120RL"))
      (libsource (lib "eagle-import") (part "RESISTOR0402-RES"))
    )
    (comp (ref "R211")
      (value "120R")
      (footprint "eagle-import:0402-RES")
      (fields (field (name "PARTNO") "RC0402FR-07120RL"))
      (libsource (lib "eagle-import") (part "RESISTOR0402-RES"))
    )
    (comp (ref "R212")
      (value "120R")
      (footprint "eagle-import:0402-RES")
      (fields (field (name "PARTNO") "RC0402FR-07120RL"))
      (libsource (lib "eagle-import") (part "RESISTOR0402-RES"))
    )
    (comp (ref "R213")
      (value "120R")
      (footprint "eagle-import:0402-RES")
      (fields (field (name "PARTNO") "RC0402FR-07120RL"))
      (libsource (lib "eagle-import") (part "RESISTOR0402-RES"))
    )
    (comp (ref "R214")
      (value "120R")
      (footprint "eagle-import:0402-RES")
      (fields (field (name "PARTNO") "RC0402FR-07120RL"))
      (libsource (lib "eagle-import") (part "RESISTOR0402-RES"))
    )
    (comp (ref "R215")
      (value "120R")
      (footprint "eagle-import:0402-RES")
      (fields (field (name "PARTNO") "RC0402FR-07120RL"))
      (libsource (lib "eagle-import") (part "RESISTOR0402-RES"))
    )
    (comp (ref "R216")
      (value "120R")
      (footprint "eagle-import:0402-RES")
      (fields (field (name "PARTNO") "RC0402FR-07120RL"))
      (libsource (lib "eagle-import") (part "RESISTOR0402-RES"))
    )
    (comp (ref "U201")
      (value "TXS0108QFN20")
      (footprint "eagle-import:QFN20-RGY")
      (fields (field (name "PARTNO") "TXS0108ERGYR"))
      (libsource (lib "eagle-import") (part "TXS0108QFN20"))
    )
    (comp (ref "U202")
      (value "TXS0108QFN20")
      (footprint "eagle-import:QFN20-RGY")
      (fields (field (name "PARTNO") "TXS0108ERGYR"))
      (libsource (lib "eagle-import") (part "TXS0108QFN20"))
    )
    (comp (ref "!VBUS_VALID")
      (value "PAD.04")
      (footprint "eagle-import:PAD.04X.04")
      (libsource (lib "eagle-import") (part "PAD.04"))
    )
    (comp (ref "!VDD_BRICK_VALID")
      (value "PAD.04")
      (footprint "eagle-import:PAD.04X.04")
      (libsource (lib "eagle-import") (part "PAD.04"))
    )
    (comp (ref "!VDD_SERVO_VALID")
      (value "PAD.04")
      (footprint "eagle-import:PAD.04X.04")
      (libsource (lib "eagle-import") (part "PAD.04"))
    )
    (comp (ref "ADC_PR")
      (value "PAD.04")
      (footprint "eagle-import:PAD.04X.04")
      (libsource (lib "eagle-import") (part "PAD.04"))
    )
    (comp (ref "CAN_H")
      (value "PAD.04")
      (footprint "eagle-import:PAD.04X.04")
      (libsource (lib "eagle-import") (part "PAD.04"))
    )
    (comp (ref "CAN_L")
      (value "PAD.04")
      (footprint "eagle-import:PAD.04X.04")
      (libsource (lib "eagle-import") (part "PAD.04"))
    )
    (comp (ref "FMU-BOOT1101")
      (value "PAD.04")
      (footprint "eagle-import:PAD.04X.04")
      (libsource (lib "eagle-import") (part "PAD.04"))
    )
    (comp (ref "GND")
      (value "PAD.04")
      (footprint "eagle-import:PAD.04X.04")
      (libsource (lib "eagle-import") (part "PAD.04"))
    )
    (comp (ref "GND.")
      (value "PAD.04")
      (footprint "eagle-import:PAD.04X.04")
      (libsource (lib "eagle-import") (part "PAD.04"))
    )
    (comp (ref "IO-BOOT1101")
      (value "PAD.04")
      (footprint "eagle-import:PAD.04X.04")
      (libsource (lib "eagle-import") (part "PAD.04"))
    )
    (comp (ref "JP1")
      (value "FIDUCIAL1.5X3")
      (footprint "eagle-import:FIDUCIAL-1.5X3")
      (libsource (lib "eagle-import") (part "FIDUCIAL1.5X3"))
    )
    (comp (ref "JP2")
      (value "FIDUCIAL1.5X3")
      (footprint "eagle-import:FIDUCIAL-1.5X3")
      (libsource (lib "eagle-import") (part "FIDUCIAL1.5X3"))
    )
    (comp (ref "M3_MOUNT1101")
      (value "MOUNT-HOLE3.1MM")
      (footprint "eagle-import:MOUNT-HOLE3.1")
      (libsource (lib "eagle-import") (part "MOUNT-HOLE3.1MM"))
    )
    (comp (ref "M3_MOUNT1102")
      (value "MOUNT-HOLE3.1MM")
      (footprint "eagle-import:MOUNT-HOLE3.1")
      (libsource (lib "eagle-import") (part "MOUNT-HOLE3.1MM"))
    )
    (comp (ref "M3_MOUNT1103")
      (value "MOUNT-HOLE3.1MM")
      (footprint "eagle-import:MOUNT-HOLE3.1")
      (libsource (lib "eagle-import") (part "MOUNT-HOLE3.1MM"))
    )
    (comp (ref "M3_MOUNT1104")
      (value "MOUNT-HOLE3.1MM")
      (footprint "eagle-import:MOUNT-HOLE3.1")
      (libsource (lib "eagle-import") (part "MOUNT-HOLE3.1MM"))
    )
    (comp (ref "OSHW_LOGO")
      (value "OSHW-LOGOS")
      (footprint "eagle-import:OSHW-LOGO-S")
      (libsource (lib "eagle-import") (part "OSHW-LOGOS"))
    )
    (comp (ref "S1RX")
      (value "PAD.04")
      (footprint "eagle-import:PAD.04X.04")
      (libsource (lib "eagle-import") (part "PAD.04"))
    )
    (comp (ref "S1TX")
      (value "PAD.04")
      (footprint "eagle-import:PAD.04X.04")
      (libsource (lib "eagle-import") (part "PAD.04"))
    )
    (comp (ref "S2RX")
      (value "PAD.04")
      (footprint "eagle-import:PAD.04X.04")
      (libsource (lib "eagle-import") (part "PAD.04"))
    )
    (comp (ref "S2TX")
      (value "PAD.04")
      (footprint "eagle-import:PAD.04X.04")
      (libsource (lib "eagle-import") (part "PAD.04"))
    )
    (comp (ref "S3RX")
      (value "PAD.04")
      (footprint "eagle-import:PAD.04X.04")
      (libsource (lib "eagle-import") (part "PAD.04"))
    )
    (comp (ref "S3TX")
      (value "PAD.04")
      (footprint "eagle-import:PAD.04X.04")
      (libsource (lib "eagle-import") (part "PAD.04"))
    )
    (comp (ref "S4RX")
      (value "PAD.04")
      (footprint "eagle-import:PAD.04X.04")
      (libsource (lib "eagle-import") (part "PAD.04"))
    )
    (comp (ref "S4TX")
      (value "PAD.04")
      (footprint "eagle-import:PAD.04X.04")
      (libsource (lib "eagle-import") (part "PAD.04"))
    )
    (comp (ref "S5_RX")
      (value "PAD.04")
      (footprint "eagle-import:PAD.04X.04")
      (libsource (lib "eagle-import") (part "PAD.04"))
    )
    (comp (ref "S5_TX")
      (value "PAD.04")
      (footprint "eagle-import:PAD.04X.04")
      (libsource (lib "eagle-import") (part "PAD.04"))
    )
    (comp (ref "VBUS")
      (value "PAD.04")
      (footprint "eagle-import:PAD.04X.04")
      (libsource (lib "eagle-import") (part "PAD.04"))
    )
    (comp (ref "VDDA_3V1101")
      (value "PAD.04")
      (footprint "eagle-import:PAD.04X.04")
      (libsource (lib "eagle-import") (part "PAD.04"))
    )
    (comp (ref "VDD_3V1101")
      (value "PAD.04")
      (footprint "eagle-import:PAD.04X.04")
      (libsource (lib "eagle-import") (part "PAD.04"))
    )
    (comp (ref "VDD_5V_BRICK")
      (value "PAD.04")
      (footprint "eagle-import:PAD.04X.04")
      (libsource (lib "eagle-import") (part "PAD.04"))
    )
    (comp (ref "VDD_5V_IN")
      (value "PAD.04")
      (footprint "eagle-import:PAD.04X.04")
      (libsource (lib "eagle-import") (part "PAD.04"))
    )
    (comp (ref "VDD_SERVO")
      (value "PAD.04")
      (footprint "eagle-import:PAD.04X.04")
      (libsource (lib "eagle-import") (part "PAD.04"))
    )
    (comp (ref "C901")
      (value "0u1")
      (footprint "eagle-import:0402-CAP")
      (fields (field (name "PARTNO") "CC0402ZRY5V7BB104"))
      (libsource (lib "eagle-import") (part "CAP0402"))
    )
    (comp (ref "C902")
      (value "0u1")
      (footprint "eagle-import:0402-CAP")
      (fields (field (name "PARTNO") "CC0402ZRY5V7BB104"))
      (libsource (lib "eagle-import") (part "CAP0402"))
    )
    (comp (ref "C903")
      (value "0u1")
      (footprint "eagle-import:0402-CAP")
      (fields (field (name "PARTNO") "CC0402ZRY5V7BB104"))
      (libsource (lib "eagle-import") (part "CAP0402"))
    )
    (comp (ref "D901")
      (value "PESD0402-140")
      (footprint "eagle-import:0402-TVS")
      (libsource (lib "eagle-import") (part "DIODE-TVS"))
    )
    (comp (ref "D902")
      (value "PESD0402-140")
      (footprint "eagle-import:0402-TVS")
      (libsource (lib "eagle-import") (part "DIODE-TVS"))
    )
    (comp (ref "D903")
      (value "PESD0402-140")
      (footprint "eagle-import:0402-TVS")
      (libsource (lib "eagle-import") (part "DIODE-TVS"))
    )
    (comp (ref "D904")
      (value "MSS1P4-M3")
      (footprint "eagle-import:MICROSMP")
      (fields (field (name "PARTNO") "MSS1P4-M3/89A"))
      (libsource (lib "eagle-import") (part "DIODE-SCHOTTKY_MSMP"))
    )
    (comp (ref "J901")
      (value "HEADER-3X163X16RA")
      (footprint "eagle-import:3X16RA")
      (fields (field (name "BOM") "EXCLUDE"))
      (libsource (lib "eagle-import") (part "HEADER-3X163X16RA"))
    )
    (comp (ref "L901")
      (value "KNH16C104DA5TS")
      (footprint "eagle-import:KYOCERA-KNH16-DA")
      (libsource (lib "eagle-import") (part "KNH16C104DA5TS"))
    )
    (comp (ref "R901")
      (value "10K")
      (footprint "eagle-import:0402-RES")
      (fields (field (name "PARTNO") "RC0402FR-0710KL"))
      (libsource (lib "eagle-import") (part "RESISTOR0402-RES"))
    )
    (comp (ref "R902")
      (value "220R")
      (footprint "eagle-import:0402-RES")
      (fields (field (name "PARTNO") "RC0402FR-07220RL"))
      (libsource (lib "eagle-import") (part "RESISTOR0402-RES"))
    )
    (comp (ref "R903")
      (value "220R")
      (footprint "eagle-import:0402-RES")
      (fields (field (name "PARTNO") "RC0402FR-07220RL"))
      (libsource (lib "eagle-import") (part "RESISTOR0402-RES"))
    )
    (comp (ref "R904")
      (value "220R")
      (footprint "eagle-import:0402-RES")
      (fields (field (name "PARTNO") "RC0402FR-07220RL"))
      (libsource (lib "eagle-import") (part "RESISTOR0402-RES"))
    )
    (comp (ref "R905")
      (value "220R")
      (footprint "eagle-import:0402-RES")
      (fields (field (name "PARTNO") "RC0402FR-07220RL"))
      (libsource (lib "eagle-import") (part "RESISTOR0402-RES"))
    )
    (comp (ref "R906")
      (value "220R")
      (footprint "eagle-import:0402-RES")
      (fields (field (name "PARTNO") "RC0402FR-07220RL"))
      (libsource (lib "eagle-import") (part "RESISTOR0402-RES"))
    )
    (comp (ref "R907")
      (value "220R")
      (footprint "eagle-import:0402-RES")
      (fields (field (name "PARTNO") "RC0402FR-07220RL"))
      (libsource (lib "eagle-import") (part "RESISTOR0402-RES"))
    )
    (comp (ref "R908")
      (value "220R")
      (footprint "eagle-import:0402-RES")
      (fields (field (name "PARTNO") "RC0402FR-07220RL"))
      (libsource (lib "eagle-import") (part "RESISTOR0402-RES"))
    )
    (comp (ref "R909")
      (value "220R")
      (footprint "eagle-import:0402-RES")
      (fields (field (name "PARTNO") "RC0402FR-07220RL"))
      (libsource (lib "eagle-import") (part "RESISTOR0402-RES"))
    )
    (comp (ref "R910")
      (value "220R")
      (footprint "eagle-import:0402-RES")
      (fields (field (name "PARTNO") "RC0402FR-07220RL"))
      (libsource (lib "eagle-import") (part "RESISTOR0402-RES"))
    )
    (comp (ref "R911")
      (value "220R")
      (footprint "eagle-import:0402-RES")
      (fields (field (name "PARTNO") "RC0402FR-07220RL"))
      (libsource (lib "eagle-import") (part "RESISTOR0402-RES"))
    )
    (comp (ref "R912")
      (value "220R")
      (footprint "eagle-import:0402-RES")
      (fields (field (name "PARTNO") "RC0402FR-07220RL"))
      (libsource (lib "eagle-import") (part "RESISTOR0402-RES"))
    )
    (comp (ref "R913")
      (value "220R")
      (footprint "eagle-import:0402-RES")
      (fields (field (name "PARTNO") "RC0402FR-07220RL"))
      (libsource (lib "eagle-import") (part "RESISTOR0402-RES"))
    )
    (comp (ref "R914")
      (value "220R")
      (footprint "eagle-import:0402-RES")
      (fields (field (name "PARTNO") "RC0402FR-07220RL"))
      (libsource (lib "eagle-import") (part "RESISTOR0402-RES"))
    )
    (comp (ref "R915")
      (value "220R")
      (footprint "eagle-import:0402-RES")
      (fields (field (name "PARTNO") "RC0402FR-07220RL"))
      (libsource (lib "eagle-import") (part "RESISTOR0402-RES"))
    )
    (comp (ref "R916")
      (value "220R")
      (footprint "eagle-import:0402-RES")
      (fields (field (name "PARTNO") "RC0402FR-07220RL"))
      (libsource (lib "eagle-import") (part "RESISTOR0402-RES"))
    )
    (comp (ref "R917")
      (value "220R")
      (footprint "eagle-import:0402-RES")
      (fields (field (name "PARTNO") "RC0402FR-07220RL"))
      (libsource (lib "eagle-import") (part "RESISTOR0402-RES"))
    )
    (comp (ref "R918")
      (value "10K/0.1%")
      (footprint "eagle-import:0402-RES")
      (fields (field (name "PARTNO") "ERA-2AEB103X"))
      (libsource (lib "eagle-import") (part "RESISTOR0402-RES"))
    )
    (comp (ref "R919")
      (value "10K/0.1%")
      (footprint "eagle-import:0402-RES")
      (fields (field (name "PARTNO") "ERA-2AEB103X"))
      (libsource (lib "eagle-import") (part "RESISTOR0402-RES"))
    )
    (comp (ref "R922")
      (value "10K/0.1%")
      (footprint "eagle-import:0402-RES")
      (fields (field (name "PARTNO") "ERA-2AEB103X"))
      (libsource (lib "eagle-import") (part "RESISTOR0402-RES"))
    )
    (comp (ref "U901")
      (value "TXS0108QFN20")
      (footprint "eagle-import:QFN20-RGY")
      (fields (field (name "PARTNO") "TXS0108ERGYR"))
      (libsource (lib "eagle-import") (part "TXS0108QFN20"))
    )
    (comp (ref "U902")
      (value "TXS0108QFN20")
      (footprint "eagle-import:QFN20-RGY")
      (fields (field (name "PARTNO") "TXS0108ERGYR"))
      (libsource (lib "eagle-import") (part "TXS0108QFN20"))
    )
    (comp (ref "U903")
      (value "74LVC2G240")
      (footprint "eagle-import:TSSOP8_SOT505-2")
      (fields (field (name "PARTNO") "74LVC2G240DP,125"))
      (libsource (lib "eagle-import") (part "74LVC2G240-TSSOP-8"))
    )
    (comp (ref "C501")
      (value "10u/10V")
      (footprint "eagle-import:0805-CAP")
      (fields (field (name "PARTNO") "CC0805ZKY5V6BB106"))
      (libsource (lib "eagle-import") (part "CAP0805"))
    )
    (comp (ref "C502")
      (value "0u1")
      (footprint "eagle-import:0402-CAP")
      (fields (field (name "PARTNO") "CC0402ZRY5V7BB104"))
      (libsource (lib "eagle-import") (part "CAP0402"))
    )
    (comp (ref "C503")
      (value "0u1")
      (footprint "eagle-import:0402-CAP")
      (fields (field (name "PARTNO") "CC0402ZRY5V7BB104"))
      (libsource (lib "eagle-import") (part "CAP0402"))
    )
    (comp (ref "C504")
      (value "10n")
      (footprint "eagle-import:0402-CAP")
      (fields (field (name "PARTNO") "CC0402KRX7R7BB103"))
      (libsource (lib "eagle-import") (part "CAP0402"))
    )
    (comp (ref "C505")
      (value "10n")
      (footprint "eagle-import:0402-CAP")
      (fields (field (name "PARTNO") "CC0402KRX7R7BB103"))
      (libsource (lib "eagle-import") (part "CAP0402"))
    )
    (comp (ref "C506")
      (value "10u/10V")
      (footprint "eagle-import:0805-CAP")
      (fields (field (name "PARTNO") "CC0805ZKY5V6BB106"))
      (libsource (lib "eagle-import") (part "CAP0805"))
    )
    (comp (ref "C507")
      (value "0u1")
      (footprint "eagle-import:0402-CAP")
      (fields (field (name "PARTNO") "CC0402ZRY5V7BB104"))
      (libsource (lib "eagle-import") (part "CAP0402"))
    )
    (comp (ref "C508")
      (value "0u1")
      (footprint "eagle-import:0402-CAP")
      (fields (field (name "PARTNO") "CC0402ZRY5V7BB104"))
      (libsource (lib "eagle-import") (part "CAP0402"))
    )
    (comp (ref "C509")
      (value "10u/10V")
      (footprint "eagle-import:0805-CAP")
      (fields (field (name "PARTNO") "CC0805ZKY5V6BB106"))
      (libsource (lib "eagle-import") (part "CAP0805"))
    )
    (comp (ref "C510")
      (value "0u47")
      (footprint "eagle-import:0402-CAP")
      (fields (field (name "PARTNO") "C1005X5R1C474K050BC"))
      (libsource (lib "eagle-import") (part "CAP0402"))
    )
    (comp (ref "C511")
      (value "10u/10V")
      (footprint "eagle-import:0805-CAP")
      (fields (field (name "PARTNO") "CC0805ZKY5V6BB106"))
      (libsource (lib "eagle-import") (part "CAP0805"))
    )
    (comp (ref "C512")
      (value "2u2")
      (footprint "eagle-import:0603-CAP")
      (fields (field (name "PARTNO") "C1608X6S1C225K080AC"))
      (libsource (lib "eagle-import") (part "CAP0603"))
    )
    (comp (ref "C513")
      (value "2u2")
      (footprint "eagle-import:0603-CAP")
      (fields (field (name "PARTNO") "C1608X6S1C225K080AC"))
      (libsource (lib "eagle-import") (part "CAP0603"))
    )
    (comp (ref "C514")
      (value "0u1")
      (footprint "eagle-import:0402-CAP")
      (fields (field (name "PARTNO") "CC0402ZRY5V7BB104"))
      (libsource (lib "eagle-import") (part "CAP0402"))
    )
    (comp (ref "C515")
      (value "0u01")
      (footprint "eagle-import:0603-CAP")
      (fields (field (name "PARTNO") "06033C103JAT2A"))
      (libsource (lib "eagle-import") (part "CAP0603"))
    )
    (comp (ref "U501")
      (value "L3GD20")
      (footprint "eagle-import:L3G4200DH-MAN")
      (libsource (lib "eagle-import") (part "L3G4200DH-LL"))
    )
    (comp (ref "U502")
      (value "L3GD20H")
      (footprint "eagle-import:LGA-16L")
      (libsource (lib "eagle-import") (part "L3GD20H"))
    )
    (comp (ref "U504")
      (value "LSM303D")
      (footprint "eagle-import:LGA-16L")
      (libsource (lib "eagle-import") (part "LSM303D"))
    )
    (comp (ref "U505")
      (value "MPU-6000")
      (footprint "eagle-import:QFN-24")
      (libsource (lib "eagle-import") (part "MPU-6000"))
    )
    (comp (ref "U506")
      (value "MS5611-01BA")
      (footprint "eagle-import:MS5611-01BA")
      (libsource (lib "eagle-import") (part "MS5611-01BA"))
    )
    (comp (ref "X503")
      (value "0512811094")
      (footprint "eagle-import:51281-1094")
      (fields (field (name "PARTNO") "0781191109") (field (name "BOM") "EXCLUDE"))
      (libsource (lib "eagle-import") (part "CONN_FPC_10RA"))
    )
  )
  (nets
    (net (code "1") (name "ACCEL_DRDY") (class "Default")
      (node (ref "U101") (pin "90") (pinfunction "PB4_90") (pintype "bidirectional"))
      (node (ref "U504") (pin "11") (pinfunction "INT1_11") (pintype "bidirectional"))
      (node (ref "X503") (pin "3") (pinfunction "S_3") (pintype "passive"))
    )
    (net (code "2") (name "ALARM") (class "Default")
      (node (ref "R701") (pin "P$2") (pinfunction "2_P$2") (pintype "passive"))
      (node (ref "U101") (pin "77") (pinfunction "PA15_77") (pintype "bidirectional"))
    )
    (net (code "3") (name "BATT_CURRENT_SENS") (class "Default")
      (node (ref "R1101") (pin "P$1") (pinfunction "1_P$1") (pintype "passive"))
      (node (ref "U101") (pin "26") (pinfunction "PA3_26") (pintype "bidirectional"))
    )
    (net (code "4") (name "BATT_VOLTAGE_SENS") (class "Default")
      (node (ref "R1102") (pin "P$1") (pinfunction "1_P$1") (pintype "passive"))
      (node (ref "U101") (pin "25") (pinfunction "PA2_25") (pintype "bidirectional"))
    )
    (net (code "5") (name "CAN1_RX") (class "Default")
      (node (ref "U101") (pin "81") (pinfunction "PD0_81") (pintype "bidirectional"))
      (node (ref "U401") (pin "4") (pinfunction "DOUT_4") (pintype "output"))
    )
    (net (code "6") (name "CAN1_TX") (class "Default")
      (node (ref "U101") (pin "82") (pinfunction "PD1_82") (pintype "bidirectional"))
      (node (ref "U401") (pin "1") (pinfunction "DIN_1") (pintype "input"))
    )
    (net (code "7") (name "CAN2_RX") (class "Default")
      (node (ref "R216") (pin "P$1") (pinfunction "1_P$1") (pintype "passive"))
      (node (ref "U101") (pin "51") (pinfunction "PB12_51") (pintype "bidirectional"))
    )
    (net (code "8") (name "CAN2_TX") (class "Default")
      (node (ref "R215") (pin "P$1") (pinfunction "1_P$1") (pintype "passive"))
      (node (ref "U101") (pin "92") (pinfunction "PB6_92") (pintype "bidirectional"))
    )
    (net (code "9") (name "CAN_H") (class "Default")
      (node (ref "CAN_H") (pin "P$1") (pinfunction "P$1_P$1") (pintype "passive"))
      (node (ref "J405") (pin "2") (pinfunction "2_2") (pintype "passive"))
      (node (ref "R409") (pin "P$1") (pinfunction "1_P$1") (pintype "passive"))
      (node (ref "U401") (pin "7") (pinfunction "CANH_7") (pintype "bidirectional"))
    )
    (net (code "10") (name "CAN_L") (class "Default")
      (node (ref "CAN_L") (pin "P$1") (pinfunction "P$1_P$1") (pintype "passive"))
      (node (ref "J405") (pin "3") (pinfunction "3_3") (pintype "passive"))
      (node (ref "R409") (pin "P$2") (pinfunction "2_P$2") (pintype "passive"))
      (node (ref "U401") (pin "6") (pinfunction "CANL_6") (pintype "bidirectional"))
    )
    (net (code "11") (name "FMU-BOOT0") (class "Default")
      (node (ref "FMU-BOOT1101") (pin "P$1") (pinfunction "P$1_P$1") (pintype "passive"))
      (node (ref "R611") (pin "P$2") (pinfunction "2_P$2") (pintype "passive"))
      (node (ref "U101") (pin "94") (pinfunction "BOOT0_94") (pintype "input"))
    )
    (net (code "12") (name "FMU-CH1") (class "Default")
      (node (ref "U101") (pin "45") (pinfunction "PE14_45") (pintype "bidirectional"))
      (node (ref "U901") (pin "7") (pinfunction "A6_7") (pintype "bidirectional"))
    )
    (net (code "13") (name "FMU-CH2") (class "Default")
      (node (ref "U101") (pin "44") (pinfunction "PE13_44") (pintype "bidirectional"))
      (node (ref "U901") (pin "6") (pinfunction "A5_6") (pintype "bidirectional"))
    )
    (net (code "14") (name "FMU-CH3") (class "Default")
      (node (ref "U101") (pin "42") (pinfunction "PE11_42") (pintype "bidirectional"))
      (node (ref "U901") (pin "5") (pinfunction "A4_5") (pintype "bidirectional"))
    )
    (net (code "15") (name "FMU-CH4") (class "Default")
      (node (ref "U101") (pin "40") (pinfunction "PE9_40") (pintype "bidirectional"))
      (node (ref "U901") (pin "4") (pinfunction "A3_4") (pintype "bidirectional"))
    )
    (net (code "16") (name "FMU-CH5") (class "Default")
      (node (ref "U101") (pin "60") (pinfunction "PD13_60") (pintype "bidirectional"))
      (node (ref "U901") (pin "3") (pinfunction "A2_3") (pintype "bidirectional"))
    )
    (net (code "17") (name "FMU-CH6") (class "Default")
      (node (ref "U101") (pin "61") (pinfunction "PD14_61") (pintype "bidirectional"))
      (node (ref "U901") (pin "1") (pinfunction "A1_1") (pintype "bidirectional"))
    )
    (net (code "18") (name "FMU-I2C1_SCL") (class "Default")
      (node (ref "R401") (pin "P$1") (pinfunction "1_P$1") (pintype "passive"))
      (node (ref "R404") (pin "P$1") (pinfunction "1_P$1") (pintype "passive"))
      (node (ref "U101") (pin "95") (pinfunction "PB8_95") (pintype "bidirectional"))
    )
    (net (code "19") (name "FMU-I2C1_SDA") (class "Default")
      (node (ref "R402") (pin "P$1") (pinfunction "1_P$1") (pintype "passive"))
      (node (ref "R405") (pin "P$1") (pinfunction "1_P$1") (pintype "passive"))
      (node (ref "U101") (pin "96") (pinfunction "PB9_96") (pintype "bidirectional"))
    )
    (net (code "20") (name "FMU-I2C2_SCL") (class "Default")
      (node (ref "R306") (pin "P$1") (pinfunction "1_P$1") (pintype "passive"))
      (node (ref "U101") (pin "47") (pinfunction "PB10_47") (pintype "bidirectional"))
      (node (ref "U701") (pin "3") (pinfunction "SCL_3") (pintype "bidirectional"))
    )
    (net (code "21") (name "FMU-I2C2_SDA") (class "Default")
      (node (ref "R307") (pin "P$1") (pinfunction "1_P$1") (pintype "passive"))
      (node (ref "U101") (pin "48") (pinfunction "PB11_48") (pintype "bidirectional"))
      (node (ref "U701") (pin "2") (pinfunction "SDA_2") (pintype "bidirectional"))
    )
    (net (code "22") (name "FMU-SWCLK") (class "Default")
      (node (ref "JX301") (pin "4") (pinfunction "S_4") (pintype "passive"))
      (node (ref "U101") (pin "76") (pinfunction "PA14_76") (pintype "bidirectional"))
    )
    (net (code "23") (name "FMU-SWDIO") (class "Default")
      (node (ref "JX301") (pin "2") (pinfunction "S_2") (pintype "passive"))
      (node (ref "U101") (pin "72") (pinfunction "PA13_72") (pintype "bidirectional"))
    )
    (net (code "24") (name "FMU-SWO") (class "Default")
      (node (ref "JX301") (pin "6") (pinfunction "S_6") (pintype "passive"))
      (node (ref "U101") (pin "89") (pinfunction "PB3_89") (pintype "bidirectional"))
    )
    (net (code "25") (name "FMU-UART4_RX") (class "Default")
      (node (ref "U101") (pin "24") (pinfunction "PA1_24") (pintype "bidirectional"))
      (node (ref "U202") (pin "8") (pinfunction "A7_8") (pintype "bidirectional"))
    )
    (net (code "26") (name "FMU-UART4_TX") (class "Default")
      (node (ref "U101") (pin "23") (pinfunction "PA0_23") (pintype "bidirectional"))
      (node (ref "U202") (pin "9") (pinfunction "A8_9") (pintype "bidirectional"))
    )
    (net (code "27") (name "FMU-UART7_RX") (class "Default")
      (node (ref "U101") (pin "38") (pinfunction "PE7_38") (pintype "bidirectional"))
      (node (ref "U202") (pin "4") (pinfunction "A3_4") (pintype "bidirectional"))
    )
    (net (code "28") (name "FMU-UART7_TX") (class "Default")
      (node (ref "U101") (pin "39") (pinfunction "PE8_39") (pintype "bidirectional"))
      (node (ref "U202") (pin "5") (pinfunction "A4_5") (pintype "bidirectional"))
    )
    (net (code "29") (name "FMU-UART8_RX") (class "Default")
      (node (ref "U101") (pin "97") (pinfunction "PE0_97") (pintype "bidirectional"))
      (node (ref "U202") (pin "6") (pinfunction "A5_6") (pintype "bidirectional"))
    )
    (net (code "30") (name "FMU-UART8_TX") (class "Default")
      (node (ref "U101") (pin "98") (pinfunction "PE1_98") (pintype "bidirectional"))
      (node (ref "U202") (pin "7") (pinfunction "A6_7") (pintype "bidirectional"))
    )
    (net (code "31") (name "FMU-USART2_CTS") (class "Default")
      (node (ref "U101") (pin "84") (pinfunction "PD3_84") (pintype "bidirectional"))
      (node (ref "U201") (pin "9") (pinfunction "A8_9") (pintype "bidirectional"))
    )
    (net (code "32") (name "FMU-USART2_RTS") (class "Default")
      (node (ref "U101") (pin "85") (pinfunction "PD4_85") (pintype "bidirectional"))
      (node (ref "U201") (pin "8") (pinfunction "A7_8") (pintype "bidirectional"))
    )
    (net (code "33") (name "FMU-USART2_RX") (class "Default")
      (node (ref "U101") (pin "87") (pinfunction "PD6_87") (pintype "bidirectional"))
      (node (ref "U201") (pin "6") (pinfunction "A5_6") (pintype "bidirectional"))
    )
    (net (code "34") (name "FMU-USART2_TX") (class "Default")
      (node (ref "U101") (pin "86") (pinfunction "PD5_86") (pintype "bidirectional"))
      (node (ref "U201") (pin "7") (pinfunction "A6_7") (pintype "bidirectional"))
    )
    (net (code "35") (name "FMU-USART3_CTS") (class "Default")
      (node (ref "U101") (pin "58") (pinfunction "PD11_58") (pintype "bidirectional"))
      (node (ref "U201") (pin "3") (pinfunction "A2_3") (pintype "bidirectional"))
    )
    (net (code "36") (name "FMU-USART3_RTS") (class "Default")
      (node (ref "U101") (pin "59") (pinfunction "PD12_59") (pintype "bidirectional"))
      (node (ref "U201") (pin "1") (pinfunction "A1_1") (pintype "bidirectional"))
    )
    (net (code "37") (name "FMU-USART3_RX") (class "Default")
      (node (ref "U101") (pin "56") (pinfunction "PD9_56") (pintype "bidirectional"))
      (node (ref "U201") (pin "4") (pinfunction "A3_4") (pintype "bidirectional"))
    )
    (net (code "38") (name "FMU-USART3_TX") (class "Default")
      (node (ref "U101") (pin "55") (pinfunction "PD8_55") (pintype "bidirectional"))
      (node (ref "U201") (pin "5") (pinfunction "A4_5") (pintype "bidirectional"))
    )
    (net (code "39") (name "FMU-VDD_3V3") (class "Default")
      (node (ref "C101") (pin "P$1") (pinfunction "1_P$1") (pintype "passive"))
      (node (ref "C201") (pin "P$1") (pinfunction "1_P$1") (pintype "passive"))
      (node (ref "C202") (pin "P$1") (pinfunction "1_P$1") (pintype "passive"))
      (node (ref "C402") (pin "P$1") (pinfunction "1_P$1") (pintype "passive"))
      (node (ref "C603") (pin "P$1") (pinfunction "1_P$1") (pintype "passive"))
      (node (ref "C604") (pin "P$1") (pinfunction "1_P$1") (pintype "passive"))
      (node (ref "C606") (pin "P$1") (pinfunction "1_P$1") (pintype "passive"))
      (node (ref "C607") (pin "P$1") (pinfunction "1_P$1") (pintype "passive"))
      (node (ref "C608") (pin "P$1") (pinfunction "1_P$1") (pintype "passive"))
      (node (ref "C610") (pin "P$1") (pinfunction "1_P$1") (pintype "passive"))
      (node (ref "C612") (pin "P$1") (pinfunction "1_P$1") (pintype "passive"))
      (node (ref "C616") (pin "P$1") (pinfunction "1_P$1") (pintype "passive"))
      (node (ref "C701") (pin "P$1") (pinfunction "1_P$1") (pintype "passive"))
      (node (ref "C902") (pin "P$1") (pinfunction "1_P$1") (pintype "passive"))
      (node (ref "D602") (pin "A") (pinfunction "A_A") (pintype "passive"))
      (node (ref "JX301") (pin "1") (pinfunction "S_1") (pintype "passive"))
      (node (ref "R301") (pin "P$2") (pinfunction "2_P$2") (pintype "passive"))
      (node (ref "R302") (pin "P$2") (pinfunction "2_P$2") (pintype "passive"))
      (node (ref "R303") (pin "P$2") (pinfunction "2_P$2") (pintype "passive"))
      (node (ref "R304") (pin "P$2") (pinfunction "2_P$2") (pintype "passive"))
      (node (ref "R305") (pin "P$2") (pinfunction "2_P$2") (pintype "passive"))
      (node (ref "R306") (pin "P$2") (pinfunction "2_P$2") (pintype "passive"))
      (node (ref "R307") (pin "P$2") (pinfunction "2_P$2") (pintype "passive"))
      (node (ref "R401") (pin "P$2") (pinfunction "2_P$2") (pintype "passive"))
      (node (ref "R402") (pin "P$2") (pinfunction "2_P$2") (pintype "passive"))
      (node (ref "R602") (pin "P$2") (pinfunction "2_P$2") (pintype "passive"))
      (node (ref "R604") (pin "P$2") (pinfunction "2_P$2") (pintype "passive"))
      (node (ref "U101") (pin "100") (pinfunction "VDD_100") (pintype "power_in"))
      (node (ref "U101") (pin "11") (pinfunction "VDD_11") (pintype "power_in"))
      (node (ref "U101") (pin "19") (pinfunction "VDD_19") (pintype "power_in"))
      (node (ref "U101") (pin "21") (pinfunction "VREF+_21") (pintype "input"))
      (node (ref "U101") (pin "22") (pinfunction "VDDA_22") (pintype "power_in"))
      (node (ref "U101") (pin "28") (pinfunction "VDD_28") (pintype "power_in"))
      (node (ref "U101") (pin "50") (pinfunction "VDD_50") (pintype "power_in"))
      (node (ref "U101") (pin "75") (pinfunction "VDD_75") (pintype "power_in"))
      (node (ref "U102") (pin "3") (pinfunction "~{W}_3") (pintype "bidirectional"))
      (node (ref "U102") (pin "7") (pinfunction "~{HOLD}_7") (pintype "bidirectional"))
      (node (ref "U102") (pin "8") (pinfunction "VDD_8") (pintype "bidirectional"))
      (node (ref "U201") (pin "10") (pinfunction "OE_10") (pintype "input"))
      (node (ref "U201") (pin "19") (pinfunction "VCCB_19") (pintype "input"))
      (node (ref "U201") (pin "2") (pinfunction "VCCA_2") (pintype "input"))
      (node (ref "U202") (pin "10") (pinfunction "OE_10") (pintype "input"))
      (node (ref "U202") (pin "19") (pinfunction "VCCB_19") (pintype "input"))
      (node (ref "U202") (pin "2") (pinfunction "VCCA_2") (pintype "input"))
      (node (ref "U301") (pin "4") (pinfunction "VCC_4") (pintype "passive"))
      (node (ref "U401") (pin "3") (pinfunction "VCC_3") (pintype "input"))
      (node (ref "U603") (pin "7") (pinfunction "VOUT2_7") (pintype "bidirectional"))
      (node (ref "U701") (pin "1") (pinfunction "~{SHDN}_1") (pintype "input"))
      (node (ref "U701") (pin "10") (pinfunction "VIN_10") (pintype "power_in"))
      (node (ref "U901") (pin "10") (pinfunction "OE_10") (pintype "input"))
      (node (ref "U901") (pin "19") (pinfunction "VCCB_19") (pintype "input"))
      (node (ref "U901") (pin "2") (pinfunction "VCCA_2") (pintype "input"))
      (node (ref "VDD_3V1101") (pin "P$1") (pinfunction "P$1_P$1") (pintype "passive"))
    )
    (net (code "40") (name "FMU-~{RESET}") (class "Default")
      (node (ref "C609") (pin "P$2") (pinfunction "2_P$2") (pintype "passive"))
      (node (ref "R635") (pin "P$1") (pinfunction "1_P$1") (pintype "passive"))
      (node (ref "S601") (pin "A1") (pinfunction "1_A1") (pintype "passive"))
      (node (ref "U101") (pin "14") (pinfunction "NRST_14") (pintype "input"))
      (node (ref "U603") (pin "3") (pinfunction "POR2_3") (pintype "bidirectional"))
      (node (ref "U701") (pin "4") (pinfunction "~{RESET}_4") (pintype "input"))
    )
    (net (code "41") (name "FMU_AUX_ADC1") (class "Default")
      (node (ref "R408") (pin "P$1") (pinfunction "1_P$1") (pintype "passive"))
      (node (ref "U101") (pin "18") (pinfunction "PC3_18") (pintype "bidirectional"))
    )
    (net (code "42") (name "FMU_AUX_ADC2") (class "Default")
      (node (ref "R407") (pin "P$1") (pinfunction "1_P$1") (pintype "passive"))
      (node (ref "U101") (pin "33") (pinfunction "PC4_33") (pintype "bidirectional"))
    )
    (net (code "43") (name "FRAM_MISO") (class "Default")
      (node (ref "U101") (pin "53") (pinfunction "PB14_53") (pintype "bidirectional"))
      (node (ref "U102") (pin "2") (pinfunction "Q_2") (pintype "bidirectional"))
    )
    (net (code "44") (name "FRAM_MOSI") (class "Default")
      (node (ref "U101") (pin "54") (pinfunction "PB15_54") (pintype "bidirectional"))
      (node (ref "U102") (pin "5") (pinfunction "D_5") (pintype "bidirectional"))
    )
    (net (code "45") (name "FRAM_SCK") (class "Default")
      (node (ref "U101") (pin "52") (pinfunction "PB13_52") (pintype "bidirectional"))
      (node (ref "U102") (pin "6") (pinfunction "C_6") (pintype "bidirectional"))
    )
    (net (code "46") (name "GND") (class "Default")
      (node (ref "B601") (pin "2") (pinfunction "NEG_2") (pintype "bidirectional"))
      (node (ref "C1001") (pin "P$2") (pinfunction "2_P$2") (pintype "passive"))
      (node (ref "C1002") (pin "P$2") (pinfunction "2_P$2") (pintype "passive"))
      (node (ref "C1003") (pin "P$2") (pinfunction "2_P$2") (pintype "passive"))
      (node (ref "C1004") (pin "P$2") (pinfunction "2_P$2") (pintype "passive"))
      (node (ref "C1005") (pin "P$2") (pinfunction "2_P$2") (pintype "passive"))
      (node (ref "C1008") (pin "P$2") (pinfunction "2_P$2") (pintype "passive"))
      (node (ref "C101") (pin "P$2") (pinfunction "2_P$2") (pintype "passive"))
      (node (ref "C102") (pin "P$2") (pinfunction "2_P$2") (pintype "passive"))
      (node (ref "C103") (pin "P$1") (pinfunction "1_P$1") (pintype "passive"))
      (node (ref "C1101") (pin "P$2") (pinfunction "2_P$2") (pintype "passive"))
      (node (ref "C1102") (pin "P$2") (pinfunction "2_P$2") (pintype "passive"))
      (node (ref "C1103") (pin "P$2") (pinfunction "2_P$2") (pintype "passive"))
      (node (ref "C1104") (pin "P$2") (pinfunction "2_P$2") (pintype "passive"))
      (node (ref "C1105") (pin "P$2") (pinfunction "2_P$2") (pintype "passive"))
      (node (ref "C1106") (pin "P$2") (pinfunction "2_P$2") (pintype "passive"))
      (node (ref "C1107") (pin "P$2") (pinfunction "2_P$2") (pintype "passive"))
      (node (ref "C1108") (pin "P$2") (pinfunction "2_P$2") (pintype "passive"))
      (node (ref "C1109") (pin "P$2") (pinfunction "2_P$2") (pintype "passive"))
      (node (ref "C1110") (pin "P$2") (pinfunction "2_P$2") (pintype "passive"))
      (node (ref "C201") (pin "P$2") (pinfunction "2_P$2") (pintype "passive"))
      (node (ref "C202") (pin "P$2") (pinfunction "2_P$2") (pintype "passive"))
      (node (ref "C401") (pin "P$2") (pinfunction "2_P$2") (pintype "passive"))
      (node (ref "C402") (pin "P$2") (pinfunction "2_P$2") (pintype "passive"))
      (node (ref "C501") (pin "P$2") (pinfunction "2_P$2") (pintype "passive"))
      (node (ref "C502") (pin "P$2") (pinfunction "2_P$2") (pintype "passive"))
      (node (ref "C503") (pin "P$2") (pinfunction "2_P$2") (pintype "passive"))
      (node (ref "C504") (pin "P$2") (pinfunction "2_P$2") (pintype "passive"))
      (node (ref "C505") (pin "P$2") (pinfunction "2_P$2") (pintype "passive"))
      (node (ref "C506") (pin "P$2") (pinfunction "2_P$2") (pintype "passive"))
      (node (ref "C507") (pin "P$2") (pinfunction "2_P$2") (pintype "passive"))
      (node (ref "C508") (pin "P$2") (pinfunction "2_P$2") (pintype "passive"))
      (node (ref "C509") (pin "P$2") (pinfunction "2_P$2") (pintype "passive"))
      (node (ref "C511") (pin "P$2") (pinfunction "2_P$2") (pintype "passive"))
      (node (ref "C512") (pin "P$2") (pinfunction "2_P$2") (pintype "passive"))
      (node (ref "C513") (pin "P$2") (pinfunction "2_P$2") (pintype "passive"))
      (node (ref "C514") (pin "P$2") (pinfunction "2_P$2") (pintype "passive"))
      (node (ref "C515") (pin "P$2") (pinfunction "2_P$2") (pintype "passive"))
      (node (ref "C601") (pin "P$2") (pinfunction "2_P$2") (pintype "passive"))
      (node (ref "C602") (pin "P$1") (pinfunction "1_P$1") (pintype "passive"))
      (node (ref "C603") (pin "P$2") (pinfunction "2_P$2") (pintype "passive"))
      (node (ref "C604") (pin "P$2") (pinfunction "2_P$2") (pintype "passive"))
      (node (ref "C605") (pin "P$2") (pinfunction "2_P$2") (pintype "passive"))
      (node (ref "C606") (pin "P$2") (pinfunction "2_P$2") (pintype "passive"))
      (node (ref "C607") (pin "P$2") (pinfunction "2_P$2") (pintype "passive"))
      (node (ref "C608") (pin "P$2") (pinfunction "2_P$2") (pintype "passive"))
      (node (ref "C609") (pin "P$1") (pinfunction "1_P$1") (pintype "passive"))
      (node (ref "C610") (pin "P$2") (pinfunction "2_P$2") (pintype "passive"))
      (node (ref "C611") (pin "P$2") (pinfunction "2_P$2") (pintype "passive"))
      (node (ref "C612") (pin "P$2") (pinfunction "2_P$2") (pintype "passive"))
      (node (ref "C613") (pin "P$2") (pinfunction "2_P$2") (pintype "passive"))
      (node (ref "C614") (pin "P$2") (pinfunction "2_P$2") (pintype "passive"))
      (node (ref "C615") (pin "P$2") (pinfunction "2_P$2") (pintype "passive"))
      (node (ref "C616") (pin "P$2") (pinfunction "2_P$2") (pintype "passive"))
      (node (ref "C617") (pin "P$2") (pinfunction "2_P$2") (pintype "passive"))
      (node (ref "C618") (pin "P$2") (pinfunction "2_P$2") (pintype "passive"))
      (node (ref "C701") (pin "P$2") (pinfunction "2_P$2") (pintype "passive"))
      (node (ref "C702") (pin "P$2") (pinfunction "2_P$2") (pintype "passive"))
      (node (ref "C703") (pin "P$2") (pinfunction "2_P$2") (pintype "passive"))
      (node (ref "C704") (pin "P$2") (pinfunction "2_P$2") (pintype "passive"))
      (node (ref "C801") (pin "P$1") (pinfunction "1_P$1") (pintype "passive"))
      (node (ref "C802") (pin "P$2") (pinfunction "2_P$2") (pintype "passive"))
      (node (ref "C803") (pin "P$2") (pinfunction "2_P$2") (pintype "passive"))
      (node (ref "C804") (pin "P$2") (pinfunction "2_P$2") (pintype "passive"))
      (node (ref "C805") (pin "P$2") (pinfunction "2_P$2") (pintype "passive"))
      (node (ref "C806") (pin "P$1") (pinfunction "1_P$1") (pintype "passive"))
      (node (ref "C901") (pin "P$2") (pinfunction "2_P$2") (pintype "passive"))
      (node (ref "C902") (pin "P$2") (pinfunction "2_P$2") (pintype "passive"))
      (node (ref "C903") (pin "P$2") (pinfunction "2_P$2") (pintype "passive"))
      (node (ref "D201") (pin "A") (pinfunction "A_A") (pintype "passive"))
      (node (ref "D202") (pin "A") (pinfunction "A_A") (pintype "passive"))
      (node (ref "D203") (pin "A") (pinfunction "A_A") (pintype "passive"))
      (node (ref "D401") (pin "A") (pinfunction "A_A") (pintype "passive"))
      (node (ref "D402") (pin "A") (pinfunction "A_A") (pintype "passive"))
      (node (ref "D403") (pin "A") (pinfunction "A_A") (pintype "passive"))
      (node (ref "D404") (pin "A") (pinfunction "A_A") (pintype "passive"))
      (node (ref "D701") (pin "A") (pinfunction "A_A") (pintype "passive"))
      (node (ref "D801") (pin "A") (pinfunction "A_A") (pintype "passive"))
      (node (ref "D901") (pin "A") (pinfunction "A_A") (pintype "passive"))
      (node (ref "D902") (pin "A") (pinfunction "A_A") (pintype "passive"))
      (node (ref "D903") (pin "A") (pinfunction "A_A") (pintype "passive"))
      (node (ref "GND") (pin "P$1") (pinfunction "P$1_P$1") (pintype "passive"))
      (node (ref "GND.") (pin "P$1") (pinfunction "P$1_P$1") (pintype "passive"))
      (node (ref "J201") (pin "6") (pinfunction "6_6") (pintype "passive"))
      (node (ref "J202") (pin "6") (pinfunction "6_6") (pintype "passive"))
      (node (ref "J203") (pin "6") (pinfunction "6_6") (pintype "passive"))
      (node (ref "J204") (pin "6") (pinfunction "6_6") (pintype "passive"))
      (node (ref "J301") (pin "GND") (pinfunction "5_GND") (pintype "power_in"))
      (node (ref "J301") (pin "GND1") (pinfunction "GND1_GND1") (pintype "bidirectional"))
      (node (ref "J301") (pin "GND2") (pinfunction "GND2_GND2") (pintype "bidirectional"))
      (node (ref "J301") (pin "GND3") (pinfunction "GND3_GND3") (pintype "bidirectional"))
      (node (ref "J301") (pin "GND4") (pinfunction "GND4_GND4") (pintype "bidirectional"))
      (node (ref "J302") (pin "4") (pinfunction "4_4") (pintype "passive"))
      (node (ref "J401") (pin "4") (pinfunction "4_4") (pintype "passive"))
      (node (ref "J402") (pin "3") (pinfunction "3_3") (pintype "passive"))
      (node (ref "J403") (pin "7") (pinfunction "7_7") (pintype "passive"))
      (node (ref "J404") (pin "3") (pinfunction "3_3") (pintype "passive"))
      (node (ref "J404") (pin "5") (pinfunction "5_5") (pintype "passive"))
      (node (ref "J405") (pin "4") (pinfunction "4_4") (pintype "passive"))
      (node (ref "J601") (pin "5") (pinfunction "5_5") (pintype "passive"))
      (node (ref "J601") (pin "6") (pinfunction "6_6") (pintype "passive"))
      (node (ref "J701") (pin "2") (pinfunction "2_2") (pintype "passive"))
      (node (ref "J801") (pin "P$2") (pinfunction "P$2_P$2") (pintype "bidirectional"))
      (node (ref "J901") (pin "12") (pinfunction "S_12") (pintype "passive"))
      (node (ref "J901") (pin "15") (pinfunction "S_15") (pintype "passive"))
      (node (ref "J901") (pin "18") (pinfunction "S_18") (pintype "passive"))
      (node (ref "J901") (pin "21") (pinfunction "S_21") (pintype "passive"))
      (node (ref "J901") (pin "24") (pinfunction "S_24") (pintype "passive"))
      (node (ref "J901") (pin "27") (pinfunction "S_27") (pintype "passive"))
      (node (ref "J901") (pin "3") (pinfunction "S_3") (pintype "passive"))
      (node (ref "J901") (pin "30") (pinfunction "S_30") (pintype "passive"))
      (node (ref "J901") (pin "33") (pinfunction "S_33") (pintype "passive"))
      (node (ref "J901") (pin "36") (pinfunction "S_36") (pintype "passive"))
      (node (ref "J901") (pin "39") (pinfunction "S_39") (pintype "passive"))
      (node (ref "J901") (pin "42") (pinfunction "S_42") (pintype "passive"))
      (node (ref "J901") (pin "45") (pinfunction "S_45") (pintype "passive"))
      (node (ref "J901") (pin "48") (pinfunction "S_48") (pintype "passive"))
      (node (ref "J901") (pin "6") (pinfunction "S_6") (pintype "passive"))
      (node (ref "J901") (pin "9") (pinfunction "S_9") (pintype "passive"))
      (node (ref "JX301") (pin "3") (pinfunction "S_3") (pintype "passive"))
      (node (ref "JX301") (pin "5") (pinfunction "S_5") (pintype "passive"))
      (node (ref "JX301") (pin "9") (pinfunction "S_9") (pintype "passive"))
      (node (ref "JX801") (pin "3") (pinfunction "GND_3") (pintype "bidirectional"))
      (node (ref "JX802") (pin "3") (pinfunction "S_3") (pintype "passive"))
      (node (ref "JX802") (pin "5") (pinfunction "S_5") (pintype "passive"))
      (node (ref "JX802") (pin "9") (pinfunction "S_9") (pintype "passive"))
      (node (ref "L1101") (pin "P$3") (pinfunction "P$3_P$3") (pintype "bidirectional"))
      (node (ref "L1101") (pin "P$4") (pinfunction "P$3_P$4") (pintype "bidirectional"))
      (node (ref "L1101") (pin "P$5") (pinfunction "P$3_P$5") (pintype "bidirectional"))
      (node (ref "L1102") (pin "P$3") (pinfunction "P$3_P$3") (pintype "bidirectional"))
      (node (ref "L1102") (pin "P$4") (pinfunction "P$3_P$4") (pintype "bidirectional"))
      (node (ref "L1102") (pin "P$5") (pinfunction "P$3_P$5") (pintype "bidirectional"))
      (node (ref "L201") (pin "P$3") (pinfunction "P$3_P$3") (pintype "bidirectional"))
      (node (ref "L201") (pin "P$4") (pinfunction "P$3_P$4") (pintype "bidirectional"))
      (node (ref "L201") (pin "P$5") (pinfunction "P$3_P$5") (pintype "bidirectional"))
      (node (ref "L202") (pin "P$3") (pinfunction "P$3_P$3") (pintype "bidirectional"))
      (node (ref "L202") (pin "P$4") (pinfunction "P$3_P$4") (pintype "bidirectional"))
      (node (ref "L202") (pin "P$5") (pinfunction "P$3_P$5") (pintype "bidirectional"))
      (node (ref "L203") (pin "P$3") (pinfunction "P$3_P$3") (pintype "bidirectional"))
      (node (ref "L203") (pin "P$4") (pinfunction "P$3_P$4") (pintype "bidirectional"))
      (node (ref "L203") (pin "P$5") (pinfunction "P$3_P$5") (pintype "bidirectional"))
      (node (ref "L401") (pin "P$3") (pinfunction "P$3_P$3") (pintype "bidirectional"))
      (node (ref "L401") (pin "P$4") (pinfunction "P$3_P$4") (pintype "bidirectional"))
      (node (ref "L401") (pin "P$5") (pinfunction "P$3_P$5") (pintype "bidirectional"))
      (node (ref "L402") (pin "P$3") (pinfunction "P$3_P$3") (pintype "bidirectional"))
      (node (ref "L402") (pin "P$4") (pinfunction "P$3_P$4") (pintype "bidirectional"))
      (node (ref "L402") (pin "P$5") (pinfunction "P$3_P$5") (pintype "bidirectional"))
      (node (ref "L403") (pin "P$3") (pinfunction "P$3_P$3") (pintype "bidirectional"))
      (node (ref "L403") (pin "P$4") (pinfunction "P$3_P$4") (pintype "bidirectional"))
      (node (ref "L403") (pin "P$5") (pinfunction "P$3_P$5") (pintype "bidirectional"))
      (node (ref "L404") (pin "P$3") (pinfunction "P$3_P$3") (pintype "bidirectional"))
      (node (ref "L404") (pin "P$4") (pinfunction "P$3_P$4") (pintype "bidirectional"))
      (node (ref "L404") (pin "P$5") (pinfunction "P$3_P$5") (pintype "bidirectional"))
      (node (ref "L603") (pin "P$3") (pinfunction "P$3_P$3") (pintype "bidirectional"))
      (node (ref "L603") (pin "P$4") (pinfunction "P$3_P$4") (pintype "bidirectional"))
      (node (ref "L603") (pin "P$5") (pinfunction "P$3_P$5") (pintype "bidirectional"))
      (node (ref "L901") (pin "P$3") (pinfunction "P$3_P$3") (pintype "bidirectional"))
      (node (ref "L901") (pin "P$4") (pinfunction "P$3_P$4") (pintype "bidirectional"))
      (node (ref "L901") (pin "P$5") (pinfunction "P$3_P$5") (pintype "bidirectional"))
      (node (ref "R1001") (pin "P$1") (pinfunction "1_P$1") (pintype "passive"))
      (node (ref "R1002") (pin "P$1") (pinfunction "1_P$1") (pintype "passive"))
      (node (ref "R102") (pin "P$2") (pinfunction "2_P$2") (pintype "passive"))
      (node (ref "R1103") (pin "P$2") (pinfunction "2_P$2") (pintype "passive"))
      (node (ref "R1104") (pin "P$2") (pinfunction "2_P$2") (pintype "passive"))
      (node (ref "R1107") (pin "P$2") (pinfunction "2_P$2") (pintype "passive"))
      (node (ref "R1111") (pin "P$2") (pinfunction "2_P$2") (pintype "passive"))
      (node (ref "R1114") (pin "P$2") (pinfunction "2_P$2") (pintype "passive"))
      (node (ref "R1115") (pin "P$1") (pinfunction "1_P$1") (pintype "passive"))
      (node (ref "R403") (pin "P$1") (pinfunction "1_P$1") (pintype "passive"))
      (node (ref "R610") (pin "P$2") (pinfunction "2_P$2") (pintype "passive"))
      (node (ref "R611") (pin "P$1") (pinfunction "1_P$1") (pintype "passive"))
      (node (ref "R615") (pin "P$2") (pinfunction "2_P$2") (pintype "passive"))
      (node (ref "R616") (pin "P$2") (pinfunction "2_P$2") (pintype "passive"))
      (node (ref "R617") (pin "P$2") (pinfunction "2_P$2") (pintype "passive"))
      (node (ref "R621") (pin "1") (pinfunction "1_1") (pintype "passive"))
      (node (ref "R702") (pin "P$2") (pinfunction "2_P$2") (pintype "passive"))
      (node (ref "R704") (pin "P$1") (pinfunction "1_P$1") (pintype "passive"))
      (node (ref "R706") (pin "P$2") (pinfunction "2_P$2") (pintype "passive"))
      (node (ref "R708") (pin "P$1") (pinfunction "1_P$1") (pintype "passive"))
      (node (ref "R711") (pin "P$1") (pinfunction "1_P$1") (pintype "passive"))
      (node (ref "R713") (pin "P$2") (pinfunction "2_P$2") (pintype "passive"))
      (node (ref "R801") (pin "P$2") (pinfunction "2_P$2") (pintype "passive"))
      (node (ref "R802") (pin "P$2") (pinfunction "2_P$2") (pintype "passive"))
      (node (ref "R919") (pin "P$1") (pinfunction "1_P$1") (pintype "passive"))
      (node (ref "S601") (pin "B3") (pinfunction "2_B3") (pintype "passive"))
      (node (ref "S801") (pin "B3") (pinfunction "2_B3") (pintype "passive"))
      (node (ref "U1001") (pin "2") (pinfunction "VSS_2") (pintype "bidirectional"))
      (node (ref "U1001") (pin "5") (pinfunction "~{CE}_5") (pintype "bidirectional"))
      (node (ref "U1001") (pin "6") (pinfunction "VBAT_6") (pintype "bidirectional"))
      (node (ref "U1001") (pin "GND") (pinfunction "VSS_GND") (pintype "bidirectional"))
      (node (ref "U1001") (pin "P$2") (pinfunction "VSS_P$2") (pintype "bidirectional"))
      (node (ref "U1001") (pin "P$3") (pinfunction "VSS_P$3") (pintype "bidirectional"))
      (node (ref "U1002") (pin "2") (pinfunction "GND_2") (pintype "bidirectional"))
      (node (ref "U1002") (pin "GND") (pinfunction "GND_GND") (pintype "bidirectional"))
      (node (ref "U101") (pin "10") (pinfunction "VSS_10") (pintype "power_in"))
      (node (ref "U101") (pin "20") (pinfunction "VSSA_20") (pintype "power_in"))
      (node (ref "U101") (pin "27") (pinfunction "VSS_27") (pintype "power_in"))
      (node (ref "U101") (pin "74") (pinfunction "VSS_74") (pintype "power_in"))
      (node (ref "U101") (pin "99") (pinfunction "VSS_99") (pintype "power_in"))
      (node (ref "U102") (pin "4") (pinfunction "VSS_4") (pintype "bidirectional"))
      (node (ref "U1101") (pin "P$10") (pinfunction "GND_P$10") (pintype "bidirectional"))
      (node (ref "U1101") (pin "P$25") (pinfunction "GND_P$25") (pintype "bidirectional"))
      (node (ref "U201") (pin "11") (pinfunction "GND_11") (pintype "power_in"))
      (node (ref "U202") (pin "11") (pinfunction "GND_11") (pintype "power_in"))
      (node (ref "U301") (pin "6") (pinfunction "GND_6") (pintype "power_in"))
      (node (ref "U302") (pin "2") (pinfunction "GND_2") (pintype "bidirectional"))
      (node (ref "U401") (pin "2") (pinfunction "GND_2") (pintype "power_in"))
      (node (ref "U401") (pin "5") (pinfunction "SHDN_5") (pintype "input"))
      (node (ref "U401") (pin "8") (pinfunction "RS_8") (pintype "input"))
      (node (ref "U501") (pin "10") (pinfunction "RES_P10_GND_10") (pintype "bidirectional"))
      (node (ref "U501") (pin "11") (pinfunction "RES_P11_GND_11") (pintype "bidirectional"))
      (node (ref "U501") (pin "12") (pinfunction "RES_P12_GND_12") (pintype "bidirectional"))
      (node (ref "U501") (pin "13") (pinfunction "GND_13") (pintype "bidirectional"))
      (node (ref "U501") (pin "8") (pinfunction "RES_P8_GND_8") (pintype "bidirectional"))
      (node (ref "U501") (pin "9") (pinfunction "RES_P9_GND_9") (pintype "bidirectional"))
      (node (ref "U502") (pin "10") (pinfunction "GND_10") (pintype "bidirectional"))
      (node (ref "U502") (pin "11") (pinfunction "GND_11") (pintype "bidirectional"))
      (node (ref "U502") (pin "12") (pinfunction "GND_12") (pintype "bidirectional"))
      (node (ref "U502") (pin "13") (pinfunction "GND_13") (pintype "bidirectional"))
      (node (ref "U502") (pin "9") (pinfunction "GND_9") (pintype "bidirectional"))
      (node (ref "U504") (pin "10") (pinfunction "RSRV_10") (pintype "bidirectional"))
      (node (ref "U504") (pin "12") (pinfunction "GND_12") (pintype "bidirectional"))
      (node (ref "U504") (pin "13") (pinfunction "GND_13") (pintype "bidirectional"))
      (node (ref "U504") (pin "16") (pinfunction "GND_16") (pintype "bidirectional"))
      (node (ref "U504") (pin "5") (pinfunction "GND_5") (pintype "bidirectional"))
      (node (ref "U505") (pin "1") (pinfunction "CLKIN_1") (pintype "bidirectional"))
      (node (ref "U505") (pin "18") (pinfunction "GND_18") (pintype "bidirectional"))
      (node (ref "U506") (pin "2") (pinfunction "PS_2") (pintype "bidirectional"))
      (node (ref "U506") (pin "3") (pinfunction "GND_3") (pintype "bidirectional"))
      (node (ref "U601") (pin "2") (pinfunction "VSS_2") (pintype "bidirectional"))
      (node (ref "U601") (pin "6") (pinfunction "VBAT_6") (pintype "bidirectional"))
      (node (ref "U601") (pin "GND") (pinfunction "VSS_GND") (pintype "bidirectional"))
      (node (ref "U601") (pin "P$2") (pinfunction "VSS_P$2") (pintype "bidirectional"))
      (node (ref "U601") (pin "P$3") (pinfunction "VSS_P$3") (pintype "bidirectional"))
      (node (ref "U602") (pin "2") (pinfunction "VSS_2") (pintype "bidirectional"))
      (node (ref "U602") (pin "6") (pinfunction "VBAT_6") (pintype "bidirectional"))
      (node (ref "U602") (pin "GND") (pinfunction "VSS_GND") (pintype "bidirectional"))
      (node (ref "U602") (pin "P$2") (pinfunction "VSS_P$2") (pintype "bidirectional"))
      (node (ref "U602") (pin "P$3") (pinfunction "VSS_P$3") (pintype "bidirectional"))
      (node (ref "U603") (pin "2") (pinfunction "GND_2") (pintype "bidirectional"))
      (node (ref "U603") (pin "GND") (pinfunction "GND_GND") (pintype "bidirectional"))
      (node (ref "U701") (pin "5") (pinfunction "GND_5") (pintype "power_in"))
      (node (ref "U702") (pin "4") (pinfunction "GND_4") (pintype "power_in"))
      (node (ref "U801") (pin "23") (pinfunction "VSS_1_23") (pintype "power_in"))
      (node (ref "U801") (pin "35") (pinfunction "VSS_2_35") (pintype "power_in"))
      (node (ref "U801") (pin "47") (pinfunction "VSS_3_47") (pintype "power_in"))
      (node (ref "U801") (pin "8") (pinfunction "VSSA_8") (pintype "power_in"))
      (node (ref "U901") (pin "11") (pinfunction "GND_11") (pintype "power_in"))
      (node (ref "U902") (pin "11") (pinfunction "GND_11") (pintype "power_in"))
      (node (ref "U903") (pin "1") (pinfunction "~{1OE}_1") (pintype "input"))
      (node (ref "U903") (pin "4") (pinfunction "GND_4") (pintype "power_in"))
      (node (ref "X101") (pin "2") (pinfunction "NC_2_2") (pintype "power_in"))
      (node (ref "X101") (pin "4") (pinfunction "NC_4_4") (pintype "power_in"))
      (node (ref "X503") (pin "2") (pinfunction "S_2") (pintype "passive"))
      (node (ref "X801") (pin "2") (pinfunction "NC_2_2") (pintype "power_in"))
      (node (ref "X801") (pin "4") (pinfunction "NC_4_4") (pintype "power_in"))
    )
    (net (code "47") (name "GPIO_EXT_1") (class "Default")
      (node (ref "J403") (pin "6") (pinfunction "6_6") (pintype "passive"))
      (node (ref "U101") (pin "8") (pinfunction "PC14_8") (pintype "bidirectional"))
    )
    (net (code "48") (name "GYRO_DRDY") (class "Default")
      (node (ref "U101") (pin "35") (pinfunction "PB0_35") (pintype "bidirectional"))
      (node (ref "U501") (pin "6") (pinfunction "DRDY/INT2_6") (pintype "output"))
      (node (ref "U502") (pin "6") (pinfunction "DRDY/INT2_6") (pintype "bidirectional"))
      (node (ref "X503") (pin "5") (pinfunction "S_5") (pintype "passive"))
    )
    (net (code "49") (name "IO-BOOT0") (class "Default")
      (node (ref "IO-BOOT1101") (pin "P$1") (pinfunction "P$1_P$1") (pintype "passive"))
      (node (ref "R801") (pin "P$1") (pinfunction "1_P$1") (pintype "passive"))
      (node (ref "U801") (pin "44") (pinfunction "BOOT0_44") (pintype "input"))
    )
    (net (code "50") (name "IO-CH1") (class "Default")
      (node (ref "U801") (pin "10") (pinfunction "PA0_10") (pintype "bidirectional"))
      (node (ref "U902") (pin "9") (pinfunction "A8_9") (pintype "bidirectional"))
    )
    (net (code "51") (name "IO-CH2") (class "Default")
      (node (ref "U801") (pin "11") (pinfunction "PA1_11") (pintype "bidirectional"))
      (node (ref "U902") (pin "8") (pinfunction "A7_8") (pintype "bidirectional"))
    )
    (net (code "52") (name "IO-CH3") (class "Default")
      (node (ref "U801") (pin "45") (pinfunction "PB8_45") (pintype "bidirectional"))
      (node (ref "U902") (pin "7") (pinfunction "A6_7") (pintype "bidirectional"))
    )
    (net (code "53") (name "IO-CH4") (class "Default")
      (node (ref "U801") (pin "46") (pinfunction "PB9_46") (pintype "bidirectional"))
      (node (ref "U902") (pin "6") (pinfunction "A5_6") (pintype "bidirectional"))
    )
    (net (code "54") (name "IO-CH5") (class "Default")
      (node (ref "U801") (pin "16") (pinfunction "PA6_16") (pintype "bidirectional"))
      (node (ref "U902") (pin "5") (pinfunction "A4_5") (pintype "bidirectional"))
    )
    (net (code "55") (name "IO-CH6") (class "Default")
      (node (ref "U801") (pin "17") (pinfunction "PA7_17") (pintype "bidirectional"))
      (node (ref "U902") (pin "4") (pinfunction "A3_4") (pintype "bidirectional"))
    )
    (net (code "56") (name "IO-CH7") (class "Default")
      (node (ref "U801") (pin "18") (pinfunction "PB0_18") (pintype "bidirectional"))
      (node (ref "U902") (pin "3") (pinfunction "A2_3") (pintype "bidirectional"))
    )
    (net (code "57") (name "IO-CH8") (class "Default")
      (node (ref "U801") (pin "19") (pinfunction "PB1_19") (pintype "bidirectional"))
      (node (ref "U902") (pin "1") (pinfunction "A1_1") (pintype "bidirectional"))
    )
    (net (code "58") (name "IO-SWCLK") (class "Default")
      (node (ref "JX802") (pin "4") (pinfunction "S_4") (pintype "passive"))
      (node (ref "U801") (pin "37") (pinfunction "PA14_37") (pintype "bidirectional"))
    )
    (net (code "59") (name "IO-SWDIO") (class "Default")
      (node (ref "JX802") (pin "2") (pinfunction "S_2") (pintype "passive"))
      (node (ref "U801") (pin "34") (pinfunction "PA13_34") (pintype "bidirectional"))
    )
    (net (code "60") (name "IO-SWO") (class "Default")
      (node (ref "JX802") (pin "6") (pinfunction "S_6") (pintype "passive"))
      (node (ref "U801") (pin "39") (pinfunction "PB3_39") (pintype "bidirectional"))
    )
    (net (code "61") (name "IO-USART1_RX") (class "Default")
      (node (ref "J801") (pin "P$3") (pinfunction "P$3_P$3") (pintype "bidirectional"))
      (node (ref "JX801") (pin "2") (pinfunction "+5V_2") (pintype "bidirectional"))
      (node (ref "U801") (pin "31") (pinfunction "PA10_31") (pintype "bidirectional"))
    )
    (net (code "62") (name "IO-USART1_TX") (class "Default")
      (node (ref "JX801") (pin "1") (pinfunction "PPM_1") (pintype "bidirectional"))
      (node (ref "R101") (pin "P$2") (pinfunction "2_P$2") (pintype "passive"))
      (node (ref "U801") (pin "30") (pinfunction "PA9_30") (pintype "bidirectional"))
    )
    (net (code "63") (name "IO-VDD_3V3") (class "Default")
      (node (ref "C1003") (pin "P$1") (pinfunction "1_P$1") (pintype "passive"))
      (node (ref "C1004") (pin "P$1") (pinfunction "1_P$1") (pintype "passive"))
      (node (ref "C802") (pin "P$1") (pinfunction "1_P$1") (pintype "passive"))
      (node (ref "C803") (pin "P$1") (pinfunction "1_P$1") (pintype "passive"))
      (node (ref "C804") (pin "P$1") (pinfunction "1_P$1") (pintype "passive"))
      (node (ref "C901") (pin "P$1") (pinfunction "1_P$1") (pintype "passive"))
      (node (ref "C903") (pin "P$1") (pinfunction "1_P$1") (pintype "passive"))
      (node (ref "D701") (pin "C") (pinfunction "C_C") (pintype "passive"))
      (node (ref "J702") (pin "1") (pinfunction "1_1") (pintype "passive"))
      (node (ref "JX802") (pin "1") (pinfunction "S_1") (pintype "passive"))
      (node (ref "U1002") (pin "7") (pinfunction "VOUT2_7") (pintype "bidirectional"))
      (node (ref "U801") (pin "24") (pinfunction "VDD_1_24") (pintype "power_in"))
      (node (ref "U801") (pin "36") (pinfunction "VDD_2_36") (pintype "power_in"))
      (node (ref "U801") (pin "48") (pinfunction "VDD_3_48") (pintype "power_in"))
      (node (ref "U801") (pin "9") (pinfunction "VDDA_9") (pintype "power_in"))
      (node (ref "U902") (pin "10") (pinfunction "OE_10") (pintype "input"))
      (node (ref "U902") (pin "19") (pinfunction "VCCB_19") (pintype "input"))
      (node (ref "U902") (pin "2") (pinfunction "VCCA_2") (pintype "input"))
      (node (ref "U903") (pin "8") (pinfunction "VCC_8") (pintype "power_in"))
    )
    (net (code "64") (name "IO-VDD_5V5") (class "Default")
      (node (ref "C1001") (pin "P$1") (pinfunction "1_P$1") (pintype "passive"))
      (node (ref "C1005") (pin "P$1") (pinfunction "1_P$1") (pintype "passive"))
      (node (ref "D1001") (pin "3") (pinfunction "CC_3") (pintype "passive"))
      (node (ref "J901") (pin "2") (pinfunction "S_2") (pintype "passive"))
      (node (ref "LED702") (pin "A") (pinfunction "A_A") (pintype "passive"))
      (node (ref "LED703") (pin "A") (pinfunction "A_A") (pintype "passive"))
      (node (ref "LED705") (pin "A") (pinfunction "A_A") (pintype "passive"))
      (node (ref "U1002") (pin "1") (pinfunction "VIN_1") (pintype "bidirectional"))
      (node (ref "U1002") (pin "4") (pinfunction "EN2_4") (pintype "bidirectional"))
    )
    (net (code "65") (name "IO-~{RESET}") (class "Default")
      (node (ref "C801") (pin "P$2") (pinfunction "2_P$2") (pintype "passive"))
      (node (ref "S801") (pin "A1") (pinfunction "1_A1") (pintype "passive"))
      (node (ref "U1002") (pin "3") (pinfunction "POR2_3") (pintype "bidirectional"))
      (node (ref "U801") (pin "7") (pinfunction "NRST_7") (pintype "input"))
    )
    (net (code "66") (name "IO-~{VDD_SERVO_IN_FAULT}") (class "Default")
      (node (ref "U1001") (pin "4") (pinfunction "~{FAULT}_4") (pintype "bidirectional"))
      (node (ref "U801") (pin "38") (pinfunction "PA15_38") (pintype "bidirectional"))
    )
    (net (code "67") (name "MAG_DRDY") (class "Default")
      (node (ref "U101") (pin "36") (pinfunction "PB1_36") (pintype "bidirectional"))
      (node (ref "U504") (pin "9") (pinfunction "INT2_9") (pintype "bidirectional"))
      (node (ref "X503") (pin "4") (pinfunction "S_4") (pintype "passive"))
    )
    (net (code "68") (name "MPU_DRDY") (class "Default")
      (node (ref "U101") (pin "62") (pinfunction "PD15_62") (pintype "bidirectional"))
      (node (ref "U505") (pin "12") (pinfunction "INT_12") (pintype "bidirectional"))
    )
    (net (code "69") (name "Net-(C102-1)") (class "Default")
      (node (ref "C102") (pin "P$1") (pinfunction "1_P$1") (pintype "passive"))
      (node (ref "U101") (pin "12") (pinfunction "OSC_IN_12") (pintype "input"))
      (node (ref "X101") (pin "3") (pinfunction "3_3") (pintype "bidirectional"))
    )
    (net (code "70") (name "Net-(C103-2)") (class "Default")
      (node (ref "C103") (pin "P$2") (pinfunction "2_P$2") (pintype "passive"))
      (node (ref "U101") (pin "13") (pinfunction "OSC_OUT_13") (pintype "output"))
      (node (ref "X101") (pin "1") (pinfunction "1_1") (pintype "bidirectional"))
    )
    (net (code "71") (name "Net-(C504-1)") (class "Default")
      (node (ref "C504") (pin "P$1") (pinfunction "1_P$1") (pintype "passive"))
      (node (ref "U501") (pin "14") (pinfunction "PLLFILT_14") (pintype "bidirectional"))
    )
    (net (code "72") (name "Net-(C505-1)") (class "Default")
      (node (ref "C505") (pin "P$1") (pinfunction "1_P$1") (pintype "passive"))
      (node (ref "U502") (pin "14") (pinfunction "CAP_14") (pintype "bidirectional"))
    )
    (net (code "73") (name "Net-(C509-1)") (class "Default")
      (node (ref "C509") (pin "P$1") (pinfunction "1_P$1") (pintype "passive"))
      (node (ref "U504") (pin "15") (pinfunction "C1_15") (pintype "bidirectional"))
    )
    (net (code "74") (name "Net-(C510-1)") (class "Default")
      (node (ref "C510") (pin "P$1") (pinfunction "1_P$1") (pintype "passive"))
      (node (ref "U504") (pin "2") (pinfunction "SETC_2") (pintype "bidirectional"))
    )
    (net (code "75") (name "Net-(C510-2)") (class "Default")
      (node (ref "C510") (pin "P$2") (pinfunction "2_P$2") (pintype "passive"))
      (node (ref "U504") (pin "3") (pinfunction "SETP_3") (pintype "bidirectional"))
    )
    (net (code "76") (name "Net-(C512-1)") (class "Default")
      (node (ref "C512") (pin "P$1") (pinfunction "1_P$1") (pintype "passive"))
      (node (ref "U505") (pin "10") (pinfunction "REGOUT_10") (pintype "bidirectional"))
    )
    (net (code "77") (name "Net-(C515-1)") (class "Default")
      (node (ref "C515") (pin "P$1") (pinfunction "1_P$1") (pintype "passive"))
      (node (ref "U505") (pin "20") (pinfunction "CPOUT_20") (pintype "bidirectional"))
    )
    (net (code "78") (name "Net-(C601-1)") (class "Default")
      (node (ref "C601") (pin "P$1") (pinfunction "1_P$1") (pintype "passive"))
      (node (ref "C615") (pin "P$1") (pinfunction "1_P$1") (pintype "passive"))
      (node (ref "L603") (pin "P$2") (pinfunction "P$2_P$2") (pintype "bidirectional"))
      (node (ref "R603") (pin "P$1") (pinfunction "1_P$1") (pintype "passive"))
      (node (ref "U603") (pin "1") (pinfunction "VIN_1") (pintype "bidirectional"))
      (node (ref "U603") (pin "4") (pinfunction "EN2_4") (pintype "bidirectional"))
    )
    (net (code "79") (name "Net-(C602-2)") (class "Default")
      (node (ref "C602") (pin "P$2") (pinfunction "2_P$2") (pintype "passive"))
      (node (ref "U603") (pin "6") (pinfunction "CSET_6") (pintype "bidirectional"))
    )
    (net (code "80") (name "Net-(C611-1)") (class "Default")
      (node (ref "C611") (pin "P$1") (pinfunction "1_P$1") (pintype "passive"))
      (node (ref "U101") (pin "49") (pinfunction "VCAP_1_49") (pintype "power_in"))
    )
    (net (code "81") (name "Net-(C613-1)") (class "Default")
      (node (ref "C613") (pin "P$1") (pinfunction "1_P$1") (pintype "passive"))
      (node (ref "U101") (pin "73") (pinfunction "VCAP_2_73") (pintype "power_in"))
    )
    (net (code "82") (name "Net-(C703-1)") (class "Default")
      (node (ref "C703") (pin "P$1") (pinfunction "1_P$1") (pintype "passive"))
      (node (ref "J701") (pin "1") (pinfunction "1_1") (pintype "passive"))
      (node (ref "R703") (pin "P$1") (pinfunction "1_P$1") (pintype "passive"))
      (node (ref "U702") (pin "1") (pinfunction "OUT_1") (pintype "output"))
    )
    (net (code "83") (name "Net-(C704-1)") (class "Default")
      (node (ref "C704") (pin "P$1") (pinfunction "1_P$1") (pintype "passive"))
      (node (ref "R705") (pin "P$1") (pinfunction "1_P$1") (pintype "passive"))
      (node (ref "U702") (pin "6") (pinfunction "VCC_6") (pintype "bidirectional"))
    )
    (net (code "84") (name "Net-(C805-1)") (class "Default")
      (node (ref "C805") (pin "P$1") (pinfunction "1_P$1") (pintype "passive"))
      (node (ref "U801") (pin "5") (pinfunction "PD0/OSC<=_5") (pintype "bidirectional"))
      (node (ref "X801") (pin "3") (pinfunction "3_3") (pintype "bidirectional"))
    )
    (net (code "85") (name "Net-(C806-2)") (class "Default")
      (node (ref "C806") (pin "P$2") (pinfunction "2_P$2") (pintype "passive"))
      (node (ref "U801") (pin "6") (pinfunction "PD1/OSC=>_6") (pintype "bidirectional"))
      (node (ref "X801") (pin "1") (pinfunction "1_1") (pintype "bidirectional"))
    )
    (net (code "86") (name "Net-(C1002-1)") (class "Default")
      (node (ref "C1002") (pin "P$1") (pinfunction "1_P$1") (pintype "passive"))
      (node (ref "U1002") (pin "6") (pinfunction "CSET_6") (pintype "bidirectional"))
    )
    (net (code "87") (name "Net-(C1105-1)") (class "Default")
      (node (ref "C1105") (pin "P$1") (pinfunction "1_P$1") (pintype "passive"))
      (node (ref "U1101") (pin "P$18") (pinfunction "VS1_P$18") (pintype "bidirectional"))
      (node (ref "U1102") (pin "P$1") (pinfunction "S_P$1") (pintype "passive"))
      (node (ref "U1102") (pin "P$3") (pinfunction "S_P$3") (pintype "passive"))
    )
    (net (code "88") (name "Net-(C1106-1)") (class "Default")
      (node (ref "C1106") (pin "P$1") (pinfunction "1_P$1") (pintype "passive"))
      (node (ref "U1101") (pin "P$16") (pinfunction "VS2_P$16") (pintype "bidirectional"))
      (node (ref "U1103") (pin "P$1") (pinfunction "S_P$1") (pintype "passive"))
      (node (ref "U1103") (pin "P$3") (pinfunction "S_P$3") (pintype "passive"))
    )
    (net (code "89") (name "Net-(C1107-1)") (class "Default")
      (node (ref "C1107") (pin "P$1") (pinfunction "1_P$1") (pintype "passive"))
      (node (ref "U1101") (pin "P$14") (pinfunction "VS3_P$14") (pintype "bidirectional"))
      (node (ref "U1104") (pin "P$1") (pinfunction "S_P$1") (pintype "passive"))
      (node (ref "U1104") (pin "P$3") (pinfunction "S_P$3") (pintype "passive"))
    )
    (net (code "90") (name "Net-(C1108-1)") (class "Default")
      (node (ref "C1108") (pin "P$1") (pinfunction "1_P$1") (pintype "passive"))
      (node (ref "R1105") (pin "P$2") (pinfunction "2_P$2") (pintype "passive"))
      (node (ref "R1106") (pin "P$1") (pinfunction "1_P$1") (pintype "passive"))
      (node (ref "U1101") (pin "P$1") (pinfunction "UV1_P$1") (pintype "bidirectional"))
    )
    (net (code "91") (name "Net-(C1109-1)") (class "Default")
      (node (ref "C1109") (pin "P$1") (pinfunction "1_P$1") (pintype "passive"))
      (node (ref "R1109") (pin "P$2") (pinfunction "2_P$2") (pintype "passive"))
      (node (ref "R1110") (pin "P$1") (pinfunction "1_P$1") (pintype "passive"))
      (node (ref "U1101") (pin "P$3") (pinfunction "UV2_P$3") (pintype "bidirectional"))
    )
    (net (code "92") (name "Net-(C1110-1)") (class "Default")
      (node (ref "C1110") (pin "P$1") (pinfunction "1_P$1") (pintype "passive"))
      (node (ref "R1112") (pin "P$2") (pinfunction "2_P$2") (pintype "passive"))
      (node (ref "R1113") (pin "P$1") (pinfunction "1_P$1") (pintype "passive"))
      (node (ref "U1101") (pin "P$5") (pinfunction "UV3_P$5") (pintype "bidirectional"))
    )
    (net (code "93") (name "Net-(D201-PadC)") (class "Default")
      (node (ref "D201") (pin "C") (pinfunction "C_C") (pintype "passive"))
      (node (ref "J201") (pin "1") (pinfunction "1_1") (pintype "passive"))
      (node (ref "L201") (pin "P$2") (pinfunction "P$2_P$2") (pintype "bidirectional"))
    )
    (net (code "94") (name "Net-(D202-PadC)") (class "Default")
      (node (ref "D202") (pin "C") (pinfunction "C_C") (pintype "passive"))
      (node (ref "J202") (pin "1") (pinfunction "1_1") (pintype "passive"))
      (node (ref "L202") (pin "P$2") (pinfunction "P$2_P$2") (pintype "bidirectional"))
    )
    (net (code "95") (name "Net-(D203-PadC)") (class "Default")
      (node (ref "D203") (pin "C") (pinfunction "C_C") (pintype "passive"))
      (node (ref "J203") (pin "1") (pinfunction "1_1") (pintype "passive"))
      (node (ref "J204") (pin "1") (pinfunction "1_1") (pintype "passive"))
      (node (ref "L203") (pin "P$2") (pinfunction "P$2_P$2") (pintype "bidirectional"))
    )
    (net (code "96") (name "Net-(D401-PadC)") (class "Default")
      (node (ref "D401") (pin "C") (pinfunction "C_C") (pintype "passive"))
      (node (ref "J401") (pin "1") (pinfunction "1_1") (pintype "passive"))
      (node (ref "J402") (pin "1") (pinfunction "1_1") (pintype "passive"))
      (node (ref "L401") (pin "P$2") (pinfunction "P$2_P$2") (pintype "bidirectional"))
    )
    (net (code "97") (name "Net-(D402-PadC)") (class "Default")
      (node (ref "D402") (pin "C") (pinfunction "C_C") (pintype "passive"))
      (node (ref "J403") (pin "1") (pinfunction "1_1") (pintype "passive"))
      (node (ref "L402") (pin "P$2") (pinfunction "P$2_P$2") (pintype "bidirectional"))
    )
    (net (code "98") (name "Net-(D403-PadC)") (class "Default")
      (node (ref "D403") (pin "C") (pinfunction "C_C") (pintype "passive"))
      (node (ref "J404") (pin "1") (pinfunction "1_1") (pintype "passive"))
      (node (ref "L404") (pin "P$2") (pinfunction "P$2_P$2") (pintype "bidirectional"))
    )
    (net (code "99") (name "Net-(D404-PadC)") (class "Default")
      (node (ref "D404") (pin "C") (pinfunction "C_C") (pintype "passive"))
      (node (ref "J405") (pin "1") (pinfunction "1_1") (pintype "passive"))
      (node (ref "L403") (pin "P$2") (pinfunction "P$2_P$2") (pintype "bidirectional"))
    )
    (net (code "100") (name "Net-(D904-C)") (class "Default")
      (node (ref "D903") (pin "C") (pinfunction "C_C") (pintype "passive"))
      (node (ref "D904") (pin "CATHODE") (pinfunction "C_CATHODE") (pintype "passive"))
      (node (ref "L901") (pin "P$1") (pinfunction "P$1_P$1") (pintype "bidirectional"))
    )
    (net (code "101") (name "Net-(D1001-A1)") (class "Default")
      (node (ref "D1001") (pin "1") (pinfunction "A1_1") (pintype "passive"))
      (node (ref "F1001") (pin "2") (pinfunction "2_2") (pintype "bidirectional"))
    )
    (net (code "102") (name "Net-(D1001-A2)") (class "Default")
      (node (ref "D1001") (pin "2") (pinfunction "A2_2") (pintype "passive"))
      (node (ref "U1001") (pin "8") (pinfunction "OUT_8") (pintype "bidirectional"))
    )
    (net (code "103") (name "Net-(J301-2)") (class "Default")
      (node (ref "J301") (pin "D-") (pinfunction "2_D-") (pintype "bidirectional"))
      (node (ref "J302") (pin "3") (pinfunction "3_3") (pintype "passive"))
      (node (ref "U302") (pin "1") (pinfunction "D1I_1") (pintype "bidirectional"))
    )
    (net (code "104") (name "Net-(J301-3)") (class "Default")
      (node (ref "J301") (pin "D+") (pinfunction "3_D+") (pintype "bidirectional"))
      (node (ref "J302") (pin "2") (pinfunction "2_2") (pintype "passive"))
      (node (ref "U302") (pin "3") (pinfunction "D2I_3") (pintype "bidirectional"))
    )
    (net (code "105") (name "Net-(J901A-S)") (class "Default")
      (node (ref "J901") (pin "1") (pinfunction "S_1") (pintype "passive"))
      (node (ref "R909") (pin "P$2") (pinfunction "2_P$2") (pintype "passive"))
    )
    (net (code "106") (name "Net-(J901B-S)") (class "Default")
      (node (ref "J901") (pin "10") (pinfunction "S_10") (pintype "passive"))
      (node (ref "R914") (pin "P$2") (pinfunction "2_P$2") (pintype "passive"))
    )
    (net (code "107") (name "Net-(J901C-S)") (class "Default")
      (node (ref "J901") (pin "13") (pinfunction "S_13") (pintype "passive"))
      (node (ref "R906") (pin "P$2") (pinfunction "2_P$2") (pintype "passive"))
    )
    (net (code "108") (name "Net-(J901D-S)") (class "Default")
      (node (ref "J901") (pin "16") (pinfunction "S_16") (pintype "passive"))
      (node (ref "R915") (pin "P$2") (pinfunction "2_P$2") (pintype "passive"))
    )
    (net (code "109") (name "Net-(J901E-S)") (class "Default")
      (node (ref "J901") (pin "19") (pinfunction "S_19") (pintype "passive"))
      (node (ref "R907") (pin "P$2") (pinfunction "2_P$2") (pintype "passive"))
    )
    (net (code "110") (name "Net-(J901G-S)") (class "Default")
      (node (ref "J901") (pin "22") (pinfunction "S_22") (pintype "passive"))
      (node (ref "R916") (pin "P$2") (pinfunction "2_P$2") (pintype "passive"))
    )
    (net (code "111") (name "Net-(J901H-S)") (class "Default")
      (node (ref "J901") (pin "25") (pinfunction "S_25") (pintype "passive"))
      (node (ref "R908") (pin "P$2") (pinfunction "2_P$2") (pintype "passive"))
    )
    (net (code "112") (name "Net-(J901I-S)") (class "Default")
      (node (ref "J901") (pin "28") (pinfunction "S_28") (pintype "passive"))
      (node (ref "R917") (pin "P$2") (pinfunction "2_P$2") (pintype "passive"))
    )
    (net (code "113") (name "Net-(J901J-S)") (class "Default")
      (node (ref "J901") (pin "31") (pinfunction "S_31") (pintype "passive"))
      (node (ref "R902") (pin "P$2") (pinfunction "2_P$2") (pintype "passive"))
    )
    (net (code "114") (name "Net-(J901K-S)") (class "Default")
      (node (ref "J901") (pin "34") (pinfunction "S_34") (pintype "passive"))
      (node (ref "R911") (pin "P$2") (pinfunction "2_P$2") (pintype "passive"))
    )
    (net (code "115") (name "Net-(J901L-S)") (class "Default")
      (node (ref "J901") (pin "37") (pinfunction "S_37") (pintype "passive"))
      (node (ref "R903") (pin "P$2") (pinfunction "2_P$2") (pintype "passive"))
    )
    (net (code "116") (name "Net-(J901M-S)") (class "Default")
      (node (ref "J901") (pin "4") (pinfunction "S_4") (pintype "passive"))
      (node (ref "R910") (pin "P$2") (pinfunction "2_P$2") (pintype "passive"))
    )
    (net (code "117") (name "Net-(J901N-S)") (class "Default")
      (node (ref "J901") (pin "40") (pinfunction "S_40") (pintype "passive"))
      (node (ref "R912") (pin "P$2") (pinfunction "2_P$2") (pintype "passive"))
    )
    (net (code "118") (name "Net-(J901O-S)") (class "Default")
      (node (ref "J901") (pin "43") (pinfunction "S_43") (pintype "passive"))
      (node (ref "R904") (pin "P$2") (pinfunction "2_P$2") (pintype "passive"))
    )
    (net (code "119") (name "Net-(J901P-S)") (class "Default")
      (node (ref "J901") (pin "46") (pinfunction "S_46") (pintype "passive"))
      (node (ref "R913") (pin "P$2") (pinfunction "2_P$2") (pintype "passive"))
    )
    (net (code "120") (name "Net-(J901Q-S)") (class "Default")
      (node (ref "J901") (pin "7") (pinfunction "S_7") (pintype "passive"))
      (node (ref "R905") (pin "P$2") (pinfunction "2_P$2") (pintype "passive"))
    )
    (net (code "121") (name "Net-(L701-2)") (class "Default")
      (node (ref "L701") (pin "P$2") (pinfunction "2_P$2") (pintype "passive"))
      (node (ref "U702") (pin "5") (pinfunction "SW_5") (pintype "passive"))
    )
    (net (code "122") (name "Net-(R101-1)") (class "Default")
      (node (ref "R101") (pin "P$1") (pinfunction "1_P$1") (pintype "passive"))
      (node (ref "U101") (pin "69") (pinfunction "PA10_69") (pintype "bidirectional"))
    )
    (net (code "123") (name "Net-(R102-1)") (class "Default")
      (node (ref "R102") (pin "P$1") (pinfunction "1_P$1") (pintype "passive"))
      (node (ref "U101") (pin "37") (pinfunction "PB2_37") (pintype "bidirectional"))
    )
    (net (code "124") (name "Net-(R201-1)") (class "Default")
      (node (ref "R201") (pin "P$1") (pinfunction "1_P$1") (pintype "passive"))
      (node (ref "U201") (pin "20") (pinfunction "B1_20") (pintype "bidirectional"))
    )
    (net (code "125") (name "Net-(R202-1)") (class "Default")
      (node (ref "R202") (pin "P$1") (pinfunction "1_P$1") (pintype "passive"))
      (node (ref "U201") (pin "17") (pinfunction "B3_17") (pintype "bidirectional"))
    )
    (net (code "126") (name "Net-(R203-1)") (class "Default")
      (node (ref "R203") (pin "P$1") (pinfunction "1_P$1") (pintype "passive"))
      (node (ref "U201") (pin "15") (pinfunction "B5_15") (pintype "bidirectional"))
    )
    (net (code "127") (name "Net-(R204-1)") (class "Default")
      (node (ref "R204") (pin "P$1") (pinfunction "1_P$1") (pintype "passive"))
      (node (ref "U201") (pin "13") (pinfunction "B7_13") (pintype "bidirectional"))
    )
    (net (code "128") (name "Net-(R205-1)") (class "Default")
      (node (ref "R205") (pin "P$1") (pinfunction "1_P$1") (pintype "passive"))
      (node (ref "U202") (pin "17") (pinfunction "B3_17") (pintype "bidirectional"))
    )
    (net (code "129") (name "Net-(R206-1)") (class "Default")
      (node (ref "R206") (pin "P$1") (pinfunction "1_P$1") (pintype "passive"))
      (node (ref "U202") (pin "15") (pinfunction "B5_15") (pintype "bidirectional"))
    )
    (net (code "130") (name "Net-(R207-1)") (class "Default")
      (node (ref "R207") (pin "P$1") (pinfunction "1_P$1") (pintype "passive"))
      (node (ref "U202") (pin "13") (pinfunction "B7_13") (pintype "bidirectional"))
    )
    (net (code "131") (name "Net-(R208-1)") (class "Default")
      (node (ref "R208") (pin "P$1") (pinfunction "1_P$1") (pintype "passive"))
      (node (ref "U201") (pin "18") (pinfunction "B2_18") (pintype "bidirectional"))
    )
    (net (code "132") (name "Net-(R209-1)") (class "Default")
      (node (ref "R209") (pin "P$1") (pinfunction "1_P$1") (pintype "passive"))
      (node (ref "U201") (pin "16") (pinfunction "B4_16") (pintype "bidirectional"))
    )
    (net (code "133") (name "Net-(R210-1)") (class "Default")
      (node (ref "R210") (pin "P$1") (pinfunction "1_P$1") (pintype "passive"))
      (node (ref "U201") (pin "14") (pinfunction "B6_14") (pintype "bidirectional"))
    )
    (net (code "134") (name "Net-(R211-1)") (class "Default")
      (node (ref "R211") (pin "P$1") (pinfunction "1_P$1") (pintype "passive"))
      (node (ref "U201") (pin "12") (pinfunction "B8_12") (pintype "bidirectional"))
    )
    (net (code "135") (name "Net-(R212-1)") (class "Default")
      (node (ref "R212") (pin "P$1") (pinfunction "1_P$1") (pintype "passive"))
      (node (ref "U202") (pin "16") (pinfunction "B4_16") (pintype "bidirectional"))
    )
    (net (code "136") (name "Net-(R213-1)") (class "Default")
      (node (ref "R213") (pin "P$1") (pinfunction "1_P$1") (pintype "passive"))
      (node (ref "U202") (pin "14") (pinfunction "B6_14") (pintype "bidirectional"))
    )
    (net (code "137") (name "Net-(R214-1)") (class "Default")
      (node (ref "R214") (pin "P$1") (pinfunction "1_P$1") (pintype "passive"))
      (node (ref "U202") (pin "12") (pinfunction "B8_12") (pintype "bidirectional"))
    )
    (net (code "138") (name "Net-(R215-2)") (class "Default")
      (node (ref "J203") (pin "4") (pinfunction "4_4") (pintype "passive"))
      (node (ref "R215") (pin "P$2") (pinfunction "2_P$2") (pintype "passive"))
    )
    (net (code "139") (name "Net-(R216-2)") (class "Default")
      (node (ref "J203") (pin "5") (pinfunction "5_5") (pintype "passive"))
      (node (ref "R216") (pin "P$2") (pinfunction "2_P$2") (pintype "passive"))
    )
    (net (code "140") (name "Net-(R404-2)") (class "Default")
      (node (ref "J401") (pin "2") (pinfunction "2_2") (pintype "passive"))
      (node (ref "R404") (pin "P$2") (pinfunction "2_P$2") (pintype "passive"))
    )
    (net (code "141") (name "Net-(R405-2)") (class "Default")
      (node (ref "J401") (pin "3") (pinfunction "3_3") (pintype "passive"))
      (node (ref "R405") (pin "P$2") (pinfunction "2_P$2") (pintype "passive"))
    )
    (net (code "142") (name "Net-(R407-2)") (class "Default")
      (node (ref "J404") (pin "2") (pinfunction "2_2") (pintype "passive"))
      (node (ref "R407") (pin "P$2") (pinfunction "2_P$2") (pintype "passive"))
    )
    (net (code "143") (name "Net-(R408-2)") (class "Default")
      (node (ref "J404") (pin "4") (pinfunction "4_4") (pintype "passive"))
      (node (ref "R408") (pin "P$2") (pinfunction "2_P$2") (pintype "passive"))
    )
    (net (code "144") (name "Net-(R608-2)") (class "Default")
      (node (ref "D602") (pin "C") (pinfunction "C_C") (pintype "passive"))
      (node (ref "R608") (pin "P$2") (pinfunction "2_P$2") (pintype "passive"))
    )
    (net (code "145") (name "Net-(R616-1)") (class "Default")
      (node (ref "R616") (pin "P$1") (pinfunction "1_P$1") (pintype "passive"))
      (node (ref "U602") (pin "7") (pinfunction "ILIM_7") (pintype "bidirectional"))
    )
    (net (code "146") (name "Net-(R617-1)") (class "Default")
      (node (ref "R617") (pin "P$1") (pinfunction "1_P$1") (pintype "passive"))
      (node (ref "U601") (pin "7") (pinfunction "ILIM_7") (pintype "bidirectional"))
    )
    (net (code "147") (name "Net-(R701-1)") (class "Default")
      (node (ref "R701") (pin "P$1") (pinfunction "1_P$1") (pintype "passive"))
      (node (ref "U702") (pin "7") (pinfunction "+IN_7") (pintype "input"))
    )
    (net (code "148") (name "Net-(R702-1)") (class "Default")
      (node (ref "R702") (pin "P$1") (pinfunction "1_P$1") (pintype "passive"))
      (node (ref "R703") (pin "P$2") (pinfunction "2_P$2") (pintype "passive"))
      (node (ref "U702") (pin "8") (pinfunction "-IN_8") (pintype "input"))
    )
    (net (code "149") (name "Net-(R704-2)") (class "Default")
      (node (ref "R704") (pin "P$2") (pinfunction "2_P$2") (pintype "passive"))
      (node (ref "U701") (pin "6") (pinfunction "REXT_6") (pintype "bidirectional"))
    )
    (net (code "150") (name "Net-(R705-2)") (class "Default")
      (node (ref "R705") (pin "P$2") (pinfunction "2_P$2") (pintype "passive"))
      (node (ref "R706") (pin "P$1") (pinfunction "1_P$1") (pintype "passive"))
      (node (ref "U702") (pin "2") (pinfunction "FB_2") (pintype "bidirectional"))
    )
    (net (code "151") (name "Net-(R707-2)") (class "Default")
      (node (ref "R707") (pin "P$2") (pinfunction "2_P$2") (pintype "passive"))
      (node (ref "R735") (pin "P$1") (pinfunction "1_P$1") (pintype "passive"))
    )
    (net (code "152") (name "Net-(R708-2)") (class "Default")
      (node (ref "LED702") (pin "C") (pinfunction "C_C") (pintype "passive"))
      (node (ref "R708") (pin "P$2") (pinfunction "2_P$2") (pintype "passive"))
    )
    (net (code "153") (name "Net-(R709-2)") (class "Default")
      (node (ref "R709") (pin "P$2") (pinfunction "2_P$2") (pintype "passive"))
      (node (ref "R736") (pin "P$1") (pinfunction "1_P$1") (pintype "passive"))
    )
    (net (code "154") (name "Net-(R710-1)") (class "Default")
      (node (ref "J702") (pin "2") (pinfunction "2_2") (pintype "passive"))
      (node (ref "R710") (pin "P$1") (pinfunction "1_P$1") (pintype "passive"))
    )
    (net (code "155") (name "Net-(R711-2)") (class "Default")
      (node (ref "LED704") (pin "C") (pinfunction "C_C") (pintype "passive"))
      (node (ref "R711") (pin "P$2") (pinfunction "2_P$2") (pintype "passive"))
    )
    (net (code "156") (name "Net-(R712-2)") (class "Default")
      (node (ref "LED705") (pin "C") (pinfunction "C_C") (pintype "passive"))
      (node (ref "R712") (pin "P$2") (pinfunction "2_P$2") (pintype "passive"))
    )
    (net (code "157") (name "Net-(R735-2)") (class "Default")
      (node (ref "LED701") (pin "C") (pinfunction "C_C") (pintype "passive"))
      (node (ref "R735") (pin "P$2") (pinfunction "2_P$2") (pintype "passive"))
    )
    (net (code "158") (name "Net-(R736-2)") (class "Default")
      (node (ref "LED703") (pin "C") (pinfunction "C_C") (pintype "passive"))
      (node (ref "R736") (pin "P$2") (pinfunction "2_P$2") (pintype "passive"))
    )
    (net (code "159") (name "Net-(R802-1)") (class "Default")
      (node (ref "R802") (pin "P$1") (pinfunction "1_P$1") (pintype "passive"))
      (node (ref "U801") (pin "20") (pinfunction "PB2_20") (pintype "bidirectional"))
    )
    (net (code "160") (name "Net-(R803-1)") (class "Default")
      (node (ref "R803") (pin "P$1") (pinfunction "1_P$1") (pintype "passive"))
      (node (ref "U801") (pin "12") (pinfunction "PA2_12") (pintype "bidirectional"))
    )
    (net (code "161") (name "Net-(R804-1)") (class "Default")
      (node (ref "R804") (pin "P$1") (pinfunction "1_P$1") (pintype "passive"))
      (node (ref "U801") (pin "13") (pinfunction "PA3_13") (pintype "bidirectional"))
    )
    (net (code "162") (name "Net-(R901-2)") (class "Default")
      (node (ref "D902") (pin "C") (pinfunction "C_C") (pintype "passive"))
      (node (ref "R901") (pin "P$2") (pinfunction "2_P$2") (pintype "passive"))
      (node (ref "R910") (pin "P$1") (pinfunction "1_P$1") (pintype "passive"))
      (node (ref "U903") (pin "3") (pinfunction "2Y_3") (pintype "bidirectional"))
    )
    (net (code "163") (name "Net-(R902-1)") (class "Default")
      (node (ref "R902") (pin "P$1") (pinfunction "1_P$1") (pintype "passive"))
      (node (ref "U901") (pin "20") (pinfunction "B1_20") (pintype "bidirectional"))
    )
    (net (code "164") (name "Net-(R903-1)") (class "Default")
      (node (ref "R903") (pin "P$1") (pinfunction "1_P$1") (pintype "passive"))
      (node (ref "U901") (pin "17") (pinfunction "B3_17") (pintype "bidirectional"))
    )
    (net (code "165") (name "Net-(R904-1)") (class "Default")
      (node (ref "R904") (pin "P$1") (pinfunction "1_P$1") (pintype "passive"))
      (node (ref "U901") (pin "15") (pinfunction "B5_15") (pintype "bidirectional"))
    )
    (net (code "166") (name "Net-(R905-1)") (class "Default")
      (node (ref "R905") (pin "P$1") (pinfunction "1_P$1") (pintype "passive"))
      (node (ref "U902") (pin "20") (pinfunction "B1_20") (pintype "bidirectional"))
    )
    (net (code "167") (name "Net-(R906-1)") (class "Default")
      (node (ref "R906") (pin "P$1") (pinfunction "1_P$1") (pintype "passive"))
      (node (ref "U902") (pin "17") (pinfunction "B3_17") (pintype "bidirectional"))
    )
    (net (code "168") (name "Net-(R907-1)") (class "Default")
      (node (ref "R907") (pin "P$1") (pinfunction "1_P$1") (pintype "passive"))
      (node (ref "U902") (pin "15") (pinfunction "B5_15") (pintype "bidirectional"))
    )
    (net (code "169") (name "Net-(R908-1)") (class "Default")
      (node (ref "R908") (pin "P$1") (pinfunction "1_P$1") (pintype "passive"))
      (node (ref "U902") (pin "13") (pinfunction "B7_13") (pintype "bidirectional"))
    )
    (net (code "170") (name "Net-(R911-1)") (class "Default")
      (node (ref "R911") (pin "P$1") (pinfunction "1_P$1") (pintype "passive"))
      (node (ref "U901") (pin "18") (pinfunction "B2_18") (pintype "bidirectional"))
    )
    (net (code "171") (name "Net-(R912-1)") (class "Default")
      (node (ref "R912") (pin "P$1") (pinfunction "1_P$1") (pintype "passive"))
      (node (ref "U901") (pin "16") (pinfunction "B4_16") (pintype "bidirectional"))
    )
    (net (code "172") (name "Net-(R913-1)") (class "Default")
      (node (ref "R913") (pin "P$1") (pinfunction "1_P$1") (pintype "passive"))
      (node (ref "U901") (pin "14") (pinfunction "B6_14") (pintype "bidirectional"))
    )
    (net (code "173") (name "Net-(R914-1)") (class "Default")
      (node (ref "R914") (pin "P$1") (pinfunction "1_P$1") (pintype "passive"))
      (node (ref "U902") (pin "18") (pinfunction "B2_18") (pintype "bidirectional"))
    )
    (net (code "174") (name "Net-(R915-1)") (class "Default")
      (node (ref "R915") (pin "P$1") (pinfunction "1_P$1") (pintype "passive"))
      (node (ref "U902") (pin "16") (pinfunction "B4_16") (pintype "bidirectional"))
    )
    (net (code "175") (name "Net-(R916-1)") (class "Default")
      (node (ref "R916") (pin "P$1") (pinfunction "1_P$1") (pintype "passive"))
      (node (ref "U902") (pin "14") (pinfunction "B6_14") (pintype "bidirectional"))
    )
    (net (code "176") (name "Net-(R917-1)") (class "Default")
      (node (ref "R917") (pin "P$1") (pinfunction "1_P$1") (pintype "passive"))
      (node (ref "U902") (pin "12") (pinfunction "B8_12") (pintype "bidirectional"))
    )
    (net (code "177") (name "Net-(R918-2)") (class "Default")
      (node (ref "R918") (pin "P$2") (pinfunction "2_P$2") (pintype "passive"))
      (node (ref "R922") (pin "P$1") (pinfunction "1_P$1") (pintype "passive"))
    )
    (net (code "178") (name "Net-(R1001-2)") (class "Default")
      (node (ref "R1001") (pin "P$2") (pinfunction "2_P$2") (pintype "passive"))
      (node (ref "U1001") (pin "7") (pinfunction "ILIM_7") (pintype "bidirectional"))
    )
    (net (code "179") (name "Net-(R1101-2)") (class "Default")
      (node (ref "L1101") (pin "P$2") (pinfunction "P$2_P$2") (pintype "bidirectional"))
      (node (ref "R1101") (pin "P$2") (pinfunction "2_P$2") (pintype "passive"))
    )
    (net (code "180") (name "Net-(R1102-2)") (class "Default")
      (node (ref "L1102") (pin "P$2") (pinfunction "P$2_P$2") (pintype "bidirectional"))
      (node (ref "R1102") (pin "P$2") (pinfunction "2_P$2") (pintype "passive"))
    )
    (net (code "181") (name "Net-(R1103-1)") (class "Default")
      (node (ref "J601") (pin "4") (pinfunction "4_4") (pintype "passive"))
      (node (ref "L1102") (pin "P$1") (pinfunction "P$1_P$1") (pintype "bidirectional"))
      (node (ref "R1103") (pin "P$1") (pinfunction "1_P$1") (pintype "passive"))
    )
    (net (code "182") (name "Net-(R1104-1)") (class "Default")
      (node (ref "J601") (pin "3") (pinfunction "3_3") (pintype "passive"))
      (node (ref "L1101") (pin "P$1") (pinfunction "P$1_P$1") (pintype "bidirectional"))
      (node (ref "R1104") (pin "P$1") (pinfunction "1_P$1") (pintype "passive"))
    )
    (net (code "183") (name "Net-(R1106-2)") (class "Default")
      (node (ref "R1106") (pin "P$2") (pinfunction "2_P$2") (pintype "passive"))
      (node (ref "R1107") (pin "P$1") (pinfunction "1_P$1") (pintype "passive"))
      (node (ref "U1101") (pin "P$2") (pinfunction "OV1_P$2") (pintype "bidirectional"))
    )
    (net (code "184") (name "Net-(R1110-2)") (class "Default")
      (node (ref "R1110") (pin "P$2") (pinfunction "2_P$2") (pintype "passive"))
      (node (ref "R1111") (pin "P$1") (pinfunction "1_P$1") (pintype "passive"))
      (node (ref "U1101") (pin "P$4") (pinfunction "OV2_P$4") (pintype "bidirectional"))
    )
    (net (code "185") (name "Net-(R1113-2)") (class "Default")
      (node (ref "R1113") (pin "P$2") (pinfunction "2_P$2") (pintype "passive"))
      (node (ref "R1114") (pin "P$1") (pinfunction "1_P$1") (pintype "passive"))
      (node (ref "U1101") (pin "P$6") (pinfunction "OV3_P$6") (pintype "bidirectional"))
    )
    (net (code "186") (name "Net-(R1115-2)") (class "Default")
      (node (ref "R1115") (pin "P$2") (pinfunction "2_P$2") (pintype "passive"))
      (node (ref "U1101") (pin "P$24") (pinfunction "HYS_P$24") (pintype "bidirectional"))
    )
    (net (code "187") (name "Net-(U701-OUT0)") (class "Default")
      (node (ref "U701") (pin "9") (pinfunction "OUT0_9") (pintype "open_collector"))
      (node (ref "U703") (pin "C1") (pinfunction "C_C1") (pintype "passive"))
    )
    (net (code "188") (name "Net-(U701-OUT1)") (class "Default")
      (node (ref "U701") (pin "8") (pinfunction "OUT1_8") (pintype "open_collector"))
      (node (ref "U703") (pin "C2") (pinfunction "C_C2") (pintype "passive"))
    )
    (net (code "189") (name "Net-(U701-OUT2)") (class "Default")
      (node (ref "U701") (pin "7") (pinfunction "OUT2_7") (pintype "open_collector"))
      (node (ref "U703") (pin "C3") (pinfunction "C_C3") (pintype "passive"))
    )
    (net (code "190") (name "Net-(U1101-G1)") (class "Default")
      (node (ref "U1101") (pin "P$17") (pinfunction "G1_P$17") (pintype "bidirectional"))
      (node (ref "U1102") (pin "P$2") (pinfunction "G_P$2") (pintype "passive"))
      (node (ref "U1102") (pin "P$4") (pinfunction "G_P$4") (pintype "passive"))
    )
    (net (code "191") (name "Net-(U1101-G2)") (class "Default")
      (node (ref "U1101") (pin "P$15") (pinfunction "G2_P$15") (pintype "bidirectional"))
      (node (ref "U1103") (pin "P$2") (pinfunction "G_P$2") (pintype "passive"))
      (node (ref "U1103") (pin "P$4") (pinfunction "G_P$4") (pintype "passive"))
    )
    (net (code "192") (name "Net-(U1101-G3)") (class "Default")
      (node (ref "U1101") (pin "P$13") (pinfunction "G3_P$13") (pintype "bidirectional"))
      (node (ref "U1104") (pin "P$2") (pinfunction "G_P$2") (pintype "passive"))
      (node (ref "U1104") (pin "P$4") (pinfunction "G_P$4") (pintype "passive"))
    )
    (net (code "193") (name "OTG_FS_DM") (class "Default")
      (node (ref "U101") (pin "70") (pinfunction "PA11_70") (pintype "bidirectional"))
      (node (ref "U302") (pin "6") (pinfunction "D1O_6") (pintype "bidirectional"))
    )
    (net (code "194") (name "OTG_FS_DP") (class "Default")
      (node (ref "U101") (pin "71") (pinfunction "PA12_71") (pintype "bidirectional"))
      (node (ref "U302") (pin "4") (pinfunction "D2O_4") (pintype "bidirectional"))
    )
    (net (code "195") (name "PPM_INPUT") (class "Default")
      (node (ref "D901") (pin "C") (pinfunction "C_C") (pintype "passive"))
      (node (ref "R909") (pin "P$1") (pinfunction "1_P$1") (pintype "passive"))
      (node (ref "U801") (pin "29") (pinfunction "PA8_29") (pintype "bidirectional"))
      (node (ref "U903") (pin "2") (pinfunction "1A_2") (pintype "bidirectional"))
    )
    (net (code "196") (name "PRESSURE_SENS") (class "Default")
      (node (ref "C401") (pin "P$1") (pinfunction "1_P$1") (pintype "passive"))
      (node (ref "R403") (pin "P$2") (pinfunction "2_P$2") (pintype "passive"))
      (node (ref "R406") (pin "P$1") (pinfunction "1_P$1") (pintype "passive"))
      (node (ref "U101") (pin "34") (pinfunction "PC5_34") (pintype "bidirectional"))
    )
    (net (code "197") (name "PRESSURE_SENS_IN") (class "Default")
      (node (ref "ADC_PR") (pin "P$1") (pinfunction "P$1_P$1") (pintype "passive"))
      (node (ref "J402") (pin "2") (pinfunction "2_2") (pintype "passive"))
      (node (ref "R406") (pin "P$2") (pinfunction "2_P$2") (pintype "passive"))
    )
    (net (code "198") (name "RSSI_IN") (class "Default")
      (node (ref "R901") (pin "P$1") (pinfunction "1_P$1") (pintype "passive"))
      (node (ref "U801") (pin "15") (pinfunction "PA5_15") (pintype "bidirectional"))
      (node (ref "U801") (pin "33") (pinfunction "PA12_33") (pintype "bidirectional"))
    )
    (net (code "199") (name "SAFETY") (class "Default")
      (node (ref "J702") (pin "3") (pinfunction "3_3") (pintype "passive"))
      (node (ref "R713") (pin "P$1") (pinfunction "1_P$1") (pintype "passive"))
      (node (ref "U801") (pin "41") (pinfunction "PB5_41") (pintype "bidirectional"))
    )
    (net (code "200") (name "SBUS_INPUT") (class "Default")
      (node (ref "U801") (pin "22") (pinfunction "PB11_22") (pintype "bidirectional"))
      (node (ref "U903") (pin "6") (pinfunction "1Y_6") (pintype "bidirectional"))
    )
    (net (code "201") (name "SBUS_OUTPUT") (class "Default")
      (node (ref "U801") (pin "21") (pinfunction "PB10_21") (pintype "bidirectional"))
      (node (ref "U903") (pin "5") (pinfunction "2A_5") (pintype "bidirectional"))
    )
    (net (code "202") (name "SDIO_CK") (class "Default")
      (node (ref "U101") (pin "80") (pinfunction "PC12_80") (pintype "bidirectional"))
      (node (ref "U301") (pin "5") (pinfunction "CLK_5") (pintype "bidirectional"))
    )
    (net (code "203") (name "SDIO_CMD") (class "Default")
      (node (ref "R303") (pin "P$1") (pinfunction "1_P$1") (pintype "passive"))
      (node (ref "U101") (pin "83") (pinfunction "PD2_83") (pintype "bidirectional"))
      (node (ref "U301") (pin "3") (pinfunction "CMD_3") (pintype "bidirectional"))
    )
    (net (code "204") (name "SDIO_D0") (class "Default")
      (node (ref "R304") (pin "P$1") (pinfunction "1_P$1") (pintype "passive"))
      (node (ref "U101") (pin "65") (pinfunction "PC8_65") (pintype "bidirectional"))
      (node (ref "U301") (pin "7") (pinfunction "D0_7") (pintype "bidirectional"))
    )
    (net (code "205") (name "SDIO_D1") (class "Default")
      (node (ref "R305") (pin "P$1") (pinfunction "1_P$1") (pintype "passive"))
      (node (ref "U101") (pin "66") (pinfunction "PC9_66") (pintype "bidirectional"))
      (node (ref "U301") (pin "8") (pinfunction "D1_8") (pintype "bidirectional"))
    )
    (net (code "206") (name "SDIO_D2") (class "Default")
      (node (ref "R301") (pin "P$1") (pinfunction "1_P$1") (pintype "passive"))
      (node (ref "U101") (pin "78") (pinfunction "PC10_78") (pintype "bidirectional"))
      (node (ref "U301") (pin "1") (pinfunction "D2_1") (pintype "bidirectional"))
    )
    (net (code "207") (name "SDIO_D3") (class "Default")
      (node (ref "R302") (pin "P$1") (pinfunction "1_P$1") (pintype "passive"))
      (node (ref "U101") (pin "79") (pinfunction "PC11_79") (pintype "bidirectional"))
      (node (ref "U301") (pin "2") (pinfunction "D3_2") (pintype "bidirectional"))
    )
    (net (code "208") (name "SERIAL1_CTS") (class "Default")
      (node (ref "J201") (pin "4") (pinfunction "4_4") (pintype "passive"))
      (node (ref "R211") (pin "P$2") (pinfunction "2_P$2") (pintype "passive"))
    )
    (net (code "209") (name "SERIAL1_RTS") (class "Default")
      (node (ref "J201") (pin "5") (pinfunction "5_5") (pintype "passive"))
      (node (ref "R204") (pin "P$2") (pinfunction "2_P$2") (pintype "passive"))
    )
    (net (code "210") (name "SERIAL1_RX") (class "Default")
      (node (ref "J201") (pin "3") (pinfunction "3_3") (pintype "passive"))
      (node (ref "R203") (pin "P$2") (pinfunction "2_P$2") (pintype "passive"))
      (node (ref "S1RX") (pin "P$1") (pinfunction "P$1_P$1") (pintype "passive"))
    )
    (net (code "211") (name "SERIAL1_TX") (class "Default")
      (node (ref "J201") (pin "2") (pinfunction "2_2") (pintype "passive"))
      (node (ref "R210") (pin "P$2") (pinfunction "2_P$2") (pintype "passive"))
      (node (ref "S1TX") (pin "P$1") (pinfunction "P$1_P$1") (pintype "passive"))
    )
    (net (code "212") (name "SERIAL2_CTS") (class "Default")
      (node (ref "J202") (pin "4") (pinfunction "4_4") (pintype "passive"))
      (node (ref "R208") (pin "P$2") (pinfunction "2_P$2") (pintype "passive"))
    )
    (net (code "213") (name "SERIAL2_RTS") (class "Default")
      (node (ref "J202") (pin "5") (pinfunction "5_5") (pintype "passive"))
      (node (ref "R201") (pin "P$2") (pinfunction "2_P$2") (pintype "passive"))
    )
    (net (code "214") (name "SERIAL2_RX") (class "Default")
      (node (ref "J202") (pin "3") (pinfunction "3_3") (pintype "passive"))
      (node (ref "R202") (pin "P$2") (pinfunction "2_P$2") (pintype "passive"))
      (node (ref "S2RX") (pin "P$1") (pinfunction "P$1_P$1") (pintype "passive"))
    )
    (net (code "215") (name "SERIAL2_TX") (class "Default")
      (node (ref "J202") (pin "2") (pinfunction "2_2") (pintype "passive"))
      (node (ref "R209") (pin "P$2") (pinfunction "2_P$2") (pintype "passive"))
      (node (ref "S2TX") (pin "P$1") (pinfunction "P$1_P$1") (pintype "passive"))
    )
    (net (code "216") (name "SERIAL3_RX") (class "Default")
      (node (ref "J203") (pin "3") (pinfunction "3_3") (pintype "passive"))
      (node (ref "R207") (pin "P$2") (pinfunction "2_P$2") (pintype "passive"))
      (node (ref "S3RX") (pin "P$1") (pinfunction "P$1_P$1") (pintype "passive"))
    )
    (net (code "217") (name "SERIAL3_TX") (class "Default")
      (node (ref "J203") (pin "2") (pinfunction "2_2") (pintype "passive"))
      (node (ref "R214") (pin "P$2") (pinfunction "2_P$2") (pintype "passive"))
      (node (ref "S3TX") (pin "P$1") (pinfunction "P$1_P$1") (pintype "passive"))
    )
    (net (code "218") (name "SERIAL4_RX") (class "Default")
      (node (ref "J204") (pin "3") (pinfunction "3_3") (pintype "passive"))
      (node (ref "R206") (pin "P$2") (pinfunction "2_P$2") (pintype "passive"))
      (node (ref "S4RX") (pin "P$1") (pinfunction "P$1_P$1") (pintype "passive"))
    )
    (net (code "219") (name "SERIAL4_TX") (class "Default")
      (node (ref "J204") (pin "2") (pinfunction "2_2") (pintype "passive"))
      (node (ref "R213") (pin "P$2") (pinfunction "2_P$2") (pintype "passive"))
      (node (ref "S4TX") (pin "P$1") (pinfunction "P$1_P$1") (pintype "passive"))
    )
    (net (code "220") (name "SERIAL5_RX") (class "Default")
      (node (ref "J204") (pin "5") (pinfunction "5_5") (pintype "passive"))
      (node (ref "R205") (pin "P$2") (pinfunction "2_P$2") (pintype "passive"))
      (node (ref "S5_RX") (pin "P$1") (pinfunction "P$1_P$1") (pintype "passive"))
    )
    (net (code "221") (name "SERIAL5_TX") (class "Default")
      (node (ref "J204") (pin "4") (pinfunction "4_4") (pintype "passive"))
      (node (ref "R212") (pin "P$2") (pinfunction "2_P$2") (pintype "passive"))
      (node (ref "S5_TX") (pin "P$1") (pinfunction "P$1_P$1") (pintype "passive"))
    )
    (net (code "222") (name "SERIAL_FMU_TO_IO") (class "Default")
      (node (ref "R804") (pin "P$2") (pinfunction "2_P$2") (pintype "passive"))
      (node (ref "U101") (pin "63") (pinfunction "PC6_63") (pintype "bidirectional"))
    )
    (net (code "223") (name "SERIAL_IO_TO_FMU") (class "Default")
      (node (ref "R803") (pin "P$2") (pinfunction "2_P$2") (pintype "passive"))
      (node (ref "U101") (pin "64") (pinfunction "PC7_64") (pintype "bidirectional"))
    )
    (net (code "224") (name "SPI_EXT_MISO") (class "Default")
      (node (ref "J403") (pin "3") (pinfunction "3_3") (pintype "passive"))
      (node (ref "U101") (pin "4") (pinfunction "PE5_4") (pintype "bidirectional"))
    )
    (net (code "225") (name "SPI_EXT_MOSI") (class "Default")
      (node (ref "J403") (pin "4") (pinfunction "4_4") (pintype "passive"))
      (node (ref "U101") (pin "5") (pinfunction "PE6_5") (pintype "bidirectional"))
    )
    (net (code "226") (name "SPI_EXT_SCK") (class "Default")
      (node (ref "J403") (pin "2") (pinfunction "2_2") (pintype "passive"))
      (node (ref "U101") (pin "1") (pinfunction "PE2_1") (pintype "bidirectional"))
    )
    (net (code "227") (name "SPI_INT_MISO") (class "Default")
      (node (ref "U101") (pin "31") (pinfunction "PA6_31") (pintype "bidirectional"))
      (node (ref "U501") (pin "4") (pinfunction "SDO/SA0_4") (pintype "bidirectional"))
      (node (ref "U502") (pin "4") (pinfunction "SDO/SA0_4") (pintype "bidirectional"))
      (node (ref "U504") (pin "7") (pinfunction "SDO/SA0_7") (pintype "bidirectional"))
      (node (ref "U505") (pin "9") (pinfunction "AD0/SDO_9") (pintype "bidirectional"))
      (node (ref "U506") (pin "6") (pinfunction "SDO_6") (pintype "bidirectional"))
      (node (ref "X503") (pin "9") (pinfunction "S_9") (pintype "passive"))
    )
    (net (code "228") (name "SPI_INT_MOSI") (class "Default")
      (node (ref "U101") (pin "32") (pinfunction "PA7_32") (pintype "bidirectional"))
      (node (ref "U501") (pin "3") (pinfunction "SDA/SDI/SDO_3") (pintype "bidirectional"))
      (node (ref "U502") (pin "3") (pinfunction "SDA/SDI/SDO_3") (pintype "bidirectional"))
      (node (ref "U504") (pin "6") (pinfunction "SDA/SDI/SDO_6") (pintype "bidirectional"))
      (node (ref "U505") (pin "24") (pinfunction "SDA/SDI_24") (pintype "bidirectional"))
      (node (ref "U506") (pin "7") (pinfunction "SDI/SDA_7") (pintype "bidirectional"))
      (node (ref "X503") (pin "8") (pinfunction "S_8") (pintype "passive"))
    )
    (net (code "229") (name "SPI_INT_SCK") (class "Default")
      (node (ref "U101") (pin "30") (pinfunction "PA5_30") (pintype "bidirectional"))
      (node (ref "U501") (pin "2") (pinfunction "SCL/SPC_2") (pintype "input"))
      (node (ref "U502") (pin "2") (pinfunction "SCL/SPC_2") (pintype "bidirectional"))
      (node (ref "U504") (pin "4") (pinfunction "SCL/SPC_4") (pintype "bidirectional"))
      (node (ref "U505") (pin "23") (pinfunction "SCL/SCLK_23") (pintype "bidirectional"))
      (node (ref "U506") (pin "8") (pinfunction "SCLK_8") (pintype "bidirectional"))
      (node (ref "X503") (pin "10") (pinfunction "S_10") (pintype "passive"))
    )
    (net (code "230") (name "VBAT") (class "Default")
      (node (ref "B601") (pin "1") (pinfunction "POS_1") (pintype "bidirectional"))
      (node (ref "R608") (pin "P$1") (pinfunction "1_P$1") (pintype "passive"))
      (node (ref "U101") (pin "6") (pinfunction "VBAT_6") (pintype "power_in"))
      (node (ref "U801") (pin "1") (pinfunction "VBAT_1") (pintype "power_in"))
    )
    (net (code "231") (name "VBUS") (class "Default")
      (node (ref "C1103") (pin "P$1") (pinfunction "1_P$1") (pintype "passive"))
      (node (ref "J301") (pin "VBUS") (pinfunction "1_VBUS") (pintype "power_in"))
      (node (ref "J302") (pin "1") (pinfunction "1_1") (pintype "passive"))
      (node (ref "R1112") (pin "P$1") (pinfunction "1_P$1") (pintype "passive"))
      (node (ref "U101") (pin "68") (pinfunction "PA9_68") (pintype "bidirectional"))
      (node (ref "U1101") (pin "P$19") (pinfunction "V3_P$19") (pintype "bidirectional"))
      (node (ref "U1104") (pin "P$7") (pinfunction "D_P$7") (pintype "passive"))
      (node (ref "U1104") (pin "P$8") (pinfunction "D_P$8") (pintype "passive"))
      (node (ref "U302") (pin "5") (pinfunction "VBUS_5") (pintype "bidirectional"))
      (node (ref "VBUS") (pin "P$1") (pinfunction "P$1_P$1") (pintype "passive"))
    )
    (net (code "232") (name "VDD_3V3_SENSORS") (class "Default")
      (node (ref "C501") (pin "P$1") (pinfunction "1_P$1") (pintype "passive"))
      (node (ref "C502") (pin "P$1") (pinfunction "1_P$1") (pintype "passive"))
      (node (ref "C503") (pin "P$1") (pinfunction "1_P$1") (pintype "passive"))
      (node (ref "C506") (pin "P$1") (pinfunction "1_P$1") (pintype "passive"))
      (node (ref "C507") (pin "P$1") (pinfunction "1_P$1") (pintype "passive"))
      (node (ref "C508") (pin "P$1") (pinfunction "1_P$1") (pintype "passive"))
      (node (ref "C511") (pin "P$1") (pinfunction "1_P$1") (pintype "passive"))
      (node (ref "C513") (pin "P$1") (pinfunction "1_P$1") (pintype "passive"))
      (node (ref "C514") (pin "P$1") (pinfunction "1_P$1") (pintype "passive"))
      (node (ref "C605") (pin "P$1") (pinfunction "1_P$1") (pintype "passive"))
      (node (ref "C617") (pin "P$1") (pinfunction "1_P$1") (pintype "passive"))
      (node (ref "R621") (pin "2") (pinfunction "2_2") (pintype "passive"))
      (node (ref "U501") (pin "1") (pinfunction "VDD_IO_1") (pintype "bidirectional"))
      (node (ref "U501") (pin "15") (pinfunction "RES_P15_VDD_15") (pintype "bidirectional"))
      (node (ref "U501") (pin "16") (pinfunction "VDD_16") (pintype "bidirectional"))
      (node (ref "U502") (pin "1") (pinfunction "VDD_IO_1") (pintype "bidirectional"))
      (node (ref "U502") (pin "15") (pinfunction "VDD_15") (pintype "bidirectional"))
      (node (ref "U502") (pin "16") (pinfunction "VDD_16") (pintype "bidirectional"))
      (node (ref "U504") (pin "1") (pinfunction "VDD_IO_1") (pintype "bidirectional"))
      (node (ref "U504") (pin "14") (pinfunction "VDD_14") (pintype "bidirectional"))
      (node (ref "U505") (pin "13") (pinfunction "VDD_13") (pintype "bidirectional"))
      (node (ref "U506") (pin "1") (pinfunction "VDD_1") (pintype "bidirectional"))
      (node (ref "U603") (pin "8") (pinfunction "VOUT1_8") (pintype "bidirectional"))
      (node (ref "VDDA_3V1101") (pin "P$1") (pinfunction "P$1_P$1") (pintype "passive"))
      (node (ref "X503") (pin "1") (pinfunction "S_1") (pintype "passive"))
    )
    (net (code "233") (name "VDD_3V3_SENSORS_EN") (class "Default")
      (node (ref "R603") (pin "P$2") (pinfunction "2_P$2") (pintype "passive"))
      (node (ref "R635") (pin "P$2") (pinfunction "2_P$2") (pintype "passive"))
      (node (ref "U101") (pin "2") (pinfunction "PE3_2") (pintype "bidirectional"))
      (node (ref "U603") (pin "5") (pinfunction "EN1_5") (pintype "bidirectional"))
    )
    (net (code "234") (name "VDD_3V3_SPEKTRUM") (class "Default")
      (node (ref "C1008") (pin "P$1") (pinfunction "1_P$1") (pintype "passive"))
      (node (ref "D801") (pin "C") (pinfunction "C_C") (pintype "passive"))
      (node (ref "J801") (pin "P$1") (pinfunction "P$1_P$1") (pintype "bidirectional"))
      (node (ref "U1002") (pin "8") (pinfunction "VOUT1_8") (pintype "bidirectional"))
    )
    (net (code "235") (name "VDD_3V3_SPEKTRUM_EN") (class "Default")
      (node (ref "R1002") (pin "P$2") (pinfunction "2_P$2") (pintype "passive"))
      (node (ref "U1002") (pin "5") (pinfunction "EN1_5") (pintype "bidirectional"))
      (node (ref "U801") (pin "2") (pinfunction "PC13_2") (pintype "bidirectional"))
    )
    (net (code "236") (name "VDD_5V_BRICK") (class "Default")
      (node (ref "C1101") (pin "P$1") (pinfunction "1_P$1") (pintype "passive"))
      (node (ref "J601") (pin "1") (pinfunction "1_1") (pintype "passive"))
      (node (ref "J601") (pin "2") (pinfunction "2_2") (pintype "passive"))
      (node (ref "R1105") (pin "P$1") (pinfunction "1_P$1") (pintype "passive"))
      (node (ref "U1101") (pin "P$21") (pinfunction "V1_P$21") (pintype "bidirectional"))
      (node (ref "U1102") (pin "P$7") (pinfunction "D_P$7") (pintype "passive"))
      (node (ref "U1102") (pin "P$8") (pinfunction "D_P$8") (pintype "passive"))
      (node (ref "VDD_5V_BRICK") (pin "P$1") (pinfunction "P$1_P$1") (pintype "passive"))
    )
    (net (code "237") (name "VDD_5V_HIPOWER") (class "Default")
      (node (ref "C614") (pin "P$1") (pinfunction "1_P$1") (pintype "passive"))
      (node (ref "L201") (pin "P$1") (pinfunction "P$1_P$1") (pintype "bidirectional"))
      (node (ref "U601") (pin "8") (pinfunction "OUT_8") (pintype "bidirectional"))
    )
    (net (code "238") (name "VDD_5V_IN") (class "Default")
      (node (ref "C1104") (pin "P$1") (pinfunction "1_P$1") (pintype "passive"))
      (node (ref "C702") (pin "P$1") (pinfunction "1_P$1") (pintype "passive"))
      (node (ref "F1001") (pin "1") (pinfunction "1_1") (pintype "bidirectional"))
      (node (ref "L603") (pin "P$1") (pinfunction "P$1_P$1") (pintype "bidirectional"))
      (node (ref "L701") (pin "P$1") (pinfunction "1_P$1") (pintype "passive"))
      (node (ref "LED701") (pin "A") (pinfunction "A_A") (pintype "passive"))
      (node (ref "LED704") (pin "A") (pinfunction "A_A") (pintype "passive"))
      (node (ref "R609") (pin "P$2") (pinfunction "2_P$2") (pintype "passive"))
      (node (ref "RN1101") (pin "5") (pinfunction "2_5") (pintype "passive"))
      (node (ref "RN1101") (pin "6") (pinfunction "2_6") (pintype "passive"))
      (node (ref "RN1101") (pin "7") (pinfunction "2_7") (pintype "passive"))
      (node (ref "U1101") (pin "P$12") (pinfunction "VOUT_P$12") (pintype "bidirectional"))
      (node (ref "U1102") (pin "P$5") (pinfunction "D_P$5") (pintype "passive"))
      (node (ref "U1102") (pin "P$6") (pinfunction "D_P$6") (pintype "passive"))
      (node (ref "U1103") (pin "P$5") (pinfunction "D_P$5") (pintype "passive"))
      (node (ref "U1103") (pin "P$6") (pinfunction "D_P$6") (pintype "passive"))
      (node (ref "U1104") (pin "P$5") (pinfunction "D_P$5") (pintype "passive"))
      (node (ref "U1104") (pin "P$6") (pinfunction "D_P$6") (pintype "passive"))
      (node (ref "U601") (pin "1") (pinfunction "IN_1") (pintype "bidirectional"))
      (node (ref "U602") (pin "1") (pinfunction "IN_1") (pintype "bidirectional"))
      (node (ref "U702") (pin "3") (pinfunction "VIN_3") (pintype "power_in"))
      (node (ref "U703") (pin "A1") (pinfunction "A_A1") (pintype "passive"))
      (node (ref "U703") (pin "A2") (pinfunction "A_A2") (pintype "passive"))
      (node (ref "U703") (pin "A3") (pinfunction "A_A3") (pintype "passive"))
      (node (ref "VDD_5V_IN") (pin "P$1") (pinfunction "P$1_P$1") (pintype "passive"))
    )
    (net (code "239") (name "VDD_5V_PERIPH") (class "Default")
      (node (ref "C618") (pin "P$1") (pinfunction "1_P$1") (pintype "passive"))
      (node (ref "L202") (pin "P$1") (pinfunction "P$1_P$1") (pintype "bidirectional"))
      (node (ref "L203") (pin "P$1") (pinfunction "P$1_P$1") (pintype "bidirectional"))
      (node (ref "L401") (pin "P$1") (pinfunction "P$1_P$1") (pintype "bidirectional"))
      (node (ref "L402") (pin "P$1") (pinfunction "P$1_P$1") (pintype "bidirectional"))
      (node (ref "L403") (pin "P$1") (pinfunction "P$1_P$1") (pintype "bidirectional"))
      (node (ref "L404") (pin "P$1") (pinfunction "P$1_P$1") (pintype "bidirectional"))
      (node (ref "U602") (pin "8") (pinfunction "OUT_8") (pintype "bidirectional"))
    )
    (net (code "240") (name "VDD_5V_SENS") (class "Default")
      (node (ref "R609") (pin "P$1") (pinfunction "1_P$1") (pintype "passive"))
      (node (ref "R610") (pin "P$1") (pinfunction "1_P$1") (pintype "passive"))
      (node (ref "U101") (pin "29") (pinfunction "PA4_29") (pintype "bidirectional"))
    )
    (net (code "241") (name "VDD_SERVO") (class "Default")
      (node (ref "C1102") (pin "P$1") (pinfunction "1_P$1") (pintype "passive"))
      (node (ref "D904") (pin "ANODE") (pinfunction "A_ANODE") (pintype "passive"))
      (node (ref "J901") (pin "11") (pinfunction "S_11") (pintype "passive"))
      (node (ref "J901") (pin "14") (pinfunction "S_14") (pintype "passive"))
      (node (ref "J901") (pin "17") (pinfunction "S_17") (pintype "passive"))
      (node (ref "J901") (pin "20") (pinfunction "S_20") (pintype "passive"))
      (node (ref "J901") (pin "23") (pinfunction "S_23") (pintype "passive"))
      (node (ref "J901") (pin "26") (pinfunction "S_26") (pintype "passive"))
      (node (ref "J901") (pin "29") (pinfunction "S_29") (pintype "passive"))
      (node (ref "J901") (pin "32") (pinfunction "S_32") (pintype "passive"))
      (node (ref "J901") (pin "35") (pinfunction "S_35") (pintype "passive"))
      (node (ref "J901") (pin "38") (pinfunction "S_38") (pintype "passive"))
      (node (ref "J901") (pin "41") (pinfunction "S_41") (pintype "passive"))
      (node (ref "J901") (pin "44") (pinfunction "S_44") (pintype "passive"))
      (node (ref "J901") (pin "47") (pinfunction "S_47") (pintype "passive"))
      (node (ref "J901") (pin "5") (pinfunction "S_5") (pintype "passive"))
      (node (ref "J901") (pin "8") (pinfunction "S_8") (pintype "passive"))
      (node (ref "R1109") (pin "P$1") (pinfunction "1_P$1") (pintype "passive"))
      (node (ref "R922") (pin "P$2") (pinfunction "2_P$2") (pintype "passive"))
      (node (ref "U1101") (pin "P$20") (pinfunction "V2_P$20") (pintype "bidirectional"))
      (node (ref "U1103") (pin "P$7") (pinfunction "D_P$7") (pintype "passive"))
      (node (ref "U1103") (pin "P$8") (pinfunction "D_P$8") (pintype "passive"))
      (node (ref "VDD_SERVO") (pin "P$1") (pinfunction "P$1_P$1") (pintype "passive"))
    )
    (net (code "242") (name "VDD_SERVO_IN") (class "Default")
      (node (ref "L901") (pin "P$2") (pinfunction "P$2_P$2") (pintype "bidirectional"))
      (node (ref "U1001") (pin "1") (pinfunction "IN_1") (pintype "bidirectional"))
    )
    (net (code "243") (name "VDD_SERVO_SENS") (class "Default")
      (node (ref "R918") (pin "P$1") (pinfunction "1_P$1") (pintype "passive"))
      (node (ref "R919") (pin "P$2") (pinfunction "2_P$2") (pintype "passive"))
      (node (ref "U801") (pin "14") (pinfunction "PA4_14") (pintype "bidirectional"))
    )
    (net (code "244") (name "unconnected-(J301-4-PadID)") (class "Default")
      (node (ref "J301") (pin "ID") (pinfunction "4_ID") (pintype "passive"))
    )
    (net (code "245") (name "unconnected-(JX301A-S-Pad10)") (class "Default")
      (node (ref "JX301") (pin "10") (pinfunction "S_10") (pintype "passive"))
    )
    (net (code "246") (name "unconnected-(JX301F-S-Pad8)") (class "Default")
      (node (ref "JX301") (pin "8") (pinfunction "S_8") (pintype "passive"))
    )
    (net (code "247") (name "unconnected-(JX802A-S-Pad10)") (class "Default")
      (node (ref "JX802") (pin "10") (pinfunction "S_10") (pintype "passive"))
    )
    (net (code "248") (name "unconnected-(JX802F-S-Pad8)") (class "Default")
      (node (ref "JX802") (pin "8") (pinfunction "S_8") (pintype "passive"))
    )
    (net (code "249") (name "unconnected-(U101I-PC1-Pad16)") (class "Default")
      (node (ref "U101") (pin "16") (pinfunction "PC1_16") (pintype "bidirectional"))
    )
    (net (code "250") (name "unconnected-(U202-A1-Pad1)") (class "Default")
      (node (ref "U202") (pin "1") (pinfunction "A1_1") (pintype "bidirectional"))
    )
    (net (code "251") (name "unconnected-(U202-A2-Pad3)") (class "Default")
      (node (ref "U202") (pin "3") (pinfunction "A2_3") (pintype "bidirectional"))
    )
    (net (code "252") (name "unconnected-(U202-B1-Pad20)") (class "Default")
      (node (ref "U202") (pin "20") (pinfunction "B1_20") (pintype "bidirectional"))
    )
    (net (code "253") (name "unconnected-(U202-B2-Pad18)") (class "Default")
      (node (ref "U202") (pin "18") (pinfunction "B2_18") (pintype "bidirectional"))
    )
    (net (code "254") (name "unconnected-(U501-INT1-Pad7)") (class "Default")
      (node (ref "U501") (pin "7") (pinfunction "INT1_7") (pintype "output"))
    )
    (net (code "255") (name "unconnected-(U502-DEN-Pad8)") (class "Default")
      (node (ref "U502") (pin "8") (pinfunction "DEN_8") (pintype "bidirectional"))
    )
    (net (code "256") (name "unconnected-(U502-INT1-Pad7)") (class "Default")
      (node (ref "U502") (pin "7") (pinfunction "INT1_7") (pintype "bidirectional"))
    )
    (net (code "257") (name "unconnected-(U505-AUX_CL-Pad7)") (class "Default")
      (node (ref "U505") (pin "7") (pinfunction "AUX_CL_7") (pintype "bidirectional"))
    )
    (net (code "258") (name "unconnected-(U505-AUX_DA-Pad6)") (class "Default")
      (node (ref "U505") (pin "6") (pinfunction "AUX_DA_6") (pintype "bidirectional"))
    )
    (net (code "259") (name "unconnected-(U505-CLKOUT-Pad22)") (class "Default")
      (node (ref "U505") (pin "22") (pinfunction "CLKOUT_22") (pintype "bidirectional"))
    )
    (net (code "260") (name "unconnected-(U505-FSYNC-Pad11)") (class "Default")
      (node (ref "U505") (pin "11") (pinfunction "FSYNC_11") (pintype "bidirectional"))
    )
    (net (code "261") (name "unconnected-(U505-NC1-Pad2)") (class "Default")
      (node (ref "U505") (pin "2") (pinfunction "NC1_2") (pintype "bidirectional"))
    )
    (net (code "262") (name "unconnected-(U505-NC2-Pad3)") (class "Default")
      (node (ref "U505") (pin "3") (pinfunction "NC2_3") (pintype "bidirectional"))
    )
    (net (code "263") (name "unconnected-(U505-NC3-Pad4)") (class "Default")
      (node (ref "U505") (pin "4") (pinfunction "NC3_4") (pintype "bidirectional"))
    )
    (net (code "264") (name "unconnected-(U505-NC4-Pad5)") (class "Default")
      (node (ref "U505") (pin "5") (pinfunction "NC4_5") (pintype "bidirectional"))
    )
    (net (code "265") (name "unconnected-(U505-NC5-Pad14)") (class "Default")
      (node (ref "U505") (pin "14") (pinfunction "NC5_14") (pintype "bidirectional"))
    )
    (net (code "266") (name "unconnected-(U505-NC6-Pad15)") (class "Default")
      (node (ref "U505") (pin "15") (pinfunction "NC6_15") (pintype "bidirectional"))
    )
    (net (code "267") (name "unconnected-(U505-NC7-Pad16)") (class "Default")
      (node (ref "U505") (pin "16") (pinfunction "NC7_16") (pintype "bidirectional"))
    )
    (net (code "268") (name "unconnected-(U505-NC8-Pad17)") (class "Default")
      (node (ref "U505") (pin "17") (pinfunction "NC8_17") (pintype "bidirectional"))
    )
    (net (code "269") (name "unconnected-(U505-RESV1-Pad19)") (class "Default")
      (node (ref "U505") (pin "19") (pinfunction "RESV1_19") (pintype "bidirectional"))
    )
    (net (code "270") (name "unconnected-(U505-RESV2-Pad21)") (class "Default")
      (node (ref "U505") (pin "21") (pinfunction "RESV2_21") (pintype "bidirectional"))
    )
    (net (code "271") (name "unconnected-(U506-CSB1-Pad4)") (class "Default")
      (node (ref "U506") (pin "4") (pinfunction "CSB1_4") (pintype "bidirectional"))
    )
    (net (code "272") (name "unconnected-(U801B-PA11-Pad32)") (class "Default")
      (node (ref "U801") (pin "32") (pinfunction "PA11_32") (pintype "bidirectional"))
    )
    (net (code "273") (name "unconnected-(U801D-PB12-Pad25)") (class "Default")
      (node (ref "U801") (pin "25") (pinfunction "PB12_25") (pintype "bidirectional"))
    )
    (net (code "274") (name "unconnected-(U801E-PB6-Pad42)") (class "Default")
      (node (ref "U801") (pin "42") (pinfunction "PB6_42") (pintype "bidirectional"))
    )
    (net (code "275") (name "unconnected-(U801E-PB7-Pad43)") (class "Default")
      (node (ref "U801") (pin "43") (pinfunction "PB7_43") (pintype "bidirectional"))
    )
    (net (code "276") (name "unconnected-(U801F-PC14-Pad3)") (class "Default")
      (node (ref "U801") (pin "3") (pinfunction "PC14_3") (pintype "bidirectional"))
    )
    (net (code "277") (name "unconnected-(U801F-PC15-Pad4)") (class "Default")
      (node (ref "U801") (pin "4") (pinfunction "PC15_4") (pintype "bidirectional"))
    )
    (net (code "278") (name "unconnected-(U901-A7-Pad8)") (class "Default")
      (node (ref "U901") (pin "8") (pinfunction "A7_8") (pintype "bidirectional"))
    )
    (net (code "279") (name "unconnected-(U901-A8-Pad9)") (class "Default")
      (node (ref "U901") (pin "9") (pinfunction "A8_9") (pintype "bidirectional"))
    )
    (net (code "280") (name "unconnected-(U901-B7-Pad13)") (class "Default")
      (node (ref "U901") (pin "13") (pinfunction "B7_13") (pintype "bidirectional"))
    )
    (net (code "281") (name "unconnected-(U901-B8-Pad12)") (class "Default")
      (node (ref "U901") (pin "12") (pinfunction "B8_12") (pintype "bidirectional"))
    )
    (net (code "282") (name "unconnected-(U1101-CAS-PadP$11)") (class "Default")
      (node (ref "U1101") (pin "P$11") (pinfunction "CAS_P$11") (pintype "bidirectional"))
    )
    (net (code "283") (name "unconnected-(U1101-EN-PadP$22)") (class "Default")
      (node (ref "U1101") (pin "P$22") (pinfunction "EN_P$22") (pintype "bidirectional"))
    )
    (net (code "284") (name "unconnected-(U1101-~{SHDN}-PadP$23)") (class "Default")
      (node (ref "U1101") (pin "P$23") (pinfunction "~{SHDN}_P$23") (pintype "bidirectional"))
    )
    (net (code "285") (name "~{ACCEL_MAG_CS}") (class "Default")
      (node (ref "U101") (pin "9") (pinfunction "PC15_9") (pintype "bidirectional"))
      (node (ref "U504") (pin "8") (pinfunction "CS_8") (pintype "bidirectional"))
      (node (ref "X503") (pin "6") (pinfunction "S_6") (pintype "passive"))
    )
    (net (code "286") (name "~{BARO_CS}") (class "Default")
      (node (ref "U101") (pin "88") (pinfunction "PD7_88") (pintype "bidirectional"))
      (node (ref "U506") (pin "5") (pinfunction "CSB2_5") (pintype "bidirectional"))
    )
    (net (code "287") (name "~{FMU-LED_AMBER}") (class "Default")
      (node (ref "R707") (pin "P$1") (pinfunction "1_P$1") (pintype "passive"))
      (node (ref "U101") (pin "43") (pinfunction "PE12_43") (pintype "bidirectional"))
    )
    (net (code "288") (name "~{FRAM_CS}") (class "Default")
      (node (ref "U101") (pin "57") (pinfunction "PD10_57") (pintype "bidirectional"))
      (node (ref "U102") (pin "1") (pinfunction "~{S}_1") (pintype "bidirectional"))
    )
    (net (code "289") (name "~{GYRO_CS}") (class "Default")
      (node (ref "U101") (pin "7") (pinfunction "PC13_7") (pintype "bidirectional"))
      (node (ref "U501") (pin "5") (pinfunction "CS_5") (pintype "input"))
      (node (ref "U502") (pin "5") (pinfunction "CS_5") (pintype "bidirectional"))
      (node (ref "X503") (pin "7") (pinfunction "S_7") (pintype "passive"))
    )
    (net (code "290") (name "~{IO-LED_AMBER}") (class "Default")
      (node (ref "R709") (pin "P$1") (pinfunction "1_P$1") (pintype "passive"))
      (node (ref "U801") (pin "28") (pinfunction "PB15_28") (pintype "bidirectional"))
    )
    (net (code "291") (name "~{IO-LED_BLUE}") (class "Default")
      (node (ref "R712") (pin "P$1") (pinfunction "1_P$1") (pintype "passive"))
      (node (ref "U801") (pin "27") (pinfunction "PB14_27") (pintype "bidirectional"))
    )
    (net (code "292") (name "~{IO-LED_SAFETY}") (class "Default")
      (node (ref "R710") (pin "P$2") (pinfunction "2_P$2") (pintype "passive"))
      (node (ref "U801") (pin "26") (pinfunction "PB13_26") (pintype "bidirectional"))
    )
    (net (code "293") (name "~{MPU_CS}") (class "Default")
      (node (ref "U101") (pin "17") (pinfunction "PC2_17") (pintype "bidirectional"))
      (node (ref "U505") (pin "8") (pinfunction "/CS_8") (pintype "bidirectional"))
    )
    (net (code "294") (name "~{SBUS_OUTPUT_EN}") (class "Default")
      (node (ref "U801") (pin "40") (pinfunction "PB4_40") (pintype "bidirectional"))
      (node (ref "U903") (pin "7") (pinfunction "~{2OE}_7") (pintype "input"))
    )
    (net (code "295") (name "~{SPI_EXT_NSS}") (class "Default")
      (node (ref "J403") (pin "5") (pinfunction "5_5") (pintype "passive"))
      (node (ref "U101") (pin "3") (pinfunction "PE4_3") (pintype "bidirectional"))
    )
    (net (code "296") (name "~{VBUS_VALID}") (class "Default")
      (node (ref "!VBUS_VALID") (pin "P$1") (pinfunction "P$1_P$1") (pintype "passive"))
      (node (ref "RN1101") (pin "2") (pinfunction "1_2") (pintype "passive"))
      (node (ref "U101") (pin "15") (pinfunction "PC0_15") (pintype "bidirectional"))
      (node (ref "U1101") (pin "P$9") (pinfunction "~{VALID3}_P$9") (pintype "bidirectional"))
    )
    (net (code "297") (name "~{VDD_5V_HIPOWER_OC}") (class "Default")
      (node (ref "R602") (pin "P$1") (pinfunction "1_P$1") (pintype "passive"))
      (node (ref "U101") (pin "41") (pinfunction "PE10_41") (pintype "bidirectional"))
      (node (ref "U601") (pin "4") (pinfunction "~{FAULT}_4") (pintype "bidirectional"))
    )
    (net (code "298") (name "~{VDD_5V_PERIPH_EN}") (class "Default")
      (node (ref "R615") (pin "P$1") (pinfunction "1_P$1") (pintype "passive"))
      (node (ref "U101") (pin "67") (pinfunction "PA8_67") (pintype "bidirectional"))
      (node (ref "U601") (pin "5") (pinfunction "~{CE}_5") (pintype "bidirectional"))
      (node (ref "U602") (pin "5") (pinfunction "~{CE}_5") (pintype "bidirectional"))
    )
    (net (code "299") (name "~{VDD_5V_PERIPH_OC}") (class "Default")
      (node (ref "R604") (pin "P$1") (pinfunction "1_P$1") (pintype "passive"))
      (node (ref "U101") (pin "46") (pinfunction "PE15_46") (pintype "bidirectional"))
      (node (ref "U602") (pin "4") (pinfunction "~{FAULT}_4") (pintype "bidirectional"))
    )
    (net (code "300") (name "~{VDD_BRICK_VALID}") (class "Default")
      (node (ref "!VDD_BRICK_VALID") (pin "P$1") (pinfunction "P$1_P$1") (pintype "passive"))
      (node (ref "RN1101") (pin "4") (pinfunction "1_4") (pintype "passive"))
      (node (ref "U101") (pin "91") (pinfunction "PB5_91") (pintype "bidirectional"))
      (node (ref "U1101") (pin "P$7") (pinfunction "~{VALID1}_P$7") (pintype "bidirectional"))
    )
    (net (code "301") (name "~{VDD_SERVO_VALID}") (class "Default")
      (node (ref "!VDD_SERVO_VALID") (pin "P$1") (pinfunction "P$1_P$1") (pintype "passive"))
      (node (ref "RN1101") (pin "3") (pinfunction "1_3") (pintype "passive"))
      (node (ref "U101") (pin "93") (pinfunction "PB7_93") (pintype "bidirectional"))
      (node (ref "U1101") (pin "P$8") (pinfunction "~{VALID2}_P$8") (pintype "bidirectional"))
    )
  )
)
